# Jupiter_Ace_build024.net
KiCad netlist of a schematic drawn in EAGLE
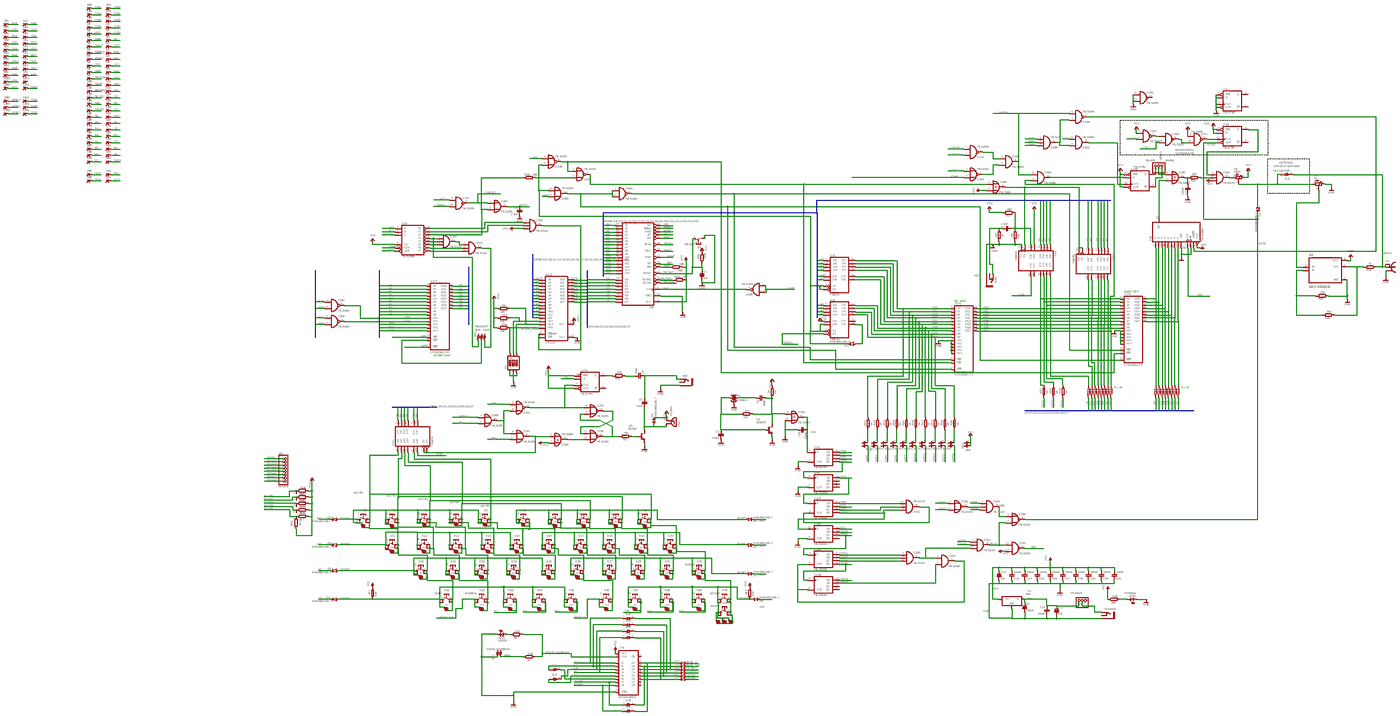
[diagram p0: schematic, sheet 1, overview]
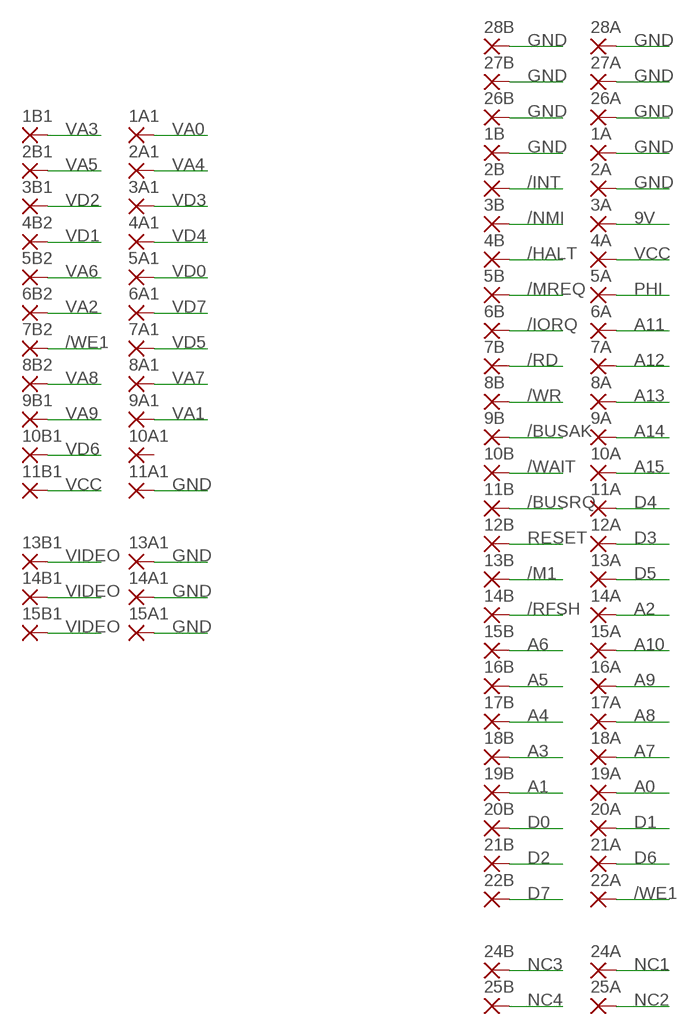
[diagram p1: schematic, sheet 1, part 1 of 5]
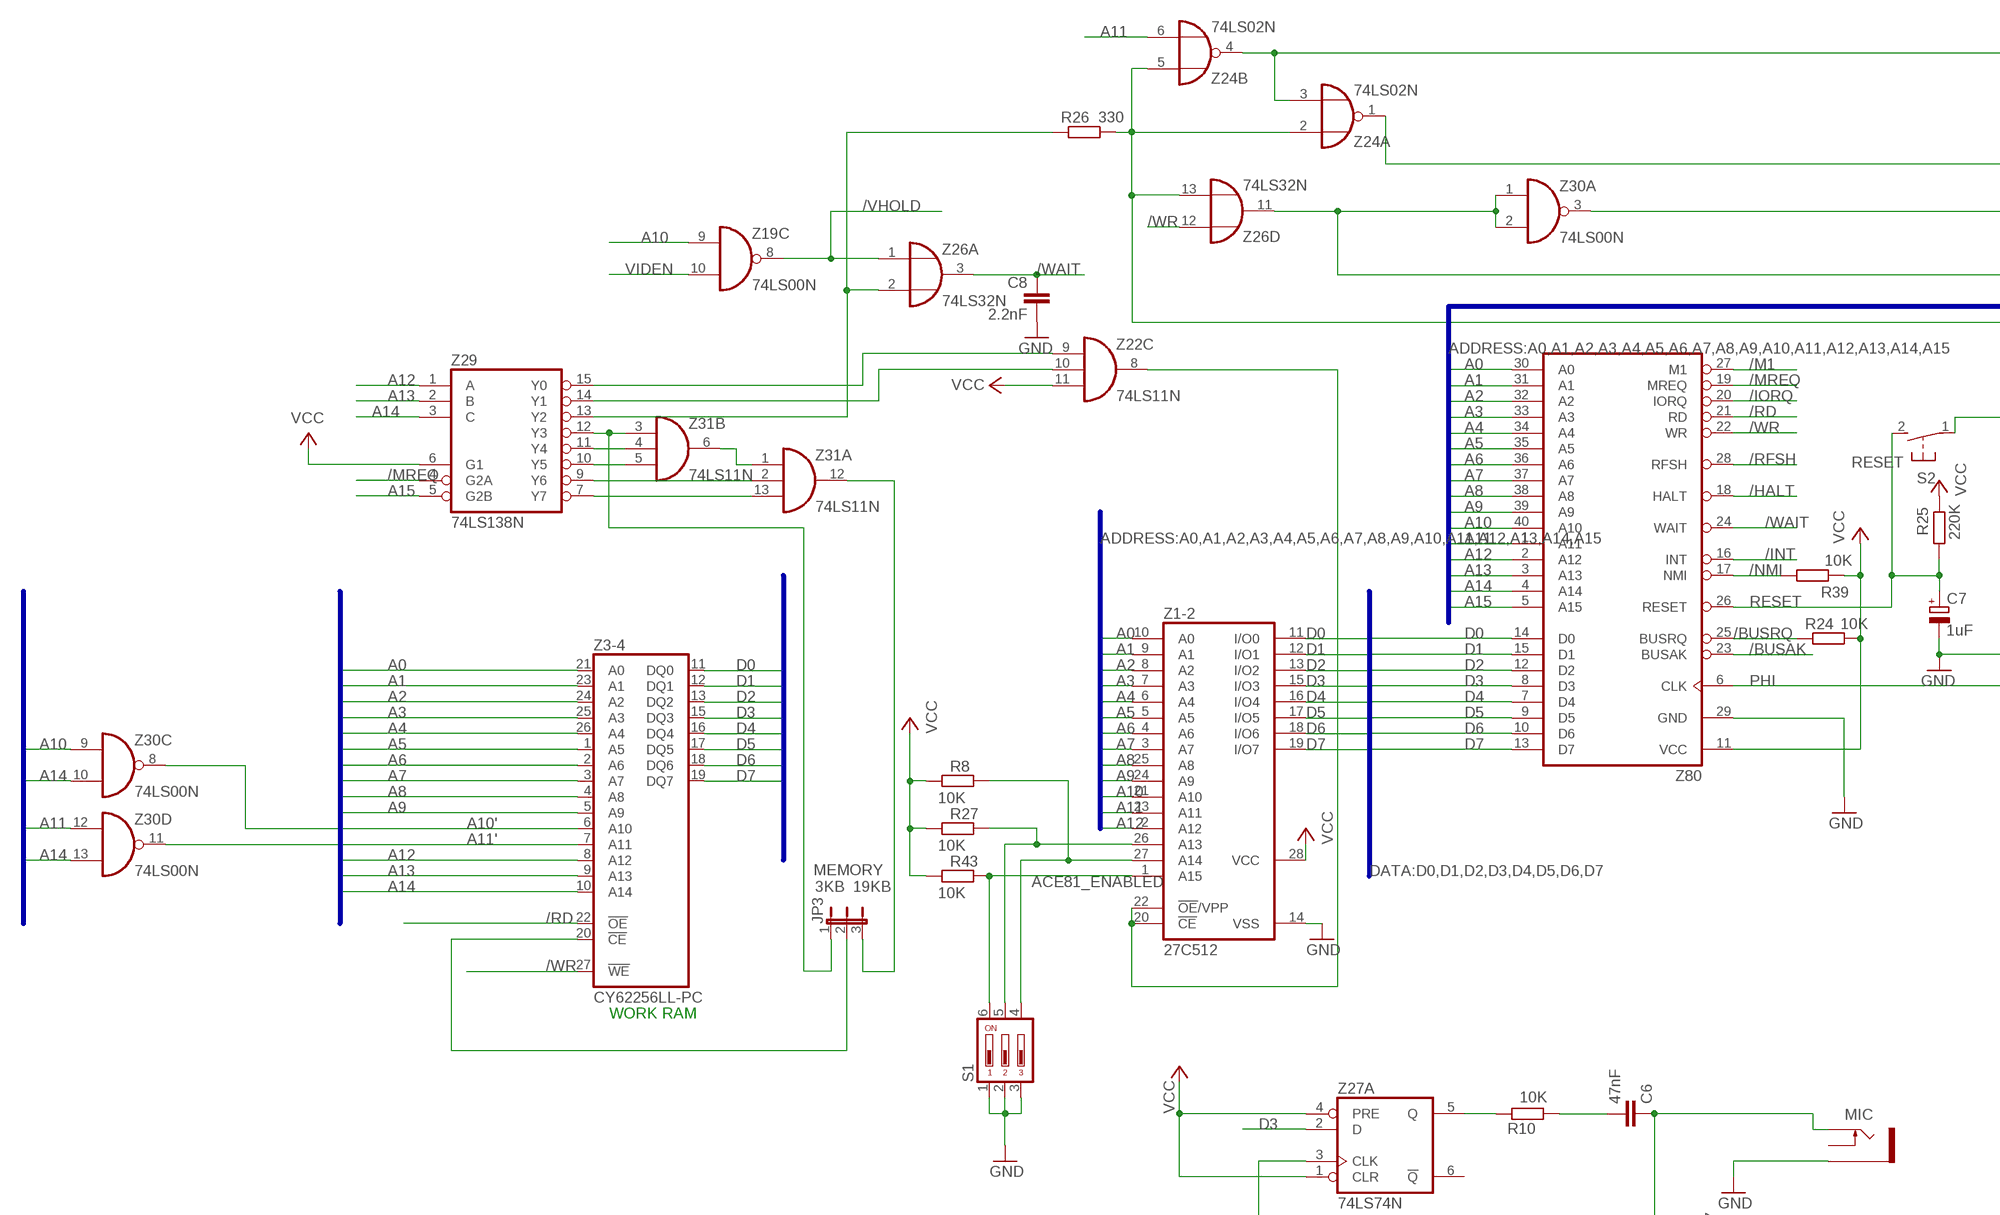
[diagram p2: schematic, sheet 1, part 2 of 5]
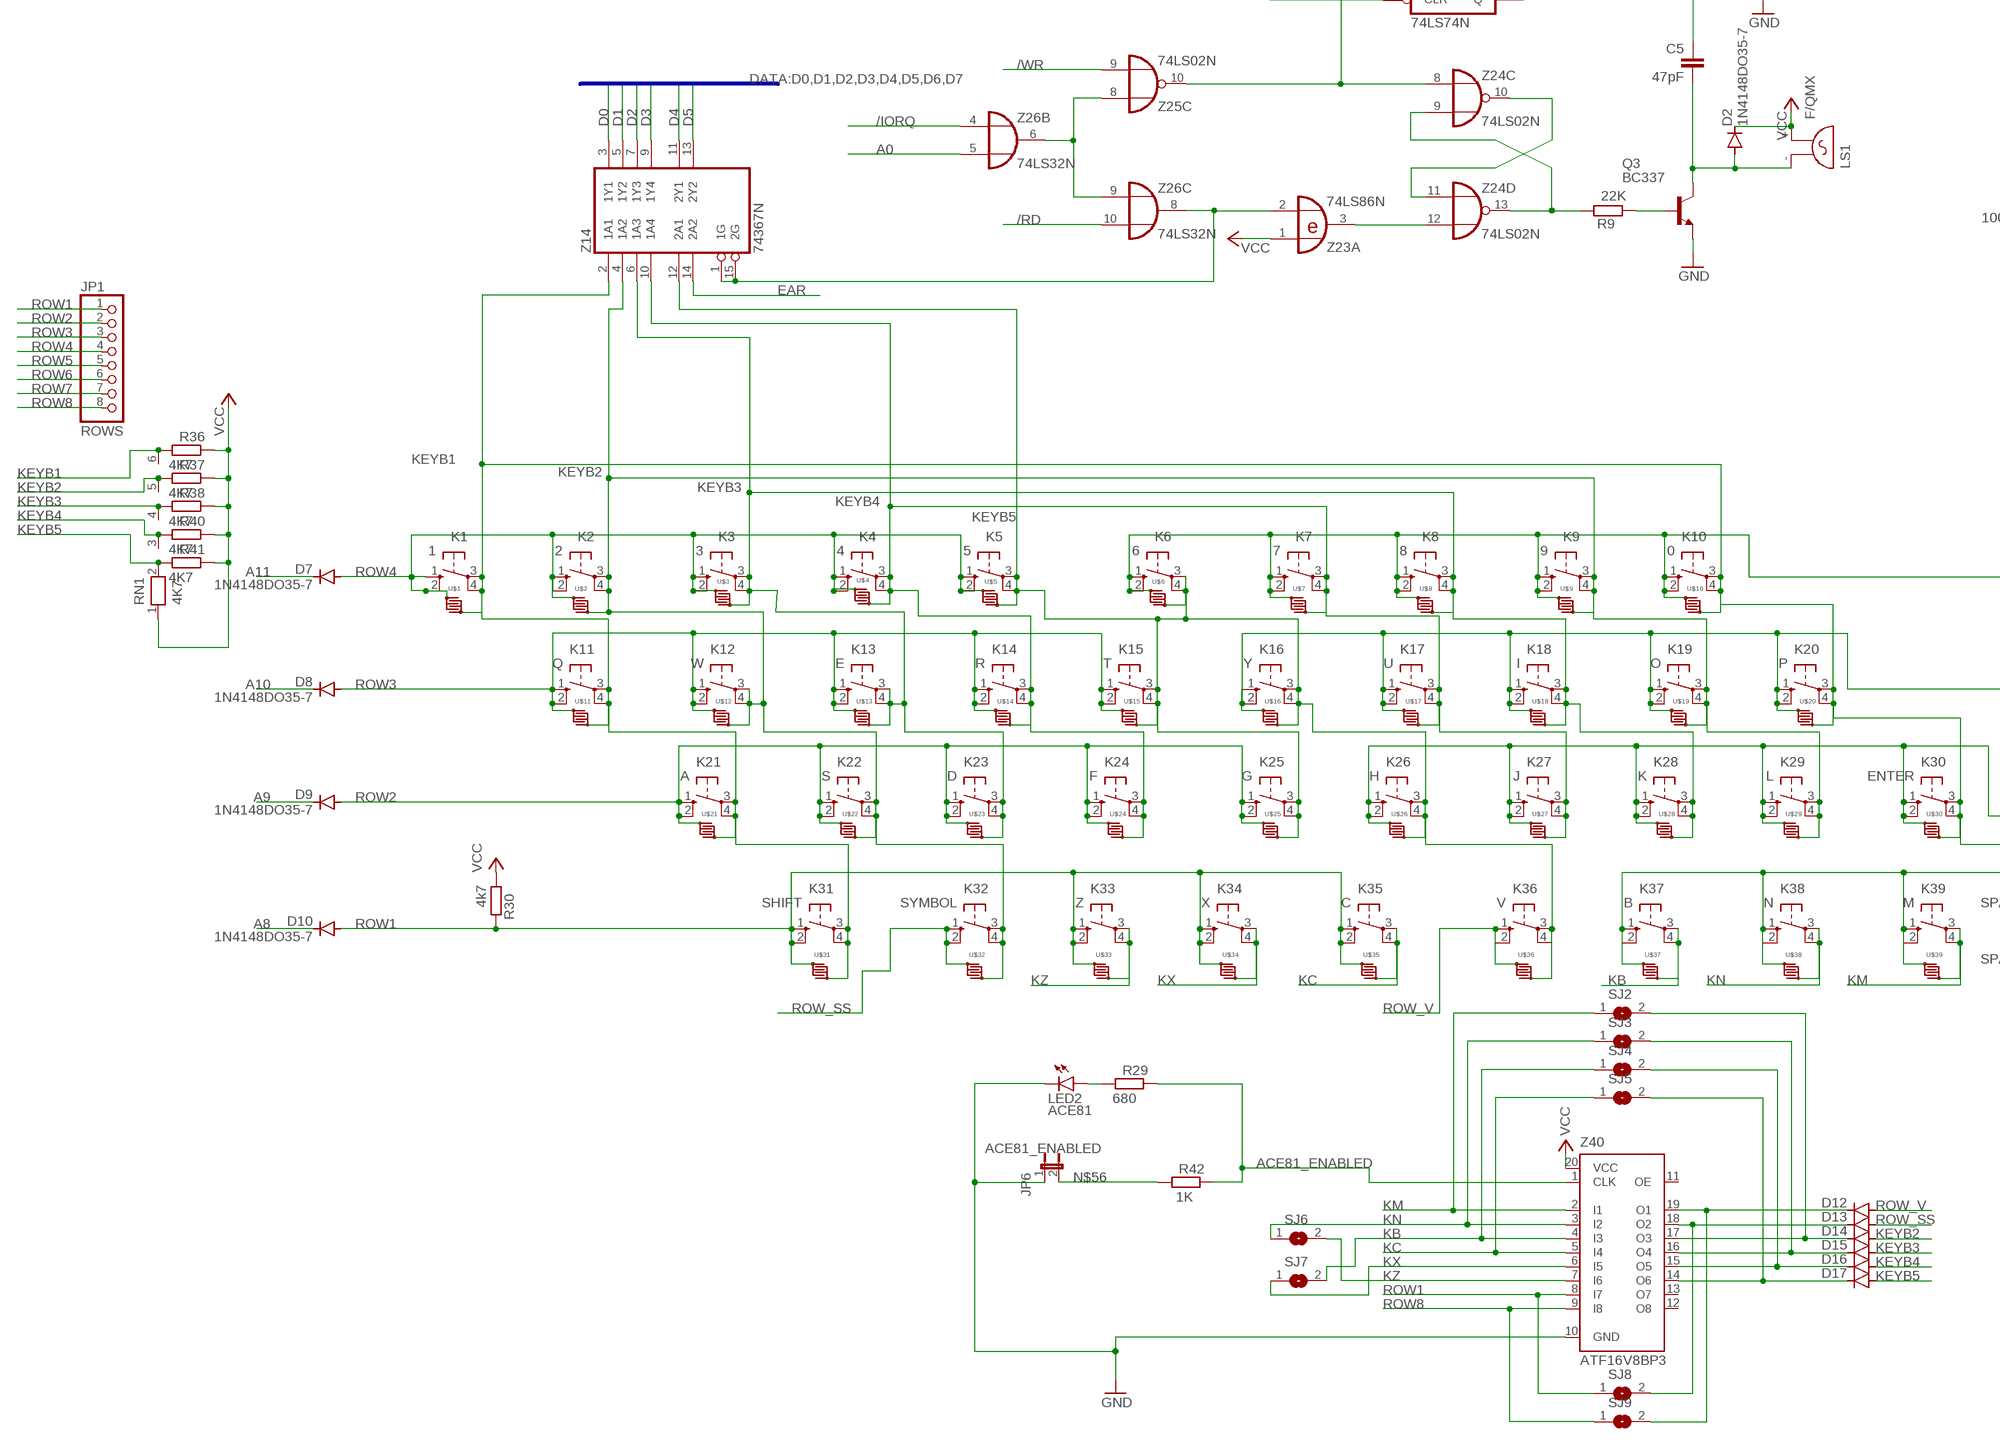
[diagram p3: schematic, sheet 1, part 3 of 5]
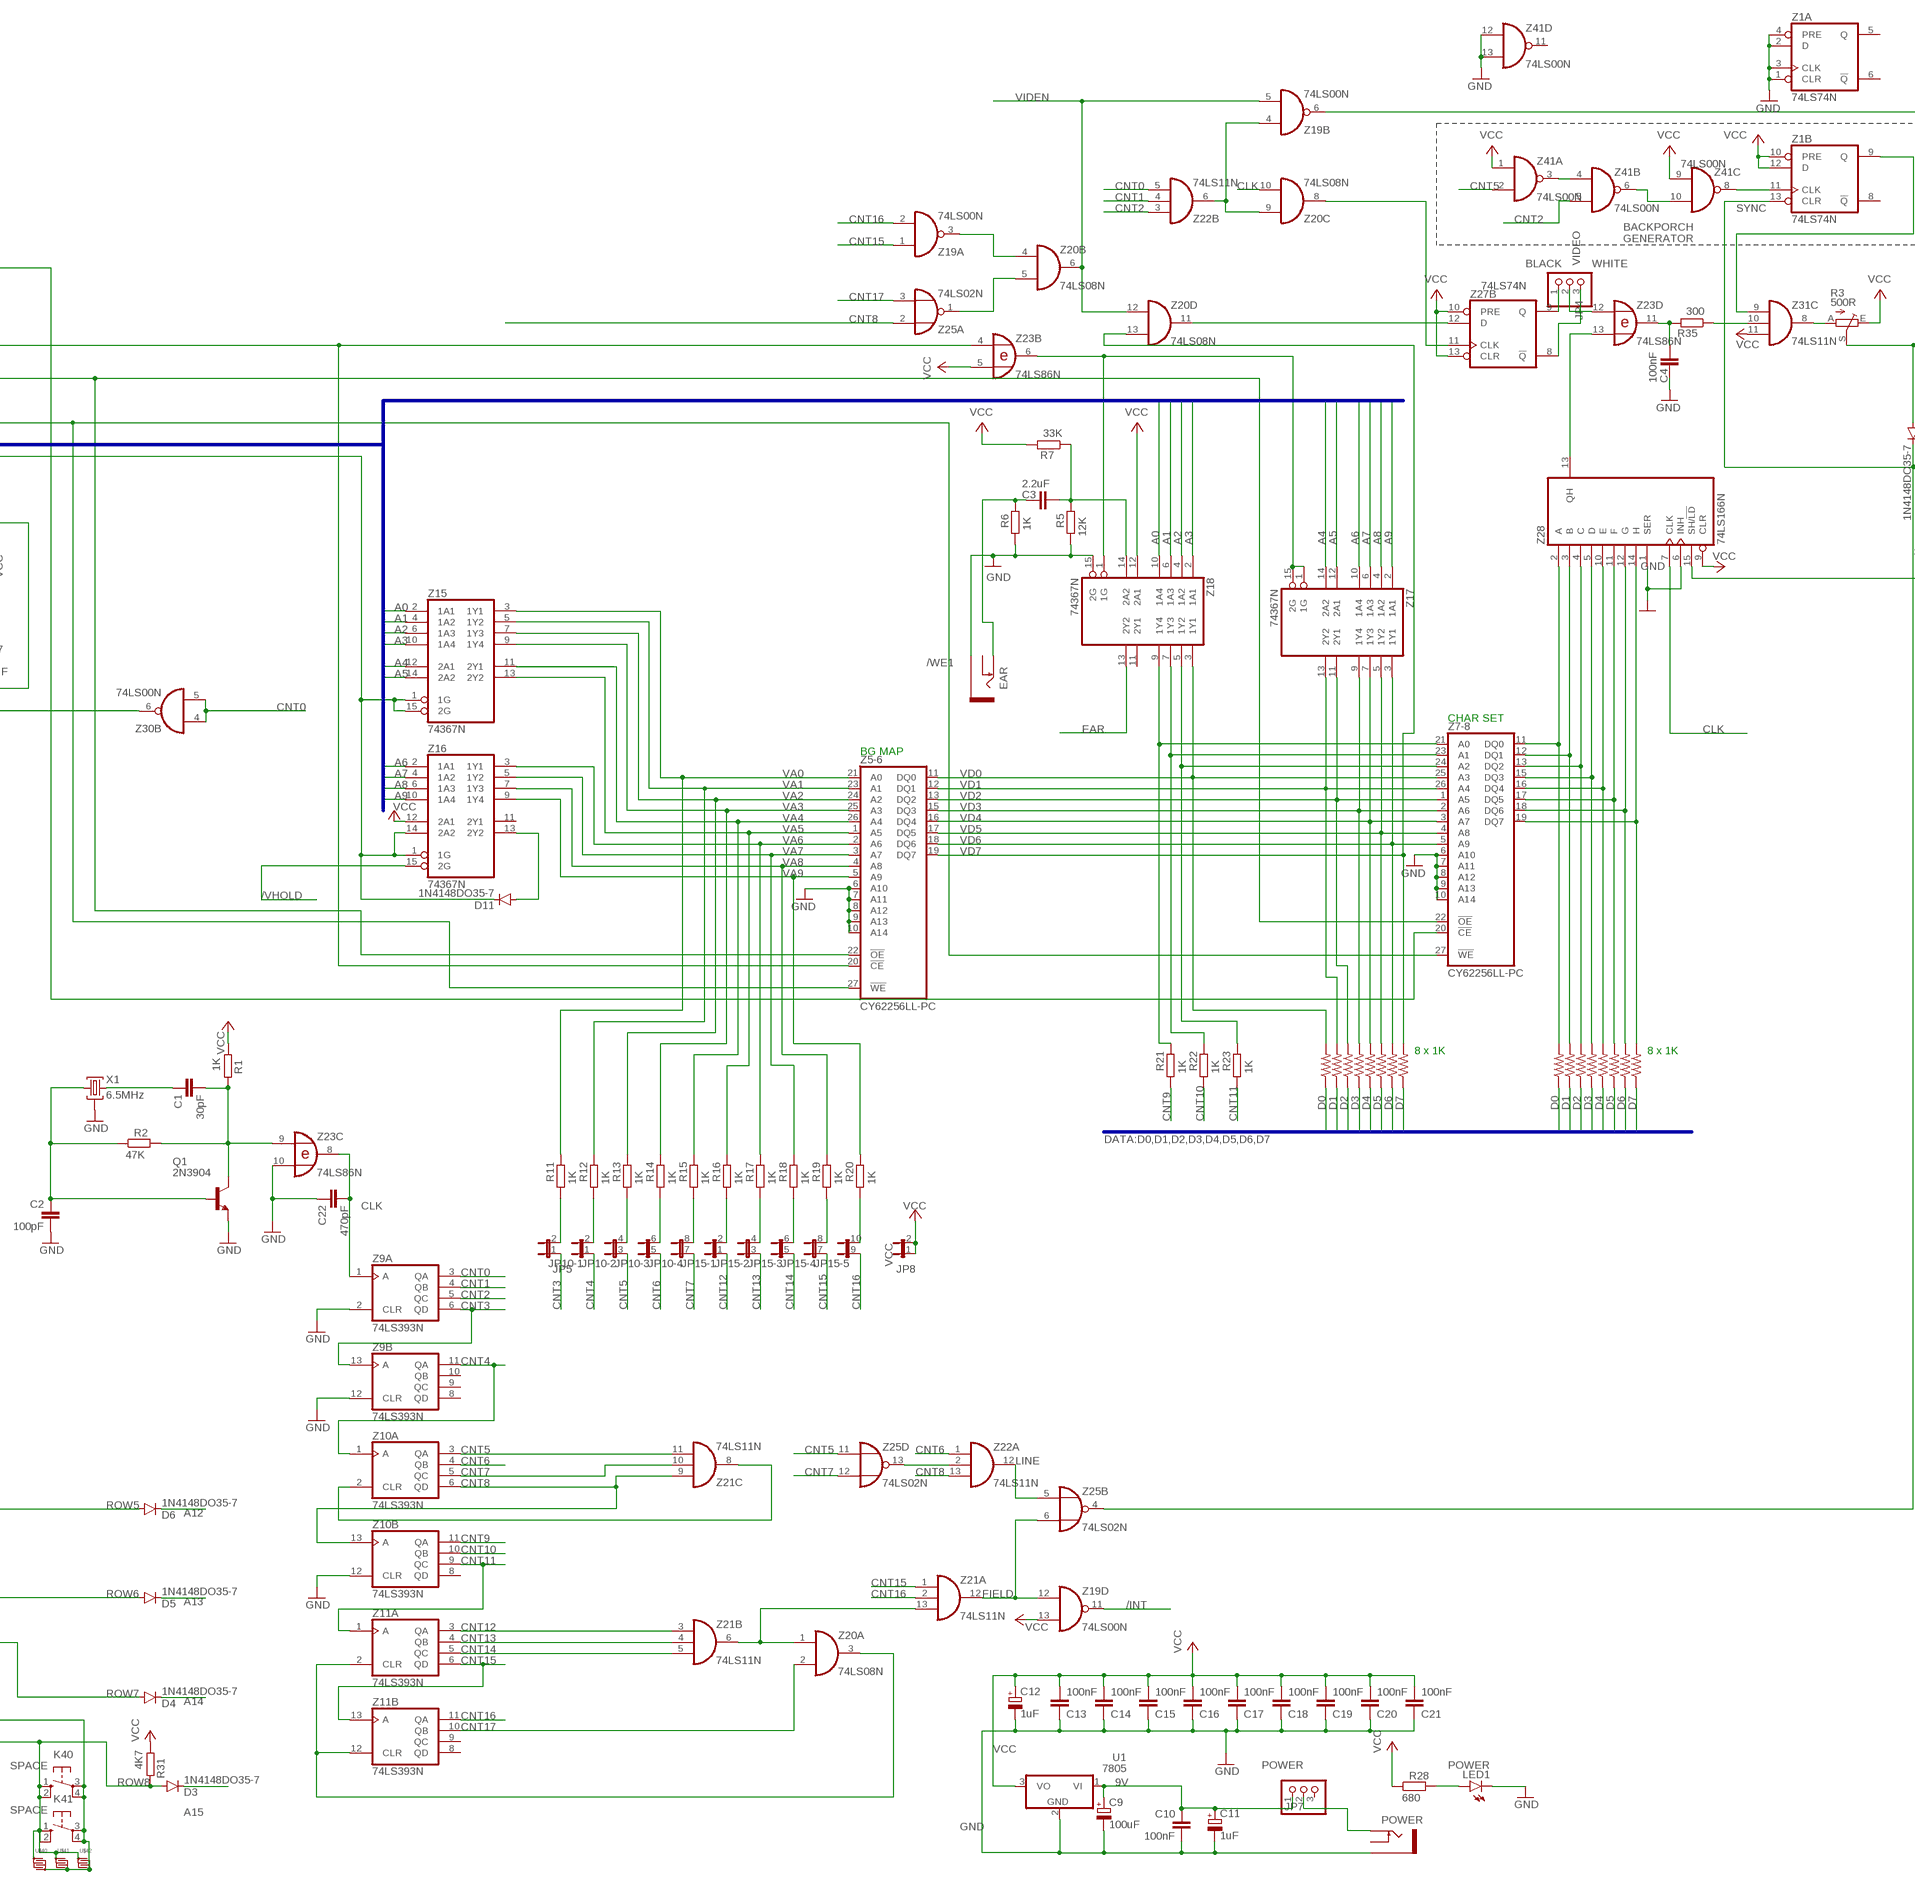
[diagram p4: schematic, sheet 1, part 4 of 5]
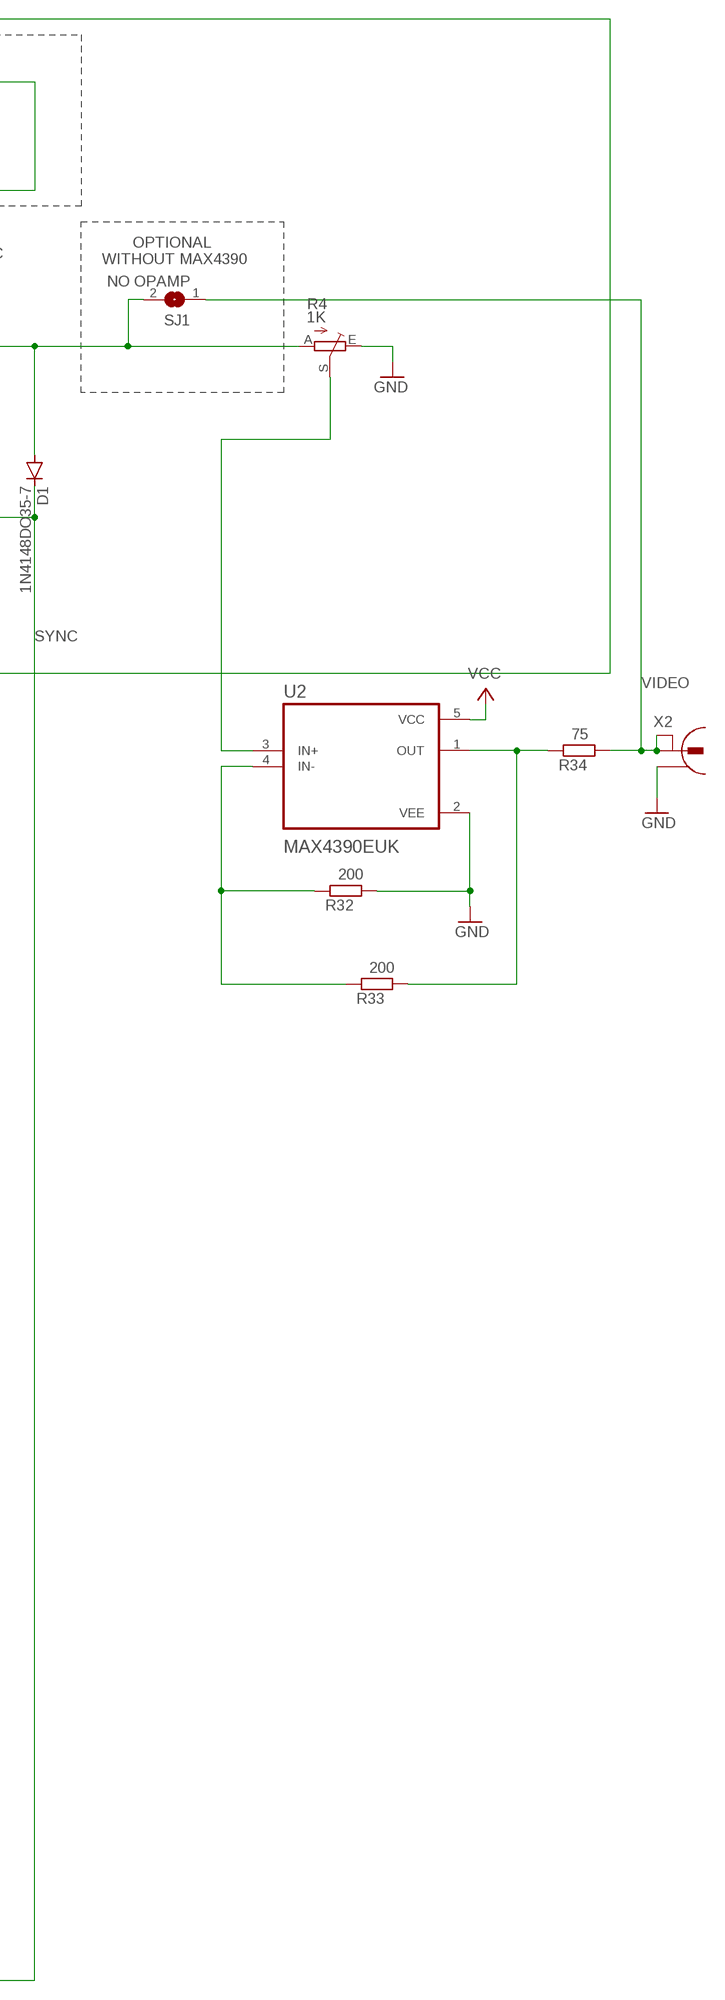
[diagram p5: schematic, sheet 1, part 5 of 5]

(export (version "E")
  (design (tool "Eeschema 10.0.6"))
  (components
    (comp (ref "1A")
      (value "SMD2EDGEPIN")
      (footprint "eagle-import:EDGEPIN")
      (libsource (lib "eagle-import") (part "SMD2EDGEPIN"))
    )
    (comp (ref "1A1")
      (value "SMD2EDGEPIN")
      (footprint "eagle-import:EDGEPIN")
      (libsource (lib "eagle-import") (part "SMD2EDGEPIN"))
    )
    (comp (ref "1B")
      (value "SMD2EDGEPIN")
      (footprint "eagle-import:EDGEPIN")
      (libsource (lib "eagle-import") (part "SMD2EDGEPIN"))
    )
    (comp (ref "1B1")
      (value "SMD2EDGEPIN")
      (footprint "eagle-import:EDGEPIN")
      (libsource (lib "eagle-import") (part "SMD2EDGEPIN"))
    )
    (comp (ref "2A")
      (value "SMD2EDGEPIN")
      (footprint "eagle-import:EDGEPIN")
      (libsource (lib "eagle-import") (part "SMD2EDGEPIN"))
    )
    (comp (ref "2A1")
      (value "SMD2EDGEPIN")
      (footprint "eagle-import:EDGEPIN")
      (libsource (lib "eagle-import") (part "SMD2EDGEPIN"))
    )
    (comp (ref "2B")
      (value "SMD2EDGEPIN")
      (footprint "eagle-import:EDGEPIN")
      (libsource (lib "eagle-import") (part "SMD2EDGEPIN"))
    )
    (comp (ref "2B1")
      (value "SMD2EDGEPIN")
      (footprint "eagle-import:EDGEPIN")
      (libsource (lib "eagle-import") (part "SMD2EDGEPIN"))
    )
    (comp (ref "3A")
      (value "SMD2EDGEPIN")
      (footprint "eagle-import:EDGEPIN")
      (libsource (lib "eagle-import") (part "SMD2EDGEPIN"))
    )
    (comp (ref "3A1")
      (value "SMD2EDGEPIN")
      (footprint "eagle-import:EDGEPIN")
      (libsource (lib "eagle-import") (part "SMD2EDGEPIN"))
    )
    (comp (ref "3B")
      (value "SMD2EDGEPIN")
      (footprint "eagle-import:EDGEPIN")
      (libsource (lib "eagle-import") (part "SMD2EDGEPIN"))
    )
    (comp (ref "3B1")
      (value "SMD2EDGEPIN")
      (footprint "eagle-import:EDGEPIN")
      (libsource (lib "eagle-import") (part "SMD2EDGEPIN"))
    )
    (comp (ref "4A")
      (value "SMD2EDGEPIN")
      (footprint "eagle-import:EDGEPIN")
      (libsource (lib "eagle-import") (part "SMD2EDGEPIN"))
    )
    (comp (ref "4A1")
      (value "SMD2EDGEPIN")
      (footprint "eagle-import:EDGEPIN")
      (libsource (lib "eagle-import") (part "SMD2EDGEPIN"))
    )
    (comp (ref "4B")
      (value "SMD2EDGEPIN")
      (footprint "eagle-import:EDGEPIN")
      (libsource (lib "eagle-import") (part "SMD2EDGEPIN"))
    )
    (comp (ref "4B2")
      (value "SMD2EDGEPIN")
      (footprint "eagle-import:EDGEPIN")
      (libsource (lib "eagle-import") (part "SMD2EDGEPIN"))
    )
    (comp (ref "5A")
      (value "SMD2EDGEPIN")
      (footprint "eagle-import:EDGEPIN")
      (libsource (lib "eagle-import") (part "SMD2EDGEPIN"))
    )
    (comp (ref "5A1")
      (value "SMD2EDGEPIN")
      (footprint "eagle-import:EDGEPIN")
      (libsource (lib "eagle-import") (part "SMD2EDGEPIN"))
    )
    (comp (ref "5B")
      (value "SMD2EDGEPIN")
      (footprint "eagle-import:EDGEPIN")
      (libsource (lib "eagle-import") (part "SMD2EDGEPIN"))
    )
    (comp (ref "5B2")
      (value "SMD2EDGEPIN")
      (footprint "eagle-import:EDGEPIN")
      (libsource (lib "eagle-import") (part "SMD2EDGEPIN"))
    )
    (comp (ref "6A")
      (value "SMD2EDGEPIN")
      (footprint "eagle-import:EDGEPIN")
      (libsource (lib "eagle-import") (part "SMD2EDGEPIN"))
    )
    (comp (ref "6A1")
      (value "SMD2EDGEPIN")
      (footprint "eagle-import:EDGEPIN")
      (libsource (lib "eagle-import") (part "SMD2EDGEPIN"))
    )
    (comp (ref "6B")
      (value "SMD2EDGEPIN")
      (footprint "eagle-import:EDGEPIN")
      (libsource (lib "eagle-import") (part "SMD2EDGEPIN"))
    )
    (comp (ref "6B2")
      (value "SMD2EDGEPIN")
      (footprint "eagle-import:EDGEPIN")
      (libsource (lib "eagle-import") (part "SMD2EDGEPIN"))
    )
    (comp (ref "7A")
      (value "SMD2EDGEPIN")
      (footprint "eagle-import:EDGEPIN")
      (libsource (lib "eagle-import") (part "SMD2EDGEPIN"))
    )
    (comp (ref "7A1")
      (value "SMD2EDGEPIN")
      (footprint "eagle-import:EDGEPIN")
      (libsource (lib "eagle-import") (part "SMD2EDGEPIN"))
    )
    (comp (ref "7B")
      (value "SMD2EDGEPIN")
      (footprint "eagle-import:EDGEPIN")
      (libsource (lib "eagle-import") (part "SMD2EDGEPIN"))
    )
    (comp (ref "7B2")
      (value "SMD2EDGEPIN")
      (footprint "eagle-import:EDGEPIN")
      (libsource (lib "eagle-import") (part "SMD2EDGEPIN"))
    )
    (comp (ref "8A")
      (value "SMD2EDGEPIN")
      (footprint "eagle-import:EDGEPIN")
      (libsource (lib "eagle-import") (part "SMD2EDGEPIN"))
    )
    (comp (ref "8A1")
      (value "SMD2EDGEPIN")
      (footprint "eagle-import:EDGEPIN")
      (libsource (lib "eagle-import") (part "SMD2EDGEPIN"))
    )
    (comp (ref "8B")
      (value "SMD2EDGEPIN")
      (footprint "eagle-import:EDGEPIN")
      (libsource (lib "eagle-import") (part "SMD2EDGEPIN"))
    )
    (comp (ref "8B2")
      (value "SMD2EDGEPIN")
      (footprint "eagle-import:EDGEPIN")
      (libsource (lib "eagle-import") (part "SMD2EDGEPIN"))
    )
    (comp (ref "9A")
      (value "SMD2EDGEPIN")
      (footprint "eagle-import:EDGEPIN")
      (libsource (lib "eagle-import") (part "SMD2EDGEPIN"))
    )
    (comp (ref "9A1")
      (value "SMD2EDGEPIN")
      (footprint "eagle-import:EDGEPIN")
      (libsource (lib "eagle-import") (part "SMD2EDGEPIN"))
    )
    (comp (ref "9B")
      (value "SMD2EDGEPIN")
      (footprint "eagle-import:EDGEPIN")
      (libsource (lib "eagle-import") (part "SMD2EDGEPIN"))
    )
    (comp (ref "9B1")
      (value "SMD2EDGEPIN")
      (footprint "eagle-import:EDGEPIN")
      (libsource (lib "eagle-import") (part "SMD2EDGEPIN"))
    )
    (comp (ref "10A")
      (value "SMD2EDGEPIN")
      (footprint "eagle-import:EDGEPIN")
      (libsource (lib "eagle-import") (part "SMD2EDGEPIN"))
    )
    (comp (ref "10A1")
      (value "SMD2EDGEPIN")
      (footprint "eagle-import:EDGEPIN")
      (libsource (lib "eagle-import") (part "SMD2EDGEPIN"))
    )
    (comp (ref "10B")
      (value "SMD2EDGEPIN")
      (footprint "eagle-import:EDGEPIN")
      (libsource (lib "eagle-import") (part "SMD2EDGEPIN"))
    )
    (comp (ref "10B1")
      (value "SMD2EDGEPIN")
      (footprint "eagle-import:EDGEPIN")
      (libsource (lib "eagle-import") (part "SMD2EDGEPIN"))
    )
    (comp (ref "11A")
      (value "SMD2EDGEPIN")
      (footprint "eagle-import:EDGEPIN")
      (libsource (lib "eagle-import") (part "SMD2EDGEPIN"))
    )
    (comp (ref "11A1")
      (value "SMD2EDGEPIN")
      (footprint "eagle-import:EDGEPIN")
      (libsource (lib "eagle-import") (part "SMD2EDGEPIN"))
    )
    (comp (ref "11B")
      (value "SMD2EDGEPIN")
      (footprint "eagle-import:EDGEPIN")
      (libsource (lib "eagle-import") (part "SMD2EDGEPIN"))
    )
    (comp (ref "11B1")
      (value "SMD2EDGEPIN")
      (footprint "eagle-import:EDGEPIN")
      (libsource (lib "eagle-import") (part "SMD2EDGEPIN"))
    )
    (comp (ref "12A")
      (value "SMD2EDGEPIN")
      (footprint "eagle-import:EDGEPIN")
      (libsource (lib "eagle-import") (part "SMD2EDGEPIN"))
    )
    (comp (ref "12B")
      (value "SMD2EDGEPIN")
      (footprint "eagle-import:EDGEPIN")
      (libsource (lib "eagle-import") (part "SMD2EDGEPIN"))
    )
    (comp (ref "13A")
      (value "SMD2EDGEPIN")
      (footprint "eagle-import:EDGEPIN")
      (libsource (lib "eagle-import") (part "SMD2EDGEPIN"))
    )
    (comp (ref "13A1")
      (value "SMD2EDGEPIN")
      (footprint "eagle-import:EDGEPIN")
      (libsource (lib "eagle-import") (part "SMD2EDGEPIN"))
    )
    (comp (ref "13B")
      (value "SMD2EDGEPIN")
      (footprint "eagle-import:EDGEPIN")
      (libsource (lib "eagle-import") (part "SMD2EDGEPIN"))
    )
    (comp (ref "13B1")
      (value "SMD2EDGEPIN")
      (footprint "eagle-import:EDGEPIN")
      (libsource (lib "eagle-import") (part "SMD2EDGEPIN"))
    )
    (comp (ref "14A")
      (value "SMD2EDGEPIN")
      (footprint "eagle-import:EDGEPIN")
      (libsource (lib "eagle-import") (part "SMD2EDGEPIN"))
    )
    (comp (ref "14A1")
      (value "SMD2EDGEPIN")
      (footprint "eagle-import:EDGEPIN")
      (libsource (lib "eagle-import") (part "SMD2EDGEPIN"))
    )
    (comp (ref "14B")
      (value "SMD2EDGEPIN")
      (footprint "eagle-import:EDGEPIN")
      (libsource (lib "eagle-import") (part "SMD2EDGEPIN"))
    )
    (comp (ref "14B1")
      (value "SMD2EDGEPIN")
      (footprint "eagle-import:EDGEPIN")
      (libsource (lib "eagle-import") (part "SMD2EDGEPIN"))
    )
    (comp (ref "15A")
      (value "SMD2EDGEPIN")
      (footprint "eagle-import:EDGEPIN")
      (libsource (lib "eagle-import") (part "SMD2EDGEPIN"))
    )
    (comp (ref "15A1")
      (value "SMD2EDGEPIN")
      (footprint "eagle-import:EDGEPIN")
      (libsource (lib "eagle-import") (part "SMD2EDGEPIN"))
    )
    (comp (ref "15B")
      (value "SMD2EDGEPIN")
      (footprint "eagle-import:EDGEPIN")
      (libsource (lib "eagle-import") (part "SMD2EDGEPIN"))
    )
    (comp (ref "15B1")
      (value "SMD2EDGEPIN")
      (footprint "eagle-import:EDGEPIN")
      (libsource (lib "eagle-import") (part "SMD2EDGEPIN"))
    )
    (comp (ref "16A")
      (value "SMD2EDGEPIN")
      (footprint "eagle-import:EDGEPIN")
      (libsource (lib "eagle-import") (part "SMD2EDGEPIN"))
    )
    (comp (ref "16B")
      (value "SMD2EDGEPIN")
      (footprint "eagle-import:EDGEPIN")
      (libsource (lib "eagle-import") (part "SMD2EDGEPIN"))
    )
    (comp (ref "17A")
      (value "SMD2EDGEPIN")
      (footprint "eagle-import:EDGEPIN")
      (libsource (lib "eagle-import") (part "SMD2EDGEPIN"))
    )
    (comp (ref "17B")
      (value "SMD2EDGEPIN")
      (footprint "eagle-import:EDGEPIN")
      (libsource (lib "eagle-import") (part "SMD2EDGEPIN"))
    )
    (comp (ref "18A")
      (value "SMD2EDGEPIN")
      (footprint "eagle-import:EDGEPIN")
      (libsource (lib "eagle-import") (part "SMD2EDGEPIN"))
    )
    (comp (ref "18B")
      (value "SMD2EDGEPIN")
      (footprint "eagle-import:EDGEPIN")
      (libsource (lib "eagle-import") (part "SMD2EDGEPIN"))
    )
    (comp (ref "19A")
      (value "SMD2EDGEPIN")
      (footprint "eagle-import:EDGEPIN")
      (libsource (lib "eagle-import") (part "SMD2EDGEPIN"))
    )
    (comp (ref "19B")
      (value "SMD2EDGEPIN")
      (footprint "eagle-import:EDGEPIN")
      (libsource (lib "eagle-import") (part "SMD2EDGEPIN"))
    )
    (comp (ref "20A")
      (value "SMD2EDGEPIN")
      (footprint "eagle-import:EDGEPIN")
      (libsource (lib "eagle-import") (part "SMD2EDGEPIN"))
    )
    (comp (ref "20B")
      (value "SMD2EDGEPIN")
      (footprint "eagle-import:EDGEPIN")
      (libsource (lib "eagle-import") (part "SMD2EDGEPIN"))
    )
    (comp (ref "21A")
      (value "SMD2EDGEPIN")
      (footprint "eagle-import:EDGEPIN")
      (libsource (lib "eagle-import") (part "SMD2EDGEPIN"))
    )
    (comp (ref "21B")
      (value "SMD2EDGEPIN")
      (footprint "eagle-import:EDGEPIN")
      (libsource (lib "eagle-import") (part "SMD2EDGEPIN"))
    )
    (comp (ref "22A")
      (value "SMD2EDGEPIN")
      (footprint "eagle-import:EDGEPIN")
      (libsource (lib "eagle-import") (part "SMD2EDGEPIN"))
    )
    (comp (ref "22B")
      (value "SMD2EDGEPIN")
      (footprint "eagle-import:EDGEPIN")
      (libsource (lib "eagle-import") (part "SMD2EDGEPIN"))
    )
    (comp (ref "24A")
      (value "SMD2EDGEPIN")
      (footprint "eagle-import:EDGEPIN")
      (libsource (lib "eagle-import") (part "SMD2EDGEPIN"))
    )
    (comp (ref "24B")
      (value "SMD2EDGEPIN")
      (footprint "eagle-import:EDGEPIN")
      (libsource (lib "eagle-import") (part "SMD2EDGEPIN"))
    )
    (comp (ref "25A")
      (value "SMD2EDGEPIN")
      (footprint "eagle-import:EDGEPIN")
      (libsource (lib "eagle-import") (part "SMD2EDGEPIN"))
    )
    (comp (ref "25B")
      (value "SMD2EDGEPIN")
      (footprint "eagle-import:EDGEPIN")
      (libsource (lib "eagle-import") (part "SMD2EDGEPIN"))
    )
    (comp (ref "26A")
      (value "SMD2EDGEPIN")
      (footprint "eagle-import:EDGEPIN")
      (libsource (lib "eagle-import") (part "SMD2EDGEPIN"))
    )
    (comp (ref "26B")
      (value "SMD2EDGEPIN")
      (footprint "eagle-import:EDGEPIN")
      (libsource (lib "eagle-import") (part "SMD2EDGEPIN"))
    )
    (comp (ref "27A")
      (value "SMD2EDGEPIN")
      (footprint "eagle-import:EDGEPIN")
      (libsource (lib "eagle-import") (part "SMD2EDGEPIN"))
    )
    (comp (ref "27B")
      (value "SMD2EDGEPIN")
      (footprint "eagle-import:EDGEPIN")
      (libsource (lib "eagle-import") (part "SMD2EDGEPIN"))
    )
    (comp (ref "28A")
      (value "SMD2EDGEPIN")
      (footprint "eagle-import:EDGEPIN")
      (libsource (lib "eagle-import") (part "SMD2EDGEPIN"))
    )
    (comp (ref "28B")
      (value "SMD2EDGEPIN")
      (footprint "eagle-import:EDGEPIN")
      (libsource (lib "eagle-import") (part "SMD2EDGEPIN"))
    )
    (comp (ref "C1")
      (value "30pF")
      (footprint "eagle-import:C025-025X050")
      (libsource (lib "eagle-import") (part "C-EU025-025X050"))
    )
    (comp (ref "C2")
      (value "100pF")
      (footprint "eagle-import:C025-025X050")
      (libsource (lib "eagle-import") (part "C-EU025-025X050"))
    )
    (comp (ref "C3")
      (value "2.2uF")
      (footprint "eagle-import:C025-025X050")
      (libsource (lib "eagle-import") (part "C-EU025-025X050"))
    )
    (comp (ref "C4")
      (value "100nF")
      (footprint "eagle-import:C025-025X050")
      (libsource (lib "eagle-import") (part "C-EU025-025X050"))
    )
    (comp (ref "C5")
      (value "47pF")
      (footprint "eagle-import:C025-025X050")
      (libsource (lib "eagle-import") (part "C-EU025-025X050"))
    )
    (comp (ref "C6")
      (value "47nF")
      (footprint "eagle-import:C025-025X050")
      (libsource (lib "eagle-import") (part "C-EU025-025X050"))
    )
    (comp (ref "C7")
      (value "1uF")
      (footprint "eagle-import:E1,8-4")
      (libsource (lib "eagle-import") (part "CPOL-EUE1.8-4"))
    )
    (comp (ref "C8")
      (value "2.2nF")
      (footprint "eagle-import:C025-025X050")
      (libsource (lib "eagle-import") (part "C-EU025-025X050"))
    )
    (comp (ref "C9")
      (value "100uF")
      (footprint "eagle-import:E1,8-4")
      (libsource (lib "eagle-import") (part "CPOL-EUE1.8-4"))
    )
    (comp (ref "C10")
      (value "100nF")
      (footprint "eagle-import:C025-025X050")
      (libsource (lib "eagle-import") (part "C-EU025-025X050"))
    )
    (comp (ref "C11")
      (value "1uF")
      (footprint "eagle-import:E1,8-4")
      (libsource (lib "eagle-import") (part "CPOL-EUE1.8-4"))
    )
    (comp (ref "C12")
      (value "1uF")
      (footprint "eagle-import:E1,8-4")
      (libsource (lib "eagle-import") (part "CPOL-EUE1.8-4"))
    )
    (comp (ref "C13")
      (value "100nF")
      (footprint "eagle-import:C025-025X050")
      (libsource (lib "eagle-import") (part "C-EU025-025X050"))
    )
    (comp (ref "C14")
      (value "100nF")
      (footprint "eagle-import:C025-025X050")
      (libsource (lib "eagle-import") (part "C-EU025-025X050"))
    )
    (comp (ref "C15")
      (value "100nF")
      (footprint "eagle-import:C025-025X050")
      (libsource (lib "eagle-import") (part "C-EU025-025X050"))
    )
    (comp (ref "C16")
      (value "100nF")
      (footprint "eagle-import:C025-025X050")
      (libsource (lib "eagle-import") (part "C-EU025-025X050"))
    )
    (comp (ref "C17")
      (value "100nF")
      (footprint "eagle-import:C025-025X050")
      (libsource (lib "eagle-import") (part "C-EU025-025X050"))
    )
    (comp (ref "C18")
      (value "100nF")
      (footprint "eagle-import:C025-025X050")
      (libsource (lib "eagle-import") (part "C-EU025-025X050"))
    )
    (comp (ref "C19")
      (value "100nF")
      (footprint "eagle-import:C025-025X050")
      (libsource (lib "eagle-import") (part "C-EU025-025X050"))
    )
    (comp (ref "C20")
      (value "100nF")
      (footprint "eagle-import:C025-025X050")
      (libsource (lib "eagle-import") (part "C-EU025-025X050"))
    )
    (comp (ref "C21")
      (value "100nF")
      (footprint "eagle-import:C025-025X050")
      (libsource (lib "eagle-import") (part "C-EU025-025X050"))
    )
    (comp (ref "C22")
      (value "470pF")
      (footprint "eagle-import:C025-025X050")
      (libsource (lib "eagle-import") (part "C-EU025-025X050"))
    )
    (comp (ref "D1")
      (value "1N4148DO35-7")
      (footprint "eagle-import:DO35-7")
      (libsource (lib "eagle-import") (part "1N4148DO35-7"))
    )
    (comp (ref "D2")
      (value "1N4148DO35-7")
      (footprint "eagle-import:DO35-7")
      (libsource (lib "eagle-import") (part "1N4148DO35-7"))
    )
    (comp (ref "D3")
      (value "1N4148DO35-7")
      (footprint "eagle-import:DO35-7")
      (libsource (lib "eagle-import") (part "1N4148DO35-7"))
    )
    (comp (ref "D4")
      (value "1N4148DO35-7")
      (footprint "eagle-import:DO35-7")
      (libsource (lib "eagle-import") (part "1N4148DO35-7"))
    )
    (comp (ref "D5")
      (value "1N4148DO35-7")
      (footprint "eagle-import:DO35-7")
      (libsource (lib "eagle-import") (part "1N4148DO35-7"))
    )
    (comp (ref "D6")
      (value "1N4148DO35-7")
      (footprint "eagle-import:DO35-7")
      (libsource (lib "eagle-import") (part "1N4148DO35-7"))
    )
    (comp (ref "D7")
      (value "1N4148DO35-7")
      (footprint "eagle-import:DO35-7")
      (libsource (lib "eagle-import") (part "1N4148DO35-7"))
    )
    (comp (ref "D8")
      (value "1N4148DO35-7")
      (footprint "eagle-import:DO35-7")
      (libsource (lib "eagle-import") (part "1N4148DO35-7"))
    )
    (comp (ref "D9")
      (value "1N4148DO35-7")
      (footprint "eagle-import:DO35-7")
      (libsource (lib "eagle-import") (part "1N4148DO35-7"))
    )
    (comp (ref "D10")
      (value "1N4148DO35-7")
      (footprint "eagle-import:DO35-7")
      (libsource (lib "eagle-import") (part "1N4148DO35-7"))
    )
    (comp (ref "D11")
      (value "1N4148DO35-7")
      (footprint "eagle-import:DO35-7")
      (libsource (lib "eagle-import") (part "1N4148DO35-7"))
    )
    (comp (ref "D12")
      (value "1N4148DO35-7")
      (footprint "eagle-import:DO35-7")
      (libsource (lib "eagle-import") (part "1N4148DO35-7"))
    )
    (comp (ref "D13")
      (value "1N4148DO35-7")
      (footprint "eagle-import:DO35-7")
      (libsource (lib "eagle-import") (part "1N4148DO35-7"))
    )
    (comp (ref "D14")
      (value "1N4148DO35-7")
      (footprint "eagle-import:DO35-7")
      (libsource (lib "eagle-import") (part "1N4148DO35-7"))
    )
    (comp (ref "D15")
      (value "1N4148DO35-7")
      (footprint "eagle-import:DO35-7")
      (libsource (lib "eagle-import") (part "1N4148DO35-7"))
    )
    (comp (ref "D16")
      (value "1N4148DO35-7")
      (footprint "eagle-import:DO35-7")
      (libsource (lib "eagle-import") (part "1N4148DO35-7"))
    )
    (comp (ref "D17")
      (value "1N4148DO35-7")
      (footprint "eagle-import:DO35-7")
      (libsource (lib "eagle-import") (part "1N4148DO35-7"))
    )
    (comp (ref "EAR")
      (value "PJ302M")
      (footprint "eagle-import:PJ302M")
      (libsource (lib "eagle-import") (part "PJ302M"))
    )
    (comp (ref "JP1")
      (value "ROWS")
      (footprint "eagle-import:1X08")
      (libsource (lib "eagle-import") (part "PINHD-1X8"))
    )
    (comp (ref "JP3")
      (value "MEMORY")
      (footprint "eagle-import:JP2")
      (libsource (lib "eagle-import") (part "JP2E"))
    )
    (comp (ref "JP4")
      (value "VIDEO")
      (footprint "eagle-import:1X03")
      (libsource (lib "eagle-import") (part "PINHD-1X3"))
    )
    (comp (ref "JP5")
      (value "JP1E1Q")
      (footprint "eagle-import:JP1Q")
      (libsource (lib "eagle-import") (part "JP1E1Q"))
    )
    (comp (ref "JP6")
      (value "ACE81_ENABLED")
      (footprint "eagle-import:JP1Q")
      (libsource (lib "eagle-import") (part "JP1E1Q"))
    )
    (comp (ref "JP7")
      (value "POWER")
      (footprint "eagle-import:1X03")
      (libsource (lib "eagle-import") (part "PINHD-1X3"))
    )
    (comp (ref "JP8")
      (value "VCC")
      (footprint "eagle-import:JP1Q")
      (libsource (lib "eagle-import") (part "JP1E1Q"))
    )
    (comp (ref "JP10")
      (value "JP4QE")
      (footprint "eagle-import:JP4Q")
      (libsource (lib "eagle-import") (part "JP4QE"))
    )
    (comp (ref "JP15")
      (value "JP5QE")
      (footprint "eagle-import:JP5Q")
      (libsource (lib "eagle-import") (part "JP5QE"))
    )
    (comp (ref "K1")
      (value "1")
      (footprint "eagle-import:B3F-40XXNOHOLE")
      (libsource (lib "eagle-import") (part "40-XXNOHOLES"))
    )
    (comp (ref "K2")
      (value "2")
      (footprint "eagle-import:B3F-40XXNOHOLE")
      (libsource (lib "eagle-import") (part "40-XXNOHOLES"))
    )
    (comp (ref "K3")
      (value "3")
      (footprint "eagle-import:B3F-40XXNOHOLE")
      (libsource (lib "eagle-import") (part "40-XXNOHOLES"))
    )
    (comp (ref "K4")
      (value "4")
      (footprint "eagle-import:B3F-40XXNOHOLE")
      (libsource (lib "eagle-import") (part "40-XXNOHOLES"))
    )
    (comp (ref "K5")
      (value "5")
      (footprint "eagle-import:B3F-40XXNOHOLE")
      (libsource (lib "eagle-import") (part "40-XXNOHOLES"))
    )
    (comp (ref "K6")
      (value "6")
      (footprint "eagle-import:B3F-40XXNOHOLE")
      (libsource (lib "eagle-import") (part "40-XXNOHOLES"))
    )
    (comp (ref "K7")
      (value "7")
      (footprint "eagle-import:B3F-40XXNOHOLE")
      (libsource (lib "eagle-import") (part "40-XXNOHOLES"))
    )
    (comp (ref "K8")
      (value "8")
      (footprint "eagle-import:B3F-40XXNOHOLE")
      (libsource (lib "eagle-import") (part "40-XXNOHOLES"))
    )
    (comp (ref "K9")
      (value "9")
      (footprint "eagle-import:B3F-40XXNOHOLE")
      (libsource (lib "eagle-import") (part "40-XXNOHOLES"))
    )
    (comp (ref "K10")
      (value "0")
      (footprint "eagle-import:B3F-40XXNOHOLE")
      (libsource (lib "eagle-import") (part "40-XXNOHOLES"))
    )
    (comp (ref "K11")
      (value "Q")
      (footprint "eagle-import:B3F-40XXNOHOLE")
      (libsource (lib "eagle-import") (part "40-XXNOHOLES"))
    )
    (comp (ref "K12")
      (value "W")
      (footprint "eagle-import:B3F-40XXNOHOLE")
      (libsource (lib "eagle-import") (part "40-XXNOHOLES"))
    )
    (comp (ref "K13")
      (value "E")
      (footprint "eagle-import:B3F-40XXNOHOLE")
      (libsource (lib "eagle-import") (part "40-XXNOHOLES"))
    )
    (comp (ref "K14")
      (value "R")
      (footprint "eagle-import:B3F-40XXNOHOLE")
      (libsource (lib "eagle-import") (part "40-XXNOHOLES"))
    )
    (comp (ref "K15")
      (value "T")
      (footprint "eagle-import:B3F-40XXNOHOLE")
      (libsource (lib "eagle-import") (part "40-XXNOHOLES"))
    )
    (comp (ref "K16")
      (value "Y")
      (footprint "eagle-import:B3F-40XXNOHOLE")
      (libsource (lib "eagle-import") (part "40-XXNOHOLES"))
    )
    (comp (ref "K17")
      (value "U")
      (footprint "eagle-import:B3F-40XXNOHOLE")
      (libsource (lib "eagle-import") (part "40-XXNOHOLES"))
    )
    (comp (ref "K18")
      (value "I")
      (footprint "eagle-import:B3F-40XXNOHOLE")
      (libsource (lib "eagle-import") (part "40-XXNOHOLES"))
    )
    (comp (ref "K19")
      (value "O")
      (footprint "eagle-import:B3F-40XXNOHOLE")
      (libsource (lib "eagle-import") (part "40-XXNOHOLES"))
    )
    (comp (ref "K20")
      (value "P")
      (footprint "eagle-import:B3F-40XXNOHOLE")
      (libsource (lib "eagle-import") (part "40-XXNOHOLES"))
    )
    (comp (ref "K21")
      (value "A")
      (footprint "eagle-import:B3F-40XXNOHOLE")
      (libsource (lib "eagle-import") (part "40-XXNOHOLES"))
    )
    (comp (ref "K22")
      (value "S")
      (footprint "eagle-import:B3F-40XXNOHOLE")
      (libsource (lib "eagle-import") (part "40-XXNOHOLES"))
    )
    (comp (ref "K23")
      (value "D")
      (footprint "eagle-import:B3F-40XXNOHOLE")
      (libsource (lib "eagle-import") (part "40-XXNOHOLES"))
    )
    (comp (ref "K24")
      (value "F")
      (footprint "eagle-import:B3F-40XXNOHOLE")
      (libsource (lib "eagle-import") (part "40-XXNOHOLES"))
    )
    (comp (ref "K25")
      (value "G")
      (footprint "eagle-import:B3F-40XXNOHOLE")
      (libsource (lib "eagle-import") (part "40-XXNOHOLES"))
    )
    (comp (ref "K26")
      (value "H")
      (footprint "eagle-import:B3F-40XXNOHOLE")
      (libsource (lib "eagle-import") (part "40-XXNOHOLES"))
    )
    (comp (ref "K27")
      (value "J")
      (footprint "eagle-import:B3F-40XXNOHOLE")
      (libsource (lib "eagle-import") (part "40-XXNOHOLES"))
    )
    (comp (ref "K28")
      (value "K")
      (footprint "eagle-import:B3F-40XXNOHOLE")
      (libsource (lib "eagle-import") (part "40-XXNOHOLES"))
    )
    (comp (ref "K29")
      (value "L")
      (footprint "eagle-import:B3F-40XXNOHOLE")
      (libsource (lib "eagle-import") (part "40-XXNOHOLES"))
    )
    (comp (ref "K30")
      (value "ENTER")
      (footprint "eagle-import:B3F-40XXNOHOLE")
      (libsource (lib "eagle-import") (part "40-XXNOHOLES"))
    )
    (comp (ref "K31")
      (value "SHIFT")
      (footprint "eagle-import:B3F-40XXNOHOLE")
      (libsource (lib "eagle-import") (part "40-XXNOHOLES"))
    )
    (comp (ref "K32")
      (value "SYMBOL")
      (footprint "eagle-import:B3F-40XXNOHOLE")
      (libsource (lib "eagle-import") (part "40-XXNOHOLES"))
    )
    (comp (ref "K33")
      (value "Z")
      (footprint "eagle-import:B3F-40XXNOHOLE")
      (libsource (lib "eagle-import") (part "40-XXNOHOLES"))
    )
    (comp (ref "K34")
      (value "X")
      (footprint "eagle-import:B3F-40XXNOHOLE")
      (libsource (lib "eagle-import") (part "40-XXNOHOLES"))
    )
    (comp (ref "K35")
      (value "C")
      (footprint "eagle-import:B3F-40XXNOHOLE")
      (libsource (lib "eagle-import") (part "40-XXNOHOLES"))
    )
    (comp (ref "K36")
      (value "V")
      (footprint "eagle-import:B3F-40XXNOHOLE")
      (libsource (lib "eagle-import") (part "40-XXNOHOLES"))
    )
    (comp (ref "K37")
      (value "B")
      (footprint "eagle-import:B3F-40XXNOHOLE")
      (libsource (lib "eagle-import") (part "40-XXNOHOLES"))
    )
    (comp (ref "K38")
      (value "N")
      (footprint "eagle-import:B3F-40XXNOHOLE")
      (libsource (lib "eagle-import") (part "40-XXNOHOLES"))
    )
    (comp (ref "K39")
      (value "M")
      (footprint "eagle-import:B3F-40XXNOHOLE")
      (libsource (lib "eagle-import") (part "40-XXNOHOLES"))
    )
    (comp (ref "K40")
      (value "SPACE")
      (footprint "eagle-import:B3F-40XXNOHOLE")
      (libsource (lib "eagle-import") (part "40-XXNOHOLES"))
    )
    (comp (ref "K41")
      (value "SPACE")
      (footprint "eagle-import:B3F-40XXNOHOLE")
      (libsource (lib "eagle-import") (part "40-XXNOHOLES"))
    )
    (comp (ref "LED1")
      (value "POWER")
      (footprint "eagle-import:LED3MM")
      (libsource (lib "eagle-import") (part "LED3MM"))
    )
    (comp (ref "LED2")
      (value "ACE81")
      (footprint "eagle-import:LED3MM")
      (libsource (lib "eagle-import") (part "LED3MM"))
    )
    (comp (ref "LS1")
      (value "F/QMX")
      (footprint "eagle-import:F_QMX")
      (libsource (lib "eagle-import") (part "F/QMX"))
    )
    (comp (ref "MIC")
      (value "PJ302M")
      (footprint "eagle-import:PJ302M")
      (libsource (lib "eagle-import") (part "PJ302M"))
    )
    (comp (ref "POWER")
      (value "PJ302M")
      (footprint "eagle-import:PJ302M")
      (libsource (lib "eagle-import") (part "PJ302M"))
    )
    (comp (ref "Q1")
      (value "2N3904")
      (footprint "eagle-import:TO92")
      (libsource (lib "eagle-import") (part "2N3904"))
    )
    (comp (ref "Q3")
      (value "BC337")
      (footprint "eagle-import:TO92")
      (libsource (lib "eagle-import") (part "BC337"))
    )
    (comp (ref "R1")
      (value "1K")
      (footprint "eagle-import:0204_7")
      (libsource (lib "eagle-import") (part "R-EU_0204/7"))
    )
    (comp (ref "R2")
      (value "47K")
      (footprint "eagle-import:0204_7")
      (libsource (lib "eagle-import") (part "R-EU_0204/7"))
    )
    (comp (ref "R3")
      (value "500R")
      (footprint "eagle-import:B25P")
      (libsource (lib "eagle-import") (part "TRIM_EU-B25P"))
    )
    (comp (ref "R4")
      (value "1K")
      (footprint "eagle-import:B25P")
      (libsource (lib "eagle-import") (part "TRIM_EU-B25P"))
    )
    (comp (ref "R5")
      (value "12K")
      (footprint "eagle-import:0204_7")
      (libsource (lib "eagle-import") (part "R-EU_0204/7"))
    )
    (comp (ref "R6")
      (value "1K")
      (footprint "eagle-import:0204_7")
      (libsource (lib "eagle-import") (part "R-EU_0204/7"))
    )
    (comp (ref "R7")
      (value "33K")
      (footprint "eagle-import:0204_7")
      (libsource (lib "eagle-import") (part "R-EU_0204/7"))
    )
    (comp (ref "R8")
      (value "10K")
      (footprint "eagle-import:0204_7")
      (libsource (lib "eagle-import") (part "R-EU_0204/7"))
    )
    (comp (ref "R9")
      (value "22K")
      (footprint "eagle-import:0204_7")
      (libsource (lib "eagle-import") (part "R-EU_0204/7"))
    )
    (comp (ref "R10")
      (value "10K")
      (footprint "eagle-import:0204_7")
      (libsource (lib "eagle-import") (part "R-EU_0204/7"))
    )
    (comp (ref "R11")
      (value "1K")
      (footprint "eagle-import:0204_7")
      (libsource (lib "eagle-import") (part "R-EU_0204/7"))
    )
    (comp (ref "R12")
      (value "1K")
      (footprint "eagle-import:0204_7")
      (libsource (lib "eagle-import") (part "R-EU_0204/7"))
    )
    (comp (ref "R13")
      (value "1K")
      (footprint "eagle-import:0204_7")
      (libsource (lib "eagle-import") (part "R-EU_0204/7"))
    )
    (comp (ref "R14")
      (value "1K")
      (footprint "eagle-import:0204_7")
      (libsource (lib "eagle-import") (part "R-EU_0204/7"))
    )
    (comp (ref "R15")
      (value "1K")
      (footprint "eagle-import:0204_7")
      (libsource (lib "eagle-import") (part "R-EU_0204/7"))
    )
    (comp (ref "R16")
      (value "1K")
      (footprint "eagle-import:0204_7")
      (libsource (lib "eagle-import") (part "R-EU_0204/7"))
    )
    (comp (ref "R17")
      (value "1K")
      (footprint "eagle-import:0204_7")
      (libsource (lib "eagle-import") (part "R-EU_0204/7"))
    )
    (comp (ref "R18")
      (value "1K")
      (footprint "eagle-import:0204_7")
      (libsource (lib "eagle-import") (part "R-EU_0204/7"))
    )
    (comp (ref "R19")
      (value "1K")
      (footprint "eagle-import:0204_7")
      (libsource (lib "eagle-import") (part "R-EU_0204/7"))
    )
    (comp (ref "R20")
      (value "1K")
      (footprint "eagle-import:0204_7")
      (libsource (lib "eagle-import") (part "R-EU_0204/7"))
    )
    (comp (ref "R21")
      (value "1K")
      (footprint "eagle-import:0204_7")
      (libsource (lib "eagle-import") (part "R-EU_0204/7"))
    )
    (comp (ref "R22")
      (value "1K")
      (footprint "eagle-import:0204_7")
      (libsource (lib "eagle-import") (part "R-EU_0204/7"))
    )
    (comp (ref "R23")
      (value "1K")
      (footprint "eagle-import:0204_7")
      (libsource (lib "eagle-import") (part "R-EU_0204/7"))
    )
    (comp (ref "R24")
      (value "10K")
      (footprint "eagle-import:0204_7")
      (libsource (lib "eagle-import") (part "R-EU_0204/7"))
    )
    (comp (ref "R25")
      (value "220K")
      (footprint "eagle-import:0204_7")
      (libsource (lib "eagle-import") (part "R-EU_0204/7"))
    )
    (comp (ref "R26")
      (value "330")
      (footprint "eagle-import:0204_7")
      (libsource (lib "eagle-import") (part "R-EU_0204/7"))
    )
    (comp (ref "R27")
      (value "10K")
      (footprint "eagle-import:0204_7")
      (libsource (lib "eagle-import") (part "R-EU_0204/7"))
    )
    (comp (ref "R28")
      (value "680")
      (footprint "eagle-import:0204_7")
      (libsource (lib "eagle-import") (part "R-EU_0204/7"))
    )
    (comp (ref "R29")
      (value "680")
      (footprint "eagle-import:0204_7")
      (libsource (lib "eagle-import") (part "R-EU_0204/7"))
    )
    (comp (ref "R30")
      (value "4k7")
      (footprint "eagle-import:0204_7")
      (libsource (lib "eagle-import") (part "R-EU_0204/7"))
    )
    (comp (ref "R31")
      (value "4K7")
      (footprint "eagle-import:0204_7")
      (libsource (lib "eagle-import") (part "R-EU_0204/7"))
    )
    (comp (ref "R32")
      (value "200")
      (footprint "eagle-import:0204_7")
      (libsource (lib "eagle-import") (part "R-EU_0204/7"))
    )
    (comp (ref "R33")
      (value "200")
      (footprint "eagle-import:0204_7")
      (libsource (lib "eagle-import") (part "R-EU_0204/7"))
    )
    (comp (ref "R34")
      (value "75")
      (footprint "eagle-import:0204_7")
      (libsource (lib "eagle-import") (part "R-EU_0204/7"))
    )
    (comp (ref "R35")
      (value "300")
      (footprint "eagle-import:0204_7")
      (libsource (lib "eagle-import") (part "R-EU_0204/7"))
    )
    (comp (ref "R36")
      (value "4K7")
      (footprint "eagle-import:0207_10")
      (libsource (lib "eagle-import") (part "R-EU_0207/10"))
    )
    (comp (ref "R37")
      (value "4K7")
      (footprint "eagle-import:0207_10")
      (libsource (lib "eagle-import") (part "R-EU_0207/10"))
    )
    (comp (ref "R38")
      (value "4K7")
      (footprint "eagle-import:0207_10")
      (libsource (lib "eagle-import") (part "R-EU_0207/10"))
    )
    (comp (ref "R39")
      (value "10K")
      (footprint "eagle-import:0204_7")
      (libsource (lib "eagle-import") (part "R-EU_0204/7"))
    )
    (comp (ref "R40")
      (value "4K7")
      (footprint "eagle-import:0207_10")
      (libsource (lib "eagle-import") (part "R-EU_0207/10"))
    )
    (comp (ref "R41")
      (value "4K7")
      (footprint "eagle-import:0207_10")
      (libsource (lib "eagle-import") (part "R-EU_0207/10"))
    )
    (comp (ref "R42")
      (value "1K")
      (footprint "eagle-import:0204_7")
      (libsource (lib "eagle-import") (part "R-EU_0204/7"))
    )
    (comp (ref "R43")
      (value "10K")
      (footprint "eagle-import:0204_7")
      (libsource (lib "eagle-import") (part "R-EU_0204/7"))
    )
    (comp (ref "R100")
      (value "1K")
      (footprint "eagle-import:0204V")
      (libsource (lib "eagle-import") (part "R-US_0204/2V"))
    )
    (comp (ref "R101")
      (value "1K")
      (footprint "eagle-import:0204V")
      (libsource (lib "eagle-import") (part "R-US_0204/2V"))
    )
    (comp (ref "R102")
      (value "1K")
      (footprint "eagle-import:0204V")
      (libsource (lib "eagle-import") (part "R-US_0204/2V"))
    )
    (comp (ref "R103")
      (value "1K")
      (footprint "eagle-import:0204V")
      (libsource (lib "eagle-import") (part "R-US_0204/2V"))
    )
    (comp (ref "R104")
      (value "1K")
      (footprint "eagle-import:0204V")
      (libsource (lib "eagle-import") (part "R-US_0204/2V"))
    )
    (comp (ref "R105")
      (value "1K")
      (footprint "eagle-import:0204V")
      (libsource (lib "eagle-import") (part "R-US_0204/2V"))
    )
    (comp (ref "R106")
      (value "1K")
      (footprint "eagle-import:0204V")
      (libsource (lib "eagle-import") (part "R-US_0204/2V"))
    )
    (comp (ref "R107")
      (value "1K")
      (footprint "eagle-import:0204V")
      (libsource (lib "eagle-import") (part "R-US_0204/2V"))
    )
    (comp (ref "R200")
      (value "1K")
      (footprint "eagle-import:0204V")
      (libsource (lib "eagle-import") (part "R-US_0204/2V"))
    )
    (comp (ref "R201")
      (value "1K")
      (footprint "eagle-import:0204V")
      (libsource (lib "eagle-import") (part "R-US_0204/2V"))
    )
    (comp (ref "R202")
      (value "1K")
      (footprint "eagle-import:0204V")
      (libsource (lib "eagle-import") (part "R-US_0204/2V"))
    )
    (comp (ref "R203")
      (value "1K")
      (footprint "eagle-import:0204V")
      (libsource (lib "eagle-import") (part "R-US_0204/2V"))
    )
    (comp (ref "R204")
      (value "1K")
      (footprint "eagle-import:0204V")
      (libsource (lib "eagle-import") (part "R-US_0204/2V"))
    )
    (comp (ref "R205")
      (value "1K")
      (footprint "eagle-import:0204V")
      (libsource (lib "eagle-import") (part "R-US_0204/2V"))
    )
    (comp (ref "R206")
      (value "1K")
      (footprint "eagle-import:0204V")
      (libsource (lib "eagle-import") (part "R-US_0204/2V"))
    )
    (comp (ref "R207")
      (value "1K")
      (footprint "eagle-import:0204V")
      (libsource (lib "eagle-import") (part "R-US_0204/2V"))
    )
    (comp (ref "RN1")
      (value "4K7")
      (footprint "eagle-import:RN-6")
      (libsource (lib "eagle-import") (part "RN05"))
    )
    (comp (ref "S1")
      (value "DP03")
      (footprint "eagle-import:DP-03")
      (fields (field (name "MPN") "MCDP03"))
      (libsource (lib "eagle-import") (part "DP03"))
    )
    (comp (ref "S2")
      (value "RESET")
      (footprint "eagle-import:B3F-31XX")
      (fields (field (name "MPN") "B3F-3100"))
      (libsource (lib "eagle-import") (part "31-XX"))
    )
    (comp (ref "SJ1")
      (value "NO OPAMP")
      (footprint "eagle-import:SJ")
      (libsource (lib "eagle-import") (part "SJ"))
    )
    (comp (ref "SJ2") (value "SJ") (footprint "eagle-import:SJ") (libsource (lib "eagle-import") (part "SJ")))
    (comp (ref "SJ3") (value "SJ") (footprint "eagle-import:SJ") (libsource (lib "eagle-import") (part "SJ")))
    (comp (ref "SJ4") (value "SJ") (footprint "eagle-import:SJ") (libsource (lib "eagle-import") (part "SJ")))
    (comp (ref "SJ5") (value "SJ") (footprint "eagle-import:SJ") (libsource (lib "eagle-import") (part "SJ")))
    (comp (ref "SJ6") (value "SJ") (footprint "eagle-import:SJ") (libsource (lib "eagle-import") (part "SJ")))
    (comp (ref "SJ7") (value "SJ") (footprint "eagle-import:SJ") (libsource (lib "eagle-import") (part "SJ")))
    (comp (ref "SJ8") (value "SJ") (footprint "eagle-import:SJ") (libsource (lib "eagle-import") (part "SJ")))
    (comp (ref "SJ9") (value "SJ") (footprint "eagle-import:SJ") (libsource (lib "eagle-import") (part "SJ")))
    (comp (ref "U$1")
      (value "40-XX-CARBON")
      (footprint "eagle-import:CARBONB3F")
      (libsource (lib "eagle-import") (part "40-XX-CARBON"))
    )
    (comp (ref "U$2")
      (value "40-XX-CARBON")
      (footprint "eagle-import:CARBONB3F")
      (libsource (lib "eagle-import") (part "40-XX-CARBON"))
    )
    (comp (ref "U$3")
      (value "40-XX-CARBON")
      (footprint "eagle-import:CARBONB3F")
      (libsource (lib "eagle-import") (part "40-XX-CARBON"))
    )
    (comp (ref "U$4")
      (value "40-XX-CARBON")
      (footprint "eagle-import:CARBONB3F")
      (libsource (lib "eagle-import") (part "40-XX-CARBON"))
    )
    (comp (ref "U$5")
      (value "40-XX-CARBON")
      (footprint "eagle-import:CARBONB3F")
      (libsource (lib "eagle-import") (part "40-XX-CARBON"))
    )
    (comp (ref "U$6")
      (value "40-XX-CARBON")
      (footprint "eagle-import:CARBONB3F")
      (libsource (lib "eagle-import") (part "40-XX-CARBON"))
    )
    (comp (ref "U$7")
      (value "40-XX-CARBON")
      (footprint "eagle-import:CARBONB3F")
      (libsource (lib "eagle-import") (part "40-XX-CARBON"))
    )
    (comp (ref "U$8")
      (value "40-XX-CARBON")
      (footprint "eagle-import:CARBONB3F")
      (libsource (lib "eagle-import") (part "40-XX-CARBON"))
    )
    (comp (ref "U$9")
      (value "40-XX-CARBON")
      (footprint "eagle-import:CARBONB3F")
      (libsource (lib "eagle-import") (part "40-XX-CARBON"))
    )
    (comp (ref "U$10")
      (value "40-XX-CARBON")
      (footprint "eagle-import:CARBONB3F")
      (libsource (lib "eagle-import") (part "40-XX-CARBON"))
    )
    (comp (ref "U$11")
      (value "40-XX-CARBON")
      (footprint "eagle-import:CARBONB3F")
      (libsource (lib "eagle-import") (part "40-XX-CARBON"))
    )
    (comp (ref "U$12")
      (value "40-XX-CARBON")
      (footprint "eagle-import:CARBONB3F")
      (libsource (lib "eagle-import") (part "40-XX-CARBON"))
    )
    (comp (ref "U$13")
      (value "40-XX-CARBON")
      (footprint "eagle-import:CARBONB3F")
      (libsource (lib "eagle-import") (part "40-XX-CARBON"))
    )
    (comp (ref "U$14")
      (value "40-XX-CARBON")
      (footprint "eagle-import:CARBONB3F")
      (libsource (lib "eagle-import") (part "40-XX-CARBON"))
    )
    (comp (ref "U$15")
      (value "40-XX-CARBON")
      (footprint "eagle-import:CARBONB3F")
      (libsource (lib "eagle-import") (part "40-XX-CARBON"))
    )
    (comp (ref "U$16")
      (value "40-XX-CARBON")
      (footprint "eagle-import:CARBONB3F")
      (libsource (lib "eagle-import") (part "40-XX-CARBON"))
    )
    (comp (ref "U$17")
      (value "40-XX-CARBON")
      (footprint "eagle-import:CARBONB3F")
      (libsource (lib "eagle-import") (part "40-XX-CARBON"))
    )
    (comp (ref "U$18")
      (value "40-XX-CARBON")
      (footprint "eagle-import:CARBONB3F")
      (libsource (lib "eagle-import") (part "40-XX-CARBON"))
    )
    (comp (ref "U$19")
      (value "40-XX-CARBON")
      (footprint "eagle-import:CARBONB3F")
      (libsource (lib "eagle-import") (part "40-XX-CARBON"))
    )
    (comp (ref "U$20")
      (value "40-XX-CARBON")
      (footprint "eagle-import:CARBONB3F")
      (libsource (lib "eagle-import") (part "40-XX-CARBON"))
    )
    (comp (ref "U$21")
      (value "40-XX-CARBON")
      (footprint "eagle-import:CARBONB3F")
      (libsource (lib "eagle-import") (part "40-XX-CARBON"))
    )
    (comp (ref "U$22")
      (value "40-XX-CARBON")
      (footprint "eagle-import:CARBONB3F")
      (libsource (lib "eagle-import") (part "40-XX-CARBON"))
    )
    (comp (ref "U$23")
      (value "40-XX-CARBON")
      (footprint "eagle-import:CARBONB3F")
      (libsource (lib "eagle-import") (part "40-XX-CARBON"))
    )
    (comp (ref "U$24")
      (value "40-XX-CARBON")
      (footprint "eagle-import:CARBONB3F")
      (libsource (lib "eagle-import") (part "40-XX-CARBON"))
    )
    (comp (ref "U$25")
      (value "40-XX-CARBON")
      (footprint "eagle-import:CARBONB3F")
      (libsource (lib "eagle-import") (part "40-XX-CARBON"))
    )
    (comp (ref "U$26")
      (value "40-XX-CARBON")
      (footprint "eagle-import:CARBONB3F")
      (libsource (lib "eagle-import") (part "40-XX-CARBON"))
    )
    (comp (ref "U$27")
      (value "40-XX-CARBON")
      (footprint "eagle-import:CARBONB3F")
      (libsource (lib "eagle-import") (part "40-XX-CARBON"))
    )
    (comp (ref "U$28")
      (value "40-XX-CARBON")
      (footprint "eagle-import:CARBONB3F")
      (libsource (lib "eagle-import") (part "40-XX-CARBON"))
    )
    (comp (ref "U$29")
      (value "40-XX-CARBON")
      (footprint "eagle-import:CARBONB3F")
      (libsource (lib "eagle-import") (part "40-XX-CARBON"))
    )
    (comp (ref "U$30")
      (value "40-XX-CARBON")
      (footprint "eagle-import:CARBONB3F")
      (libsource (lib "eagle-import") (part "40-XX-CARBON"))
    )
    (comp (ref "U$31")
      (value "40-XX-CARBON")
      (footprint "eagle-import:CARBONB3F")
      (libsource (lib "eagle-import") (part "40-XX-CARBON"))
    )
    (comp (ref "U$32")
      (value "40-XX-CARBON")
      (footprint "eagle-import:CARBONB3F")
      (libsource (lib "eagle-import") (part "40-XX-CARBON"))
    )
    (comp (ref "U$33")
      (value "40-XX-CARBON")
      (footprint "eagle-import:CARBONB3F")
      (libsource (lib "eagle-import") (part "40-XX-CARBON"))
    )
    (comp (ref "U$34")
      (value "40-XX-CARBON")
      (footprint "eagle-import:CARBONB3F")
      (libsource (lib "eagle-import") (part "40-XX-CARBON"))
    )
    (comp (ref "U$35")
      (value "40-XX-CARBON")
      (footprint "eagle-import:CARBONB3F")
      (libsource (lib "eagle-import") (part "40-XX-CARBON"))
    )
    (comp (ref "U$36")
      (value "40-XX-CARBON")
      (footprint "eagle-import:CARBONB3F")
      (libsource (lib "eagle-import") (part "40-XX-CARBON"))
    )
    (comp (ref "U$37")
      (value "40-XX-CARBON")
      (footprint "eagle-import:CARBONB3F")
      (libsource (lib "eagle-import") (part "40-XX-CARBON"))
    )
    (comp (ref "U$38")
      (value "40-XX-CARBON")
      (footprint "eagle-import:CARBONB3F")
      (libsource (lib "eagle-import") (part "40-XX-CARBON"))
    )
    (comp (ref "U$39")
      (value "40-XX-CARBON")
      (footprint "eagle-import:CARBONB3F")
      (libsource (lib "eagle-import") (part "40-XX-CARBON"))
    )
    (comp (ref "U$40")
      (value "40-XX-CARBON")
      (footprint "eagle-import:CARBONB3F")
      (libsource (lib "eagle-import") (part "40-XX-CARBON"))
    )
    (comp (ref "U$41")
      (value "40-XX-CARBON")
      (footprint "eagle-import:CARBONB3F")
      (libsource (lib "eagle-import") (part "40-XX-CARBON"))
    )
    (comp (ref "U$42")
      (value "40-XX-CARBON")
      (footprint "eagle-import:CARBONB3F")
      (libsource (lib "eagle-import") (part "40-XX-CARBON"))
    )
    (comp (ref "U1")
      (value "7805")
      (footprint "eagle-import:TO220V")
      (libsource (lib "eagle-import") (part "78TV05"))
    )
    (comp (ref "U2")
      (value "MAX4390EUK")
      (footprint "eagle-import:SOT95P280X145-5N")
      (fields (field (name "MF") "Maxim Integrated") (field (name "MP") "MAX4390EUK+T"))
      (libsource (lib "eagle-import") (part "MAX4390EUK"))
    )
    (comp (ref "X1")
      (value "6.5MHz")
      (footprint "eagle-import:HC49U")
      (libsource (lib "eagle-import") (part "8M10AHC49T"))
    )
    (comp (ref "X2")
      (value "CON-CONRAD_736880-49")
      (footprint "eagle-import:CON-CONRAD_736880-49")
      (libsource (lib "eagle-import") (part "CON-CONRAD_736880-49"))
    )
    (comp (ref "Z0")
      (value "Z80")
      (footprint "eagle-import:DIL40")
      (libsource (lib "eagle-import") (part "Z80CPU"))
    )
    (comp (ref "Z1")
      (value "74LS74N")
      (footprint "eagle-import:DIL14")
      (libsource (lib "eagle-import") (part "7474NLS"))
    )
    (comp (ref "Z1-2")
      (value "27C512")
      (footprint "eagle-import:DIL28-6")
      (libsource (lib "eagle-import") (part "27512G"))
    )
    (comp (ref "Z3-4")
      (value "CY62256LL-PC")
      (footprint "eagle-import:DIL28-6")
      (libsource (lib "eagle-import") (part "CY62256LL-?PC"))
    )
    (comp (ref "Z5-6")
      (value "CY62256LL-PC")
      (footprint "eagle-import:DIL28-6")
      (libsource (lib "eagle-import") (part "CY62256LL-?PC"))
    )
    (comp (ref "Z7-8")
      (value "CY62256LL-PC")
      (footprint "eagle-import:DIL28-6")
      (libsource (lib "eagle-import") (part "CY62256LL-?PC"))
    )
    (comp (ref "Z9")
      (value "74LS393N")
      (footprint "eagle-import:DIL14")
      (libsource (lib "eagle-import") (part "74393NLS"))
    )
    (comp (ref "Z10")
      (value "74LS393N")
      (footprint "eagle-import:DIL14")
      (libsource (lib "eagle-import") (part "74393NLS"))
    )
    (comp (ref "Z11")
      (value "74LS393N")
      (footprint "eagle-import:DIL14")
      (libsource (lib "eagle-import") (part "74393NLS"))
    )
    (comp (ref "Z14")
      (value "74367N")
      (footprint "eagle-import:DIL16")
      (libsource (lib "eagle-import") (part "74367N"))
    )
    (comp (ref "Z15")
      (value "74367N")
      (footprint "eagle-import:DIL16")
      (libsource (lib "eagle-import") (part "74367N"))
    )
    (comp (ref "Z16")
      (value "74367N")
      (footprint "eagle-import:DIL16")
      (libsource (lib "eagle-import") (part "74367N"))
    )
    (comp (ref "Z17")
      (value "74367N")
      (footprint "eagle-import:DIL16")
      (libsource (lib "eagle-import") (part "74367N"))
    )
    (comp (ref "Z18")
      (value "74367N")
      (footprint "eagle-import:DIL16")
      (libsource (lib "eagle-import") (part "74367N"))
    )
    (comp (ref "Z19")
      (value "74LS00N")
      (footprint "eagle-import:DIL14")
      (libsource (lib "eagle-import") (part "7400NLS"))
    )
    (comp (ref "Z20")
      (value "74LS08N")
      (footprint "eagle-import:DIL14")
      (libsource (lib "eagle-import") (part "7408NLS"))
    )
    (comp (ref "Z21")
      (value "74LS11N")
      (footprint "eagle-import:DIL14")
      (libsource (lib "eagle-import") (part "7411NLS"))
    )
    (comp (ref "Z22")
      (value "74LS11N")
      (footprint "eagle-import:DIL14")
      (libsource (lib "eagle-import") (part "7411NLS"))
    )
    (comp (ref "Z23")
      (value "74LS86N")
      (footprint "eagle-import:DIL14")
      (libsource (lib "eagle-import") (part "7486NLS"))
    )
    (comp (ref "Z24")
      (value "74LS02N")
      (footprint "eagle-import:DIL14")
      (libsource (lib "eagle-import") (part "7402NLS"))
    )
    (comp (ref "Z25")
      (value "74LS02N")
      (footprint "eagle-import:DIL14")
      (libsource (lib "eagle-import") (part "7402NLS"))
    )
    (comp (ref "Z26")
      (value "74LS32N")
      (footprint "eagle-import:DIL14")
      (libsource (lib "eagle-import") (part "7432NLS"))
    )
    (comp (ref "Z27")
      (value "74LS74N")
      (footprint "eagle-import:DIL14")
      (libsource (lib "eagle-import") (part "7474NLS"))
    )
    (comp (ref "Z28")
      (value "74LS166N")
      (footprint "eagle-import:DIL16")
      (libsource (lib "eagle-import") (part "74166NLS"))
    )
    (comp (ref "Z29")
      (value "74LS138N")
      (footprint "eagle-import:DIL16")
      (libsource (lib "eagle-import") (part "74138NLS"))
    )
    (comp (ref "Z30")
      (value "74LS00N")
      (footprint "eagle-import:DIL14")
      (libsource (lib "eagle-import") (part "7400NLS"))
    )
    (comp (ref "Z31")
      (value "74LS11N")
      (footprint "eagle-import:DIL14")
      (libsource (lib "eagle-import") (part "7411NLS"))
    )
    (comp (ref "Z40")
      (value "ATF16V8BP3")
      (footprint "eagle-import:DIL20")
      (fields (field (name "MPN") "ATF16V8CZ-15PU"))
      (libsource (lib "eagle-import") (part "ATF16V8BP3"))
    )
    (comp (ref "Z41")
      (value "74LS00N")
      (footprint "eagle-import:DIL14")
      (libsource (lib "eagle-import") (part "7400NLS"))
    )
  )
  (nets
    (net (code "3") (name "/9V") (class "Default")
      (node (ref "3A") (pin "1") (pinfunction "P_1") (pintype "passive"))
      (node (ref "C10") (pin "1") (pinfunction "1_1") (pintype "passive"))
      (node (ref "C11") (pin "+") (pinfunction "+_+") (pintype "passive"))
      (node (ref "C9") (pin "+") (pinfunction "+_+") (pintype "passive"))
      (node (ref "JP7") (pin "1") (pinfunction "1_1") (pintype "passive"))
      (node (ref "U1") (pin "1") (pinfunction "VI_1") (pintype "input"))
    )
    (net (code "4") (name "/A0") (class "Default")
      (node (ref "19A") (pin "1") (pinfunction "P_1") (pintype "passive"))
      (node (ref "Z0") (pin "30") (pinfunction "A0_30") (pintype "output"))
      (node (ref "Z1-2") (pin "10") (pinfunction "A0_10") (pintype "input"))
      (node (ref "Z15") (pin "2") (pinfunction "1A1_2") (pintype "input"))
      (node (ref "Z18") (pin "10") (pinfunction "1A4_10") (pintype "input"))
      (node (ref "Z26") (pin "5") (pinfunction "I1_5") (pintype "input"))
      (node (ref "Z3-4") (pin "21") (pinfunction "A0_21") (pintype "input"))
    )
    (net (code "5") (name "/A1") (class "Default")
      (node (ref "19B") (pin "1") (pinfunction "P_1") (pintype "passive"))
      (node (ref "Z0") (pin "31") (pinfunction "A1_31") (pintype "output"))
      (node (ref "Z1-2") (pin "9") (pinfunction "A1_9") (pintype "input"))
      (node (ref "Z15") (pin "4") (pinfunction "1A2_4") (pintype "input"))
      (node (ref "Z18") (pin "6") (pinfunction "1A3_6") (pintype "input"))
      (node (ref "Z3-4") (pin "23") (pinfunction "A1_23") (pintype "input"))
    )
    (net (code "6") (name "/A2") (class "Default")
      (node (ref "14A") (pin "1") (pinfunction "P_1") (pintype "passive"))
      (node (ref "Z0") (pin "32") (pinfunction "A2_32") (pintype "output"))
      (node (ref "Z1-2") (pin "8") (pinfunction "A2_8") (pintype "input"))
      (node (ref "Z15") (pin "6") (pinfunction "1A3_6") (pintype "input"))
      (node (ref "Z18") (pin "4") (pinfunction "1A2_4") (pintype "input"))
      (node (ref "Z3-4") (pin "24") (pinfunction "A2_24") (pintype "input"))
    )
    (net (code "7") (name "/A3") (class "Default")
      (node (ref "18B") (pin "1") (pinfunction "P_1") (pintype "passive"))
      (node (ref "Z0") (pin "33") (pinfunction "A3_33") (pintype "output"))
      (node (ref "Z1-2") (pin "7") (pinfunction "A3_7") (pintype "input"))
      (node (ref "Z15") (pin "10") (pinfunction "1A4_10") (pintype "input"))
      (node (ref "Z18") (pin "2") (pinfunction "1A1_2") (pintype "input"))
      (node (ref "Z3-4") (pin "25") (pinfunction "A3_25") (pintype "input"))
    )
    (net (code "8") (name "/A4") (class "Default")
      (node (ref "17B") (pin "1") (pinfunction "P_1") (pintype "passive"))
      (node (ref "Z0") (pin "34") (pinfunction "A4_34") (pintype "output"))
      (node (ref "Z1-2") (pin "6") (pinfunction "A4_6") (pintype "input"))
      (node (ref "Z15") (pin "12") (pinfunction "2A1_12") (pintype "input"))
      (node (ref "Z17") (pin "14") (pinfunction "2A2_14") (pintype "input"))
      (node (ref "Z3-4") (pin "26") (pinfunction "A4_26") (pintype "input"))
    )
    (net (code "9") (name "/A5") (class "Default")
      (node (ref "16B") (pin "1") (pinfunction "P_1") (pintype "passive"))
      (node (ref "Z0") (pin "35") (pinfunction "A5_35") (pintype "output"))
      (node (ref "Z1-2") (pin "5") (pinfunction "A5_5") (pintype "input"))
      (node (ref "Z15") (pin "14") (pinfunction "2A2_14") (pintype "input"))
      (node (ref "Z17") (pin "12") (pinfunction "2A1_12") (pintype "input"))
      (node (ref "Z3-4") (pin "1") (pinfunction "A5_1") (pintype "input"))
    )
    (net (code "10") (name "/A6") (class "Default")
      (node (ref "15B") (pin "1") (pinfunction "P_1") (pintype "passive"))
      (node (ref "Z0") (pin "36") (pinfunction "A6_36") (pintype "output"))
      (node (ref "Z1-2") (pin "4") (pinfunction "A6_4") (pintype "input"))
      (node (ref "Z16") (pin "2") (pinfunction "1A1_2") (pintype "input"))
      (node (ref "Z17") (pin "10") (pinfunction "1A4_10") (pintype "input"))
      (node (ref "Z3-4") (pin "2") (pinfunction "A6_2") (pintype "input"))
    )
    (net (code "11") (name "/A7") (class "Default")
      (node (ref "18A") (pin "1") (pinfunction "P_1") (pintype "passive"))
      (node (ref "Z0") (pin "37") (pinfunction "A7_37") (pintype "output"))
      (node (ref "Z1-2") (pin "3") (pinfunction "A7_3") (pintype "input"))
      (node (ref "Z16") (pin "4") (pinfunction "1A2_4") (pintype "input"))
      (node (ref "Z17") (pin "6") (pinfunction "1A3_6") (pintype "input"))
      (node (ref "Z3-4") (pin "3") (pinfunction "A7_3") (pintype "input"))
    )
    (net (code "12") (name "/A8") (class "Default")
      (node (ref "17A") (pin "1") (pinfunction "P_1") (pintype "passive"))
      (node (ref "D10") (pin "C") (pinfunction "C_C") (pintype "passive"))
      (node (ref "Z0") (pin "38") (pinfunction "A8_38") (pintype "output"))
      (node (ref "Z1-2") (pin "25") (pinfunction "A8_25") (pintype "input"))
      (node (ref "Z16") (pin "6") (pinfunction "1A3_6") (pintype "input"))
      (node (ref "Z17") (pin "4") (pinfunction "1A2_4") (pintype "input"))
      (node (ref "Z3-4") (pin "4") (pinfunction "A8_4") (pintype "input"))
    )
    (net (code "13") (name "/A9") (class "Default")
      (node (ref "16A") (pin "1") (pinfunction "P_1") (pintype "passive"))
      (node (ref "D9") (pin "C") (pinfunction "C_C") (pintype "passive"))
      (node (ref "Z0") (pin "39") (pinfunction "A9_39") (pintype "output"))
      (node (ref "Z1-2") (pin "24") (pinfunction "A9_24") (pintype "input"))
      (node (ref "Z16") (pin "10") (pinfunction "1A4_10") (pintype "input"))
      (node (ref "Z17") (pin "2") (pinfunction "1A1_2") (pintype "input"))
      (node (ref "Z3-4") (pin "5") (pinfunction "A9_5") (pintype "input"))
    )
    (net (code "14") (name "/A10") (class "Default")
      (node (ref "15A") (pin "1") (pinfunction "P_1") (pintype "passive"))
      (node (ref "D8") (pin "C") (pinfunction "C_C") (pintype "passive"))
      (node (ref "Z0") (pin "40") (pinfunction "A10_40") (pintype "output"))
      (node (ref "Z1-2") (pin "21") (pinfunction "A10_21") (pintype "input"))
      (node (ref "Z19") (pin "9") (pinfunction "I0_9") (pintype "input"))
      (node (ref "Z30") (pin "9") (pinfunction "I0_9") (pintype "input"))
    )
    (net (code "15") (name "/A10'") (class "Default")
      (node (ref "Z3-4") (pin "6") (pinfunction "A10_6") (pintype "input"))
      (node (ref "Z30") (pin "8") (pinfunction "O_8") (pintype "output"))
    )
    (net (code "16") (name "/A11") (class "Default")
      (node (ref "6A") (pin "1") (pinfunction "P_1") (pintype "passive"))
      (node (ref "D7") (pin "C") (pinfunction "C_C") (pintype "passive"))
      (node (ref "Z0") (pin "1") (pinfunction "A11_1") (pintype "output"))
      (node (ref "Z1-2") (pin "23") (pinfunction "A11_23") (pintype "input"))
      (node (ref "Z24") (pin "6") (pinfunction "I1_6") (pintype "input"))
      (node (ref "Z30") (pin "12") (pinfunction "I0_12") (pintype "input"))
    )
    (net (code "17") (name "/A11'") (class "Default")
      (node (ref "Z3-4") (pin "7") (pinfunction "A11_7") (pintype "input"))
      (node (ref "Z30") (pin "11") (pinfunction "O_11") (pintype "output"))
    )
    (net (code "18") (name "/A12") (class "Default")
      (node (ref "7A") (pin "1") (pinfunction "P_1") (pintype "passive"))
      (node (ref "D6") (pin "C") (pinfunction "C_C") (pintype "passive"))
      (node (ref "Z0") (pin "2") (pinfunction "A12_2") (pintype "output"))
      (node (ref "Z1-2") (pin "2") (pinfunction "A12_2") (pintype "input"))
      (node (ref "Z29") (pin "1") (pinfunction "A_1") (pintype "input"))
      (node (ref "Z3-4") (pin "8") (pinfunction "A12_8") (pintype "input"))
    )
    (net (code "19") (name "/A13") (class "Default")
      (node (ref "8A") (pin "1") (pinfunction "P_1") (pintype "passive"))
      (node (ref "D5") (pin "C") (pinfunction "C_C") (pintype "passive"))
      (node (ref "Z0") (pin "3") (pinfunction "A13_3") (pintype "output"))
      (node (ref "Z29") (pin "2") (pinfunction "B_2") (pintype "input"))
      (node (ref "Z3-4") (pin "9") (pinfunction "A13_9") (pintype "input"))
    )
    (net (code "20") (name "/A14") (class "Default")
      (node (ref "9A") (pin "1") (pinfunction "P_1") (pintype "passive"))
      (node (ref "D4") (pin "C") (pinfunction "C_C") (pintype "passive"))
      (node (ref "Z0") (pin "4") (pinfunction "A14_4") (pintype "output"))
      (node (ref "Z29") (pin "3") (pinfunction "C_3") (pintype "input"))
      (node (ref "Z3-4") (pin "10") (pinfunction "A14_10") (pintype "input"))
      (node (ref "Z30") (pin "10") (pinfunction "I1_10") (pintype "input"))
      (node (ref "Z30") (pin "13") (pinfunction "I1_13") (pintype "input"))
    )
    (net (code "21") (name "/A15") (class "Default")
      (node (ref "10A") (pin "1") (pinfunction "P_1") (pintype "passive"))
      (node (ref "D3") (pin "C") (pinfunction "C_C") (pintype "passive"))
      (node (ref "Z0") (pin "5") (pinfunction "A15_5") (pintype "output"))
      (node (ref "Z29") (pin "5") (pinfunction "G2B_5") (pintype "input"))
    )
    (net (code "22") (name "/ACE81_ENABLED") (class "Default")
      (node (ref "R29") (pin "2") (pinfunction "2_2") (pintype "passive"))
      (node (ref "R42") (pin "2") (pinfunction "2_2") (pintype "passive"))
      (node (ref "R43") (pin "2") (pinfunction "2_2") (pintype "passive"))
      (node (ref "S1") (pin "6") (pinfunction "6_6") (pintype "passive"))
      (node (ref "Z1-2") (pin "1") (pinfunction "A15_1") (pintype "input"))
      (node (ref "Z40") (pin "1") (pinfunction "CLK_1") (pintype "input"))
    )
    (net (code "23") (name "/CLK") (class "Default")
      (node (ref "C22") (pin "2") (pinfunction "2_2") (pintype "passive"))
      (node (ref "Z20") (pin "10") (pinfunction "I1_10") (pintype "input"))
      (node (ref "Z23") (pin "8") (pinfunction "O_8") (pintype "output"))
      (node (ref "Z28") (pin "7") (pinfunction "CLK_7") (pintype "input"))
      (node (ref "Z9") (pin "1") (pinfunction "A_1") (pintype "input"))
    )
    (net (code "24") (name "/CNT0") (class "Default")
      (node (ref "Z22") (pin "5") (pinfunction "I2_5") (pintype "input"))
      (node (ref "Z30") (pin "4") (pinfunction "I0_4") (pintype "input"))
      (node (ref "Z30") (pin "5") (pinfunction "I1_5") (pintype "input"))
      (node (ref "Z9") (pin "3") (pinfunction "QA_3") (pintype "output"))
    )
    (net (code "25") (name "/CNT1") (class "Default")
      (node (ref "Z22") (pin "4") (pinfunction "I1_4") (pintype "input"))
      (node (ref "Z9") (pin "4") (pinfunction "QB_4") (pintype "output"))
    )
    (net (code "26") (name "/CNT2") (class "Default")
      (node (ref "Z22") (pin "3") (pinfunction "I0_3") (pintype "input"))
      (node (ref "Z41") (pin "5") (pinfunction "I1_5") (pintype "input"))
      (node (ref "Z9") (pin "5") (pinfunction "QC_5") (pintype "output"))
    )
    (net (code "27") (name "/CNT3") (class "Default")
      (node (ref "JP5") (pin "1") (pinfunction "1_1") (pintype "passive"))
      (node (ref "Z9") (pin "13") (pinfunction "A_13") (pintype "input"))
      (node (ref "Z9") (pin "6") (pinfunction "QD_6") (pintype "output"))
    )
    (net (code "28") (name "/CNT4") (class "Default")
      (node (ref "JP10") (pin "1") (pinfunction "1_1") (pintype "passive"))
      (node (ref "Z10") (pin "1") (pinfunction "A_1") (pintype "input"))
      (node (ref "Z9") (pin "11") (pinfunction "QA_11") (pintype "output"))
    )
    (net (code "29") (name "/CNT5") (class "Default")
      (node (ref "JP10") (pin "3") (pinfunction "1_3") (pintype "passive"))
      (node (ref "Z10") (pin "3") (pinfunction "QA_3") (pintype "output"))
      (node (ref "Z21") (pin "11") (pinfunction "I2_11") (pintype "input"))
      (node (ref "Z25") (pin "11") (pinfunction "I0_11") (pintype "input"))
      (node (ref "Z41") (pin "2") (pinfunction "I1_2") (pintype "input"))
    )
    (net (code "30") (name "/CNT6") (class "Default")
      (node (ref "JP10") (pin "5") (pinfunction "1_5") (pintype "passive"))
      (node (ref "Z10") (pin "4") (pinfunction "QB_4") (pintype "output"))
      (node (ref "Z22") (pin "1") (pinfunction "I0_1") (pintype "input"))
    )
    (net (code "31") (name "/CNT7") (class "Default")
      (node (ref "JP10") (pin "7") (pinfunction "1_7") (pintype "passive"))
      (node (ref "Z10") (pin "5") (pinfunction "QC_5") (pintype "output"))
      (node (ref "Z21") (pin "10") (pinfunction "I1_10") (pintype "input"))
      (node (ref "Z25") (pin "12") (pinfunction "I1_12") (pintype "input"))
    )
    (net (code "32") (name "/CNT8") (class "Default")
      (node (ref "Z10") (pin "13") (pinfunction "A_13") (pintype "input"))
      (node (ref "Z10") (pin "6") (pinfunction "QD_6") (pintype "output"))
      (node (ref "Z21") (pin "9") (pinfunction "I0_9") (pintype "input"))
      (node (ref "Z22") (pin "13") (pinfunction "I2_13") (pintype "input"))
      (node (ref "Z25") (pin "2") (pinfunction "I0_2") (pintype "input"))
    )
    (net (code "33") (name "/CNT9") (class "Default")
      (node (ref "R21") (pin "1") (pinfunction "1_1") (pintype "passive"))
      (node (ref "Z10") (pin "11") (pinfunction "QA_11") (pintype "output"))
    )
    (net (code "34") (name "/CNT10") (class "Default")
      (node (ref "R22") (pin "1") (pinfunction "1_1") (pintype "passive"))
      (node (ref "Z10") (pin "10") (pinfunction "QB_10") (pintype "output"))
    )
    (net (code "35") (name "/CNT11") (class "Default")
      (node (ref "R23") (pin "1") (pinfunction "1_1") (pintype "passive"))
      (node (ref "Z10") (pin "9") (pinfunction "QC_9") (pintype "output"))
      (node (ref "Z11") (pin "1") (pinfunction "A_1") (pintype "input"))
    )
    (net (code "36") (name "/CNT12") (class "Default")
      (node (ref "JP15") (pin "1") (pinfunction "1_1") (pintype "passive"))
      (node (ref "Z11") (pin "3") (pinfunction "QA_3") (pintype "output"))
      (node (ref "Z21") (pin "3") (pinfunction "I0_3") (pintype "input"))
    )
    (net (code "37") (name "/CNT13") (class "Default")
      (node (ref "JP15") (pin "3") (pinfunction "1_3") (pintype "passive"))
      (node (ref "Z11") (pin "4") (pinfunction "QB_4") (pintype "output"))
      (node (ref "Z21") (pin "4") (pinfunction "I1_4") (pintype "input"))
    )
    (net (code "38") (name "/CNT14") (class "Default")
      (node (ref "JP15") (pin "5") (pinfunction "1_5") (pintype "passive"))
      (node (ref "Z11") (pin "5") (pinfunction "QC_5") (pintype "output"))
      (node (ref "Z21") (pin "5") (pinfunction "I2_5") (pintype "input"))
    )
    (net (code "39") (name "/CNT15") (class "Default")
      (node (ref "JP15") (pin "7") (pinfunction "1_7") (pintype "passive"))
      (node (ref "Z11") (pin "13") (pinfunction "A_13") (pintype "input"))
      (node (ref "Z11") (pin "6") (pinfunction "QD_6") (pintype "output"))
      (node (ref "Z19") (pin "1") (pinfunction "I0_1") (pintype "input"))
      (node (ref "Z21") (pin "1") (pinfunction "I0_1") (pintype "input"))
    )
    (net (code "40") (name "/CNT16") (class "Default")
      (node (ref "JP15") (pin "9") (pinfunction "1_9") (pintype "passive"))
      (node (ref "Z11") (pin "11") (pinfunction "QA_11") (pintype "output"))
      (node (ref "Z19") (pin "2") (pinfunction "I1_2") (pintype "input"))
      (node (ref "Z21") (pin "2") (pinfunction "I1_2") (pintype "input"))
    )
    (net (code "41") (name "/CNT17") (class "Default")
      (node (ref "Z11") (pin "10") (pinfunction "QB_10") (pintype "output"))
      (node (ref "Z20") (pin "2") (pinfunction "I1_2") (pintype "input"))
      (node (ref "Z25") (pin "3") (pinfunction "I1_3") (pintype "input"))
    )
    (net (code "42") (name "/D0") (class "Default")
      (node (ref "20B") (pin "1") (pinfunction "P_1") (pintype "passive"))
      (node (ref "R100") (pin "1") (pinfunction "1_1") (pintype "passive"))
      (node (ref "R200") (pin "1") (pinfunction "1_1") (pintype "passive"))
      (node (ref "Z0") (pin "14") (pinfunction "D0_14") (pintype "bidirectional"))
      (node (ref "Z1-2") (pin "11") (pinfunction "I/O0_11") (pintype "tri_state"))
      (node (ref "Z14") (pin "3") (pinfunction "1Y1_3") (pintype "tri_state"))
      (node (ref "Z3-4") (pin "11") (pinfunction "DQ0_11") (pintype "bidirectional"))
    )
    (net (code "43") (name "/D1") (class "Default")
      (node (ref "20A") (pin "1") (pinfunction "P_1") (pintype "passive"))
      (node (ref "R101") (pin "1") (pinfunction "1_1") (pintype "passive"))
      (node (ref "R201") (pin "1") (pinfunction "1_1") (pintype "passive"))
      (node (ref "Z0") (pin "15") (pinfunction "D1_15") (pintype "bidirectional"))
      (node (ref "Z1-2") (pin "12") (pinfunction "I/O1_12") (pintype "tri_state"))
      (node (ref "Z14") (pin "5") (pinfunction "1Y2_5") (pintype "tri_state"))
      (node (ref "Z3-4") (pin "12") (pinfunction "DQ1_12") (pintype "bidirectional"))
    )
    (net (code "44") (name "/D2") (class "Default")
      (node (ref "21B") (pin "1") (pinfunction "P_1") (pintype "passive"))
      (node (ref "R102") (pin "1") (pinfunction "1_1") (pintype "passive"))
      (node (ref "R202") (pin "1") (pinfunction "1_1") (pintype "passive"))
      (node (ref "Z0") (pin "12") (pinfunction "D2_12") (pintype "bidirectional"))
      (node (ref "Z1-2") (pin "13") (pinfunction "I/O2_13") (pintype "tri_state"))
      (node (ref "Z14") (pin "7") (pinfunction "1Y3_7") (pintype "tri_state"))
      (node (ref "Z3-4") (pin "13") (pinfunction "DQ2_13") (pintype "bidirectional"))
    )
    (net (code "45") (name "/D3") (class "Default")
      (node (ref "12A") (pin "1") (pinfunction "P_1") (pintype "passive"))
      (node (ref "R103") (pin "1") (pinfunction "1_1") (pintype "passive"))
      (node (ref "R203") (pin "1") (pinfunction "1_1") (pintype "passive"))
      (node (ref "Z0") (pin "8") (pinfunction "D3_8") (pintype "bidirectional"))
      (node (ref "Z1-2") (pin "15") (pinfunction "I/O3_15") (pintype "tri_state"))
      (node (ref "Z14") (pin "9") (pinfunction "1Y4_9") (pintype "tri_state"))
      (node (ref "Z27") (pin "2") (pinfunction "D_2") (pintype "input"))
      (node (ref "Z3-4") (pin "15") (pinfunction "DQ3_15") (pintype "bidirectional"))
    )
    (net (code "46") (name "/D4") (class "Default")
      (node (ref "11A") (pin "1") (pinfunction "P_1") (pintype "passive"))
      (node (ref "R104") (pin "1") (pinfunction "1_1") (pintype "passive"))
      (node (ref "R204") (pin "1") (pinfunction "1_1") (pintype "passive"))
      (node (ref "Z0") (pin "7") (pinfunction "D4_7") (pintype "bidirectional"))
      (node (ref "Z1-2") (pin "16") (pinfunction "I/O4_16") (pintype "tri_state"))
      (node (ref "Z14") (pin "11") (pinfunction "2Y1_11") (pintype "tri_state"))
      (node (ref "Z3-4") (pin "16") (pinfunction "DQ4_16") (pintype "bidirectional"))
    )
    (net (code "47") (name "/D5") (class "Default")
      (node (ref "13A") (pin "1") (pinfunction "P_1") (pintype "passive"))
      (node (ref "R105") (pin "1") (pinfunction "1_1") (pintype "passive"))
      (node (ref "R205") (pin "1") (pinfunction "1_1") (pintype "passive"))
      (node (ref "Z0") (pin "9") (pinfunction "D5_9") (pintype "bidirectional"))
      (node (ref "Z1-2") (pin "17") (pinfunction "I/O5_17") (pintype "tri_state"))
      (node (ref "Z14") (pin "13") (pinfunction "2Y2_13") (pintype "tri_state"))
      (node (ref "Z3-4") (pin "17") (pinfunction "DQ5_17") (pintype "bidirectional"))
    )
    (net (code "48") (name "/D6") (class "Default")
      (node (ref "21A") (pin "1") (pinfunction "P_1") (pintype "passive"))
      (node (ref "R106") (pin "1") (pinfunction "1_1") (pintype "passive"))
      (node (ref "R206") (pin "1") (pinfunction "1_1") (pintype "passive"))
      (node (ref "Z0") (pin "10") (pinfunction "D6_10") (pintype "bidirectional"))
      (node (ref "Z1-2") (pin "18") (pinfunction "I/O6_18") (pintype "tri_state"))
      (node (ref "Z3-4") (pin "18") (pinfunction "DQ6_18") (pintype "bidirectional"))
    )
    (net (code "49") (name "/D7") (class "Default")
      (node (ref "22B") (pin "1") (pinfunction "P_1") (pintype "passive"))
      (node (ref "R107") (pin "1") (pinfunction "1_1") (pintype "passive"))
      (node (ref "R207") (pin "1") (pinfunction "1_1") (pintype "passive"))
      (node (ref "Z0") (pin "13") (pinfunction "D7_13") (pintype "bidirectional"))
      (node (ref "Z1-2") (pin "19") (pinfunction "I/O7_19") (pintype "tri_state"))
      (node (ref "Z3-4") (pin "19") (pinfunction "DQ7_19") (pintype "bidirectional"))
    )
    (net (code "50") (name "/EAR") (class "Default")
      (node (ref "Z14") (pin "14") (pinfunction "2A2_14") (pintype "input"))
      (node (ref "Z18") (pin "13") (pinfunction "2Y2_13") (pintype "tri_state"))
    )
    (net (code "51") (name "/FIELD") (class "Default")
      (node (ref "Z19") (pin "12") (pinfunction "I0_12") (pintype "input"))
      (node (ref "Z21") (pin "12") (pinfunction "O_12") (pintype "output"))
      (node (ref "Z25") (pin "6") (pinfunction "I1_6") (pintype "input"))
    )
    (net (code "52") (name "/KB") (class "Default")
      (node (ref "K37") (pin "3") (pinfunction "P_3") (pintype "passive"))
      (node (ref "K37") (pin "4") (pinfunction "P1_4") (pintype "passive"))
      (node (ref "SJ4") (pin "1") (pinfunction "1_1") (pintype "passive"))
      (node (ref "SJ7") (pin "2") (pinfunction "2_2") (pintype "passive"))
      (node (ref "U$37") (pin "P$2") (pinfunction "2_P$2") (pintype "passive"))
      (node (ref "Z40") (pin "4") (pinfunction "I3_4") (pintype "input"))
    )
    (net (code "53") (name "/KC") (class "Default")
      (node (ref "K35") (pin "3") (pinfunction "P_3") (pintype "passive"))
      (node (ref "K35") (pin "4") (pinfunction "P1_4") (pintype "passive"))
      (node (ref "SJ5") (pin "1") (pinfunction "1_1") (pintype "passive"))
      (node (ref "U$35") (pin "P$2") (pinfunction "2_P$2") (pintype "passive"))
      (node (ref "Z40") (pin "5") (pinfunction "I4_5") (pintype "input"))
    )
    (net (code "54") (name "/KEYB1") (class "Default")
      (node (ref "K1") (pin "3") (pinfunction "P_3") (pintype "passive"))
      (node (ref "K1") (pin "4") (pinfunction "P1_4") (pintype "passive"))
      (node (ref "K10") (pin "3") (pinfunction "P_3") (pintype "passive"))
      (node (ref "K10") (pin "4") (pinfunction "P1_4") (pintype "passive"))
      (node (ref "K11") (pin "3") (pinfunction "P_3") (pintype "passive"))
      (node (ref "K11") (pin "4") (pinfunction "P1_4") (pintype "passive"))
      (node (ref "K20") (pin "3") (pinfunction "P_3") (pintype "passive"))
      (node (ref "K20") (pin "4") (pinfunction "P1_4") (pintype "passive"))
      (node (ref "K21") (pin "3") (pinfunction "P_3") (pintype "passive"))
      (node (ref "K21") (pin "4") (pinfunction "P1_4") (pintype "passive"))
      (node (ref "K30") (pin "3") (pinfunction "P_3") (pintype "passive"))
      (node (ref "K30") (pin "4") (pinfunction "P1_4") (pintype "passive"))
      (node (ref "K31") (pin "3") (pinfunction "P_3") (pintype "passive"))
      (node (ref "K31") (pin "4") (pinfunction "P1_4") (pintype "passive"))
      (node (ref "K40") (pin "3") (pinfunction "P_3") (pintype "passive"))
      (node (ref "K40") (pin "4") (pinfunction "P1_4") (pintype "passive"))
      (node (ref "K41") (pin "3") (pinfunction "P_3") (pintype "passive"))
      (node (ref "K41") (pin "4") (pinfunction "P1_4") (pintype "passive"))
      (node (ref "R36") (pin "1") (pinfunction "1_1") (pintype "passive"))
      (node (ref "RN1") (pin "6") (pinfunction "6_6") (pintype "passive"))
      (node (ref "U$1") (pin "P$2") (pinfunction "2_P$2") (pintype "passive"))
      (node (ref "U$10") (pin "P$2") (pinfunction "2_P$2") (pintype "passive"))
      (node (ref "U$11") (pin "P$2") (pinfunction "2_P$2") (pintype "passive"))
      (node (ref "U$20") (pin "P$2") (pinfunction "2_P$2") (pintype "passive"))
      (node (ref "U$21") (pin "P$2") (pinfunction "2_P$2") (pintype "passive"))
      (node (ref "U$30") (pin "P$2") (pinfunction "2_P$2") (pintype "passive"))
      (node (ref "U$31") (pin "P$2") (pinfunction "2_P$2") (pintype "passive"))
      (node (ref "U$40") (pin "P$2") (pinfunction "2_P$2") (pintype "passive"))
      (node (ref "U$41") (pin "P$2") (pinfunction "2_P$2") (pintype "passive"))
      (node (ref "U$42") (pin "P$2") (pinfunction "2_P$2") (pintype "passive"))
      (node (ref "Z14") (pin "2") (pinfunction "1A1_2") (pintype "input"))
    )
    (net (code "55") (name "/KEYB2") (class "Default")
      (node (ref "D14") (pin "A") (pinfunction "A_A") (pintype "passive"))
      (node (ref "K12") (pin "3") (pinfunction "P_3") (pintype "passive"))
      (node (ref "K12") (pin "4") (pinfunction "P1_4") (pintype "passive"))
      (node (ref "K19") (pin "3") (pinfunction "P_3") (pintype "passive"))
      (node (ref "K19") (pin "4") (pinfunction "P1_4") (pintype "passive"))
      (node (ref "K2") (pin "3") (pinfunction "P_3") (pintype "passive"))
      (node (ref "K2") (pin "4") (pinfunction "P1_4") (pintype "passive"))
      (node (ref "K22") (pin "3") (pinfunction "P_3") (pintype "passive"))
      (node (ref "K22") (pin "4") (pinfunction "P1_4") (pintype "passive"))
      (node (ref "K29") (pin "3") (pinfunction "P_3") (pintype "passive"))
      (node (ref "K29") (pin "4") (pinfunction "P1_4") (pintype "passive"))
      (node (ref "K32") (pin "3") (pinfunction "P_3") (pintype "passive"))
      (node (ref "K32") (pin "4") (pinfunction "P1_4") (pintype "passive"))
      (node (ref "K9") (pin "3") (pinfunction "P_3") (pintype "passive"))
      (node (ref "K9") (pin "4") (pinfunction "P1_4") (pintype "passive"))
      (node (ref "R37") (pin "1") (pinfunction "1_1") (pintype "passive"))
      (node (ref "RN1") (pin "5") (pinfunction "5_5") (pintype "passive"))
      (node (ref "U$12") (pin "P$2") (pinfunction "2_P$2") (pintype "passive"))
      (node (ref "U$19") (pin "P$2") (pinfunction "2_P$2") (pintype "passive"))
      (node (ref "U$2") (pin "P$2") (pinfunction "2_P$2") (pintype "passive"))
      (node (ref "U$22") (pin "P$2") (pinfunction "2_P$2") (pintype "passive"))
      (node (ref "U$29") (pin "P$2") (pinfunction "2_P$2") (pintype "passive"))
      (node (ref "U$32") (pin "P$2") (pinfunction "2_P$2") (pintype "passive"))
      (node (ref "U$9") (pin "P$2") (pinfunction "2_P$2") (pintype "passive"))
      (node (ref "Z14") (pin "4") (pinfunction "1A2_4") (pintype "input"))
    )
    (net (code "56") (name "/KEYB3") (class "Default")
      (node (ref "D15") (pin "A") (pinfunction "A_A") (pintype "passive"))
      (node (ref "K13") (pin "3") (pinfunction "P_3") (pintype "passive"))
      (node (ref "K13") (pin "4") (pinfunction "P1_4") (pintype "passive"))
      (node (ref "K18") (pin "3") (pinfunction "P_3") (pintype "passive"))
      (node (ref "K18") (pin "4") (pinfunction "P1_4") (pintype "passive"))
      (node (ref "K23") (pin "3") (pinfunction "P_3") (pintype "passive"))
      (node (ref "K23") (pin "4") (pinfunction "P1_4") (pintype "passive"))
      (node (ref "K28") (pin "3") (pinfunction "P_3") (pintype "passive"))
      (node (ref "K28") (pin "4") (pinfunction "P1_4") (pintype "passive"))
      (node (ref "K3") (pin "3") (pinfunction "P_3") (pintype "passive"))
      (node (ref "K3") (pin "4") (pinfunction "P1_4") (pintype "passive"))
      (node (ref "K8") (pin "3") (pinfunction "P_3") (pintype "passive"))
      (node (ref "K8") (pin "4") (pinfunction "P1_4") (pintype "passive"))
      (node (ref "R38") (pin "1") (pinfunction "1_1") (pintype "passive"))
      (node (ref "RN1") (pin "4") (pinfunction "4_4") (pintype "passive"))
      (node (ref "U$13") (pin "P$2") (pinfunction "2_P$2") (pintype "passive"))
      (node (ref "U$18") (pin "P$2") (pinfunction "2_P$2") (pintype "passive"))
      (node (ref "U$23") (pin "P$2") (pinfunction "2_P$2") (pintype "passive"))
      (node (ref "U$28") (pin "P$2") (pinfunction "2_P$2") (pintype "passive"))
      (node (ref "U$3") (pin "P$2") (pinfunction "2_P$2") (pintype "passive"))
      (node (ref "U$8") (pin "P$2") (pinfunction "2_P$2") (pintype "passive"))
      (node (ref "Z14") (pin "6") (pinfunction "1A3_6") (pintype "input"))
    )
    (net (code "57") (name "/KEYB4") (class "Default")
      (node (ref "D16") (pin "A") (pinfunction "A_A") (pintype "passive"))
      (node (ref "K14") (pin "3") (pinfunction "P_3") (pintype "passive"))
      (node (ref "K14") (pin "4") (pinfunction "P1_4") (pintype "passive"))
      (node (ref "K17") (pin "3") (pinfunction "P_3") (pintype "passive"))
      (node (ref "K17") (pin "4") (pinfunction "P1_4") (pintype "passive"))
      (node (ref "K24") (pin "3") (pinfunction "P_3") (pintype "passive"))
      (node (ref "K24") (pin "4") (pinfunction "P1_4") (pintype "passive"))
      (node (ref "K27") (pin "3") (pinfunction "P_3") (pintype "passive"))
      (node (ref "K27") (pin "4") (pinfunction "P1_4") (pintype "passive"))
      (node (ref "K4") (pin "3") (pinfunction "P_3") (pintype "passive"))
      (node (ref "K4") (pin "4") (pinfunction "P1_4") (pintype "passive"))
      (node (ref "K7") (pin "3") (pinfunction "P_3") (pintype "passive"))
      (node (ref "K7") (pin "4") (pinfunction "P1_4") (pintype "passive"))
      (node (ref "R40") (pin "1") (pinfunction "1_1") (pintype "passive"))
      (node (ref "RN1") (pin "3") (pinfunction "3_3") (pintype "passive"))
      (node (ref "U$14") (pin "P$2") (pinfunction "2_P$2") (pintype "passive"))
      (node (ref "U$17") (pin "P$2") (pinfunction "2_P$2") (pintype "passive"))
      (node (ref "U$24") (pin "P$2") (pinfunction "2_P$2") (pintype "passive"))
      (node (ref "U$27") (pin "P$2") (pinfunction "2_P$2") (pintype "passive"))
      (node (ref "U$4") (pin "P$2") (pinfunction "2_P$2") (pintype "passive"))
      (node (ref "U$7") (pin "P$2") (pinfunction "2_P$2") (pintype "passive"))
      (node (ref "Z14") (pin "10") (pinfunction "1A4_10") (pintype "input"))
    )
    (net (code "58") (name "/KEYB5") (class "Default")
      (node (ref "D17") (pin "A") (pinfunction "A_A") (pintype "passive"))
      (node (ref "K15") (pin "3") (pinfunction "P_3") (pintype "passive"))
      (node (ref "K15") (pin "4") (pinfunction "P1_4") (pintype "passive"))
      (node (ref "K16") (pin "3") (pinfunction "P_3") (pintype "passive"))
      (node (ref "K16") (pin "4") (pinfunction "P1_4") (pintype "passive"))
      (node (ref "K25") (pin "3") (pinfunction "P_3") (pintype "passive"))
      (node (ref "K25") (pin "4") (pinfunction "P1_4") (pintype "passive"))
      (node (ref "K26") (pin "3") (pinfunction "P_3") (pintype "passive"))
      (node (ref "K26") (pin "4") (pinfunction "P1_4") (pintype "passive"))
      (node (ref "K36") (pin "3") (pinfunction "P_3") (pintype "passive"))
      (node (ref "K36") (pin "4") (pinfunction "P1_4") (pintype "passive"))
      (node (ref "K5") (pin "3") (pinfunction "P_3") (pintype "passive"))
      (node (ref "K5") (pin "4") (pinfunction "P1_4") (pintype "passive"))
      (node (ref "K6") (pin "3") (pinfunction "P_3") (pintype "passive"))
      (node (ref "K6") (pin "4") (pinfunction "P1_4") (pintype "passive"))
      (node (ref "R41") (pin "1") (pinfunction "1_1") (pintype "passive"))
      (node (ref "RN1") (pin "2") (pinfunction "2_2") (pintype "passive"))
      (node (ref "U$15") (pin "P$2") (pinfunction "2_P$2") (pintype "passive"))
      (node (ref "U$16") (pin "P$2") (pinfunction "2_P$2") (pintype "passive"))
      (node (ref "U$25") (pin "P$2") (pinfunction "2_P$2") (pintype "passive"))
      (node (ref "U$26") (pin "P$2") (pinfunction "2_P$2") (pintype "passive"))
      (node (ref "U$36") (pin "P$2") (pinfunction "2_P$2") (pintype "passive"))
      (node (ref "U$5") (pin "P$2") (pinfunction "2_P$2") (pintype "passive"))
      (node (ref "U$6") (pin "P$2") (pinfunction "2_P$2") (pintype "passive"))
      (node (ref "Z14") (pin "12") (pinfunction "2A1_12") (pintype "input"))
    )
    (net (code "59") (name "/KM") (class "Default")
      (node (ref "K39") (pin "3") (pinfunction "P_3") (pintype "passive"))
      (node (ref "K39") (pin "4") (pinfunction "P1_4") (pintype "passive"))
      (node (ref "SJ2") (pin "1") (pinfunction "1_1") (pintype "passive"))
      (node (ref "U$39") (pin "P$2") (pinfunction "2_P$2") (pintype "passive"))
      (node (ref "Z40") (pin "2") (pinfunction "I1_2") (pintype "input"))
    )
    (net (code "60") (name "/KN") (class "Default")
      (node (ref "K38") (pin "3") (pinfunction "P_3") (pintype "passive"))
      (node (ref "K38") (pin "4") (pinfunction "P1_4") (pintype "passive"))
      (node (ref "SJ3") (pin "1") (pinfunction "1_1") (pintype "passive"))
      (node (ref "SJ6") (pin "1") (pinfunction "1_1") (pintype "passive"))
      (node (ref "U$38") (pin "P$2") (pinfunction "2_P$2") (pintype "passive"))
      (node (ref "Z40") (pin "3") (pinfunction "I2_3") (pintype "input"))
    )
    (net (code "61") (name "/KX") (class "Default")
      (node (ref "K34") (pin "3") (pinfunction "P_3") (pintype "passive"))
      (node (ref "K34") (pin "4") (pinfunction "P1_4") (pintype "passive"))
      (node (ref "SJ7") (pin "1") (pinfunction "1_1") (pintype "passive"))
      (node (ref "U$34") (pin "P$2") (pinfunction "2_P$2") (pintype "passive"))
      (node (ref "Z40") (pin "6") (pinfunction "I5_6") (pintype "input"))
    )
    (net (code "62") (name "/KZ") (class "Default")
      (node (ref "K33") (pin "3") (pinfunction "P_3") (pintype "passive"))
      (node (ref "K33") (pin "4") (pinfunction "P1_4") (pintype "passive"))
      (node (ref "SJ6") (pin "2") (pinfunction "2_2") (pintype "passive"))
      (node (ref "U$33") (pin "P$2") (pinfunction "2_P$2") (pintype "passive"))
      (node (ref "Z40") (pin "7") (pinfunction "I6_7") (pintype "input"))
    )
    (net (code "63") (name "/LINE") (class "Default")
      (node (ref "Z22") (pin "12") (pinfunction "O_12") (pintype "output"))
      (node (ref "Z25") (pin "5") (pinfunction "I0_5") (pintype "input"))
    )
    (net (code "64") (name "/N$56") (class "Default")
      (node (ref "JP6") (pin "2") (pinfunction "2_2") (pintype "passive"))
      (node (ref "R42") (pin "1") (pinfunction "1_1") (pintype "passive"))
    )
    (net (code "65") (name "/NC1") (class "Default")
      (node (ref "24A") (pin "1") (pinfunction "P_1") (pintype "passive"))
    )
    (net (code "66") (name "/NC2") (class "Default")
      (node (ref "25A") (pin "1") (pinfunction "P_1") (pintype "passive"))
    )
    (net (code "67") (name "/NC3") (class "Default")
      (node (ref "24B") (pin "1") (pinfunction "P_1") (pintype "passive"))
    )
    (net (code "68") (name "/NC4") (class "Default")
      (node (ref "25B") (pin "1") (pinfunction "P_1") (pintype "passive"))
    )
    (net (code "69") (name "/PHI") (class "Default")
      (node (ref "5A") (pin "1") (pinfunction "P_1") (pintype "passive"))
      (node (ref "Z0") (pin "6") (pinfunction "CLK_6") (pintype "input"))
      (node (ref "Z30") (pin "6") (pinfunction "O_6") (pintype "output"))
    )
    (net (code "70") (name "/RESET") (class "Default")
      (node (ref "12B") (pin "1") (pinfunction "P_1") (pintype "passive"))
      (node (ref "C7") (pin "+") (pinfunction "+_+") (pintype "passive"))
      (node (ref "R25") (pin "1") (pinfunction "1_1") (pintype "passive"))
      (node (ref "S2") (pin "2") (pinfunction "S_2") (pintype "passive"))
      (node (ref "Z0") (pin "26") (pinfunction "RESET_26") (pintype "input"))
    )
    (net (code "71") (name "/ROW1") (class "Default")
      (node (ref "D10") (pin "A") (pinfunction "A_A") (pintype "passive"))
      (node (ref "JP1") (pin "1") (pinfunction "1_1") (pintype "passive"))
      (node (ref "K31") (pin "1") (pinfunction "S_1") (pintype "passive"))
      (node (ref "K31") (pin "2") (pinfunction "S1_2") (pintype "passive"))
      (node (ref "K33") (pin "1") (pinfunction "S_1") (pintype "passive"))
      (node (ref "K33") (pin "2") (pinfunction "S1_2") (pintype "passive"))
      (node (ref "K34") (pin "1") (pinfunction "S_1") (pintype "passive"))
      (node (ref "K34") (pin "2") (pinfunction "S1_2") (pintype "passive"))
      (node (ref "K35") (pin "1") (pinfunction "S_1") (pintype "passive"))
      (node (ref "K35") (pin "2") (pinfunction "S1_2") (pintype "passive"))
      (node (ref "R30") (pin "2") (pinfunction "2_2") (pintype "passive"))
      (node (ref "SJ8") (pin "1") (pinfunction "1_1") (pintype "passive"))
      (node (ref "U$31") (pin "P$1") (pinfunction "1_P$1") (pintype "passive"))
      (node (ref "U$33") (pin "P$1") (pinfunction "1_P$1") (pintype "passive"))
      (node (ref "U$34") (pin "P$1") (pinfunction "1_P$1") (pintype "passive"))
      (node (ref "U$35") (pin "P$1") (pinfunction "1_P$1") (pintype "passive"))
      (node (ref "Z40") (pin "8") (pinfunction "I7_8") (pintype "input"))
    )
    (net (code "72") (name "/ROW2") (class "Default")
      (node (ref "D9") (pin "A") (pinfunction "A_A") (pintype "passive"))
      (node (ref "JP1") (pin "2") (pinfunction "2_2") (pintype "passive"))
      (node (ref "K21") (pin "1") (pinfunction "S_1") (pintype "passive"))
      (node (ref "K21") (pin "2") (pinfunction "S1_2") (pintype "passive"))
      (node (ref "K22") (pin "1") (pinfunction "S_1") (pintype "passive"))
      (node (ref "K22") (pin "2") (pinfunction "S1_2") (pintype "passive"))
      (node (ref "K23") (pin "1") (pinfunction "S_1") (pintype "passive"))
      (node (ref "K23") (pin "2") (pinfunction "S1_2") (pintype "passive"))
      (node (ref "K24") (pin "1") (pinfunction "S_1") (pintype "passive"))
      (node (ref "K24") (pin "2") (pinfunction "S1_2") (pintype "passive"))
      (node (ref "K25") (pin "1") (pinfunction "S_1") (pintype "passive"))
      (node (ref "K25") (pin "2") (pinfunction "S1_2") (pintype "passive"))
      (node (ref "U$21") (pin "P$1") (pinfunction "1_P$1") (pintype "passive"))
      (node (ref "U$22") (pin "P$1") (pinfunction "1_P$1") (pintype "passive"))
      (node (ref "U$23") (pin "P$1") (pinfunction "1_P$1") (pintype "passive"))
      (node (ref "U$24") (pin "P$1") (pinfunction "1_P$1") (pintype "passive"))
      (node (ref "U$25") (pin "P$1") (pinfunction "1_P$1") (pintype "passive"))
    )
    (net (code "73") (name "/ROW3") (class "Default")
      (node (ref "D8") (pin "A") (pinfunction "A_A") (pintype "passive"))
      (node (ref "JP1") (pin "3") (pinfunction "3_3") (pintype "passive"))
      (node (ref "K11") (pin "1") (pinfunction "S_1") (pintype "passive"))
      (node (ref "K11") (pin "2") (pinfunction "S1_2") (pintype "passive"))
      (node (ref "K12") (pin "1") (pinfunction "S_1") (pintype "passive"))
      (node (ref "K12") (pin "2") (pinfunction "S1_2") (pintype "passive"))
      (node (ref "K13") (pin "1") (pinfunction "S_1") (pintype "passive"))
      (node (ref "K13") (pin "2") (pinfunction "S1_2") (pintype "passive"))
      (node (ref "K14") (pin "1") (pinfunction "S_1") (pintype "passive"))
      (node (ref "K14") (pin "2") (pinfunction "S1_2") (pintype "passive"))
      (node (ref "K15") (pin "1") (pinfunction "S_1") (pintype "passive"))
      (node (ref "K15") (pin "2") (pinfunction "S1_2") (pintype "passive"))
      (node (ref "U$11") (pin "P$1") (pinfunction "1_P$1") (pintype "passive"))
      (node (ref "U$12") (pin "P$1") (pinfunction "1_P$1") (pintype "passive"))
      (node (ref "U$13") (pin "P$1") (pinfunction "1_P$1") (pintype "passive"))
      (node (ref "U$14") (pin "P$1") (pinfunction "1_P$1") (pintype "passive"))
      (node (ref "U$15") (pin "P$1") (pinfunction "1_P$1") (pintype "passive"))
    )
    (net (code "74") (name "/ROW4") (class "Default")
      (node (ref "D7") (pin "A") (pinfunction "A_A") (pintype "passive"))
      (node (ref "JP1") (pin "4") (pinfunction "4_4") (pintype "passive"))
      (node (ref "K1") (pin "1") (pinfunction "S_1") (pintype "passive"))
      (node (ref "K1") (pin "2") (pinfunction "S1_2") (pintype "passive"))
      (node (ref "K2") (pin "1") (pinfunction "S_1") (pintype "passive"))
      (node (ref "K2") (pin "2") (pinfunction "S1_2") (pintype "passive"))
      (node (ref "K3") (pin "1") (pinfunction "S_1") (pintype "passive"))
      (node (ref "K3") (pin "2") (pinfunction "S1_2") (pintype "passive"))
      (node (ref "K4") (pin "1") (pinfunction "S_1") (pintype "passive"))
      (node (ref "K4") (pin "2") (pinfunction "S1_2") (pintype "passive"))
      (node (ref "K5") (pin "1") (pinfunction "S_1") (pintype "passive"))
      (node (ref "K5") (pin "2") (pinfunction "S1_2") (pintype "passive"))
      (node (ref "U$1") (pin "P$1") (pinfunction "1_P$1") (pintype "passive"))
      (node (ref "U$2") (pin "P$1") (pinfunction "1_P$1") (pintype "passive"))
      (node (ref "U$3") (pin "P$1") (pinfunction "1_P$1") (pintype "passive"))
      (node (ref "U$4") (pin "P$1") (pinfunction "1_P$1") (pintype "passive"))
      (node (ref "U$5") (pin "P$1") (pinfunction "1_P$1") (pintype "passive"))
    )
    (net (code "75") (name "/ROW5") (class "Default")
      (node (ref "D6") (pin "A") (pinfunction "A_A") (pintype "passive"))
      (node (ref "JP1") (pin "5") (pinfunction "5_5") (pintype "passive"))
      (node (ref "K10") (pin "1") (pinfunction "S_1") (pintype "passive"))
      (node (ref "K10") (pin "2") (pinfunction "S1_2") (pintype "passive"))
      (node (ref "K6") (pin "1") (pinfunction "S_1") (pintype "passive"))
      (node (ref "K6") (pin "2") (pinfunction "S1_2") (pintype "passive"))
      (node (ref "K7") (pin "1") (pinfunction "S_1") (pintype "passive"))
      (node (ref "K7") (pin "2") (pinfunction "S1_2") (pintype "passive"))
      (node (ref "K8") (pin "1") (pinfunction "S_1") (pintype "passive"))
      (node (ref "K8") (pin "2") (pinfunction "S1_2") (pintype "passive"))
      (node (ref "K9") (pin "1") (pinfunction "S_1") (pintype "passive"))
      (node (ref "K9") (pin "2") (pinfunction "S1_2") (pintype "passive"))
      (node (ref "U$10") (pin "P$1") (pinfunction "1_P$1") (pintype "passive"))
      (node (ref "U$6") (pin "P$1") (pinfunction "1_P$1") (pintype "passive"))
      (node (ref "U$7") (pin "P$1") (pinfunction "1_P$1") (pintype "passive"))
      (node (ref "U$8") (pin "P$1") (pinfunction "1_P$1") (pintype "passive"))
      (node (ref "U$9") (pin "P$1") (pinfunction "1_P$1") (pintype "passive"))
    )
    (net (code "76") (name "/ROW6") (class "Default")
      (node (ref "D5") (pin "A") (pinfunction "A_A") (pintype "passive"))
      (node (ref "JP1") (pin "6") (pinfunction "6_6") (pintype "passive"))
      (node (ref "K16") (pin "1") (pinfunction "S_1") (pintype "passive"))
      (node (ref "K16") (pin "2") (pinfunction "S1_2") (pintype "passive"))
      (node (ref "K17") (pin "1") (pinfunction "S_1") (pintype "passive"))
      (node (ref "K17") (pin "2") (pinfunction "S1_2") (pintype "passive"))
      (node (ref "K18") (pin "1") (pinfunction "S_1") (pintype "passive"))
      (node (ref "K18") (pin "2") (pinfunction "S1_2") (pintype "passive"))
      (node (ref "K19") (pin "1") (pinfunction "S_1") (pintype "passive"))
      (node (ref "K19") (pin "2") (pinfunction "S1_2") (pintype "passive"))
      (node (ref "K20") (pin "1") (pinfunction "S_1") (pintype "passive"))
      (node (ref "K20") (pin "2") (pinfunction "S1_2") (pintype "passive"))
      (node (ref "U$16") (pin "P$1") (pinfunction "1_P$1") (pintype "passive"))
      (node (ref "U$17") (pin "P$1") (pinfunction "1_P$1") (pintype "passive"))
      (node (ref "U$18") (pin "P$1") (pinfunction "1_P$1") (pintype "passive"))
      (node (ref "U$19") (pin "P$1") (pinfunction "1_P$1") (pintype "passive"))
      (node (ref "U$20") (pin "P$1") (pinfunction "1_P$1") (pintype "passive"))
    )
    (net (code "77") (name "/ROW7") (class "Default")
      (node (ref "D4") (pin "A") (pinfunction "A_A") (pintype "passive"))
      (node (ref "JP1") (pin "7") (pinfunction "7_7") (pintype "passive"))
      (node (ref "K26") (pin "1") (pinfunction "S_1") (pintype "passive"))
      (node (ref "K26") (pin "2") (pinfunction "S1_2") (pintype "passive"))
      (node (ref "K27") (pin "1") (pinfunction "S_1") (pintype "passive"))
      (node (ref "K27") (pin "2") (pinfunction "S1_2") (pintype "passive"))
      (node (ref "K28") (pin "1") (pinfunction "S_1") (pintype "passive"))
      (node (ref "K28") (pin "2") (pinfunction "S1_2") (pintype "passive"))
      (node (ref "K29") (pin "1") (pinfunction "S_1") (pintype "passive"))
      (node (ref "K29") (pin "2") (pinfunction "S1_2") (pintype "passive"))
      (node (ref "K30") (pin "1") (pinfunction "S_1") (pintype "passive"))
      (node (ref "K30") (pin "2") (pinfunction "S1_2") (pintype "passive"))
      (node (ref "U$26") (pin "P$1") (pinfunction "1_P$1") (pintype "passive"))
      (node (ref "U$27") (pin "P$1") (pinfunction "1_P$1") (pintype "passive"))
      (node (ref "U$28") (pin "P$1") (pinfunction "1_P$1") (pintype "passive"))
      (node (ref "U$29") (pin "P$1") (pinfunction "1_P$1") (pintype "passive"))
      (node (ref "U$30") (pin "P$1") (pinfunction "1_P$1") (pintype "passive"))
    )
    (net (code "78") (name "/ROW8") (class "Default")
      (node (ref "D3") (pin "A") (pinfunction "A_A") (pintype "passive"))
      (node (ref "JP1") (pin "8") (pinfunction "8_8") (pintype "passive"))
      (node (ref "K37") (pin "1") (pinfunction "S_1") (pintype "passive"))
      (node (ref "K37") (pin "2") (pinfunction "S1_2") (pintype "passive"))
      (node (ref "K38") (pin "1") (pinfunction "S_1") (pintype "passive"))
      (node (ref "K38") (pin "2") (pinfunction "S1_2") (pintype "passive"))
      (node (ref "K39") (pin "1") (pinfunction "S_1") (pintype "passive"))
      (node (ref "K39") (pin "2") (pinfunction "S1_2") (pintype "passive"))
      (node (ref "K40") (pin "1") (pinfunction "S_1") (pintype "passive"))
      (node (ref "K40") (pin "2") (pinfunction "S1_2") (pintype "passive"))
      (node (ref "K41") (pin "1") (pinfunction "S_1") (pintype "passive"))
      (node (ref "K41") (pin "2") (pinfunction "S1_2") (pintype "passive"))
      (node (ref "R31") (pin "2") (pinfunction "2_2") (pintype "passive"))
      (node (ref "SJ9") (pin "1") (pinfunction "1_1") (pintype "passive"))
      (node (ref "U$37") (pin "P$1") (pinfunction "1_P$1") (pintype "passive"))
      (node (ref "U$38") (pin "P$1") (pinfunction "1_P$1") (pintype "passive"))
      (node (ref "U$39") (pin "P$1") (pinfunction "1_P$1") (pintype "passive"))
      (node (ref "U$40") (pin "P$1") (pinfunction "1_P$1") (pintype "passive"))
      (node (ref "U$41") (pin "P$1") (pinfunction "1_P$1") (pintype "passive"))
      (node (ref "U$42") (pin "P$1") (pinfunction "1_P$1") (pintype "passive"))
      (node (ref "Z40") (pin "9") (pinfunction "I8_9") (pintype "input"))
    )
    (net (code "79") (name "/ROW_SS") (class "Default")
      (node (ref "D13") (pin "A") (pinfunction "A_A") (pintype "passive"))
      (node (ref "K32") (pin "1") (pinfunction "S_1") (pintype "passive"))
      (node (ref "K32") (pin "2") (pinfunction "S1_2") (pintype "passive"))
      (node (ref "U$32") (pin "P$1") (pinfunction "1_P$1") (pintype "passive"))
    )
    (net (code "80") (name "/ROW_V") (class "Default")
      (node (ref "D12") (pin "A") (pinfunction "A_A") (pintype "passive"))
      (node (ref "K36") (pin "1") (pinfunction "S_1") (pintype "passive"))
      (node (ref "K36") (pin "2") (pinfunction "S1_2") (pintype "passive"))
      (node (ref "U$36") (pin "P$1") (pinfunction "1_P$1") (pintype "passive"))
    )
    (net (code "81") (name "/SYNC") (class "Default")
      (node (ref "D1") (pin "C") (pinfunction "C_C") (pintype "passive"))
      (node (ref "Z1") (pin "13") (pinfunction "CLR_13") (pintype "input"))
      (node (ref "Z25") (pin "4") (pinfunction "O_4") (pintype "output"))
    )
    (net (code "82") (name "/VA0") (class "Default")
      (node (ref "1A1") (pin "1") (pinfunction "P_1") (pintype "passive"))
      (node (ref "R11") (pin "2") (pinfunction "2_2") (pintype "passive"))
      (node (ref "Z15") (pin "3") (pinfunction "1Y1_3") (pintype "tri_state"))
      (node (ref "Z5-6") (pin "21") (pinfunction "A0_21") (pintype "input"))
    )
    (net (code "83") (name "/VA1") (class "Default")
      (node (ref "9A1") (pin "1") (pinfunction "P_1") (pintype "passive"))
      (node (ref "R12") (pin "2") (pinfunction "2_2") (pintype "passive"))
      (node (ref "Z15") (pin "5") (pinfunction "1Y2_5") (pintype "tri_state"))
      (node (ref "Z5-6") (pin "23") (pinfunction "A1_23") (pintype "input"))
    )
    (net (code "84") (name "/VA2") (class "Default")
      (node (ref "6B2") (pin "1") (pinfunction "P_1") (pintype "passive"))
      (node (ref "R13") (pin "2") (pinfunction "2_2") (pintype "passive"))
      (node (ref "Z15") (pin "7") (pinfunction "1Y3_7") (pintype "tri_state"))
      (node (ref "Z5-6") (pin "24") (pinfunction "A2_24") (pintype "input"))
    )
    (net (code "85") (name "/VA3") (class "Default")
      (node (ref "1B1") (pin "1") (pinfunction "P_1") (pintype "passive"))
      (node (ref "R14") (pin "2") (pinfunction "2_2") (pintype "passive"))
      (node (ref "Z15") (pin "9") (pinfunction "1Y4_9") (pintype "tri_state"))
      (node (ref "Z5-6") (pin "25") (pinfunction "A3_25") (pintype "input"))
    )
    (net (code "86") (name "/VA4") (class "Default")
      (node (ref "2A1") (pin "1") (pinfunction "P_1") (pintype "passive"))
      (node (ref "R15") (pin "2") (pinfunction "2_2") (pintype "passive"))
      (node (ref "Z15") (pin "11") (pinfunction "2Y1_11") (pintype "tri_state"))
      (node (ref "Z5-6") (pin "26") (pinfunction "A4_26") (pintype "input"))
    )
    (net (code "87") (name "/VA5") (class "Default")
      (node (ref "2B1") (pin "1") (pinfunction "P_1") (pintype "passive"))
      (node (ref "R16") (pin "2") (pinfunction "2_2") (pintype "passive"))
      (node (ref "Z15") (pin "13") (pinfunction "2Y2_13") (pintype "tri_state"))
      (node (ref "Z5-6") (pin "1") (pinfunction "A5_1") (pintype "input"))
    )
    (net (code "88") (name "/VA6") (class "Default")
      (node (ref "5B2") (pin "1") (pinfunction "P_1") (pintype "passive"))
      (node (ref "R17") (pin "2") (pinfunction "2_2") (pintype "passive"))
      (node (ref "Z16") (pin "3") (pinfunction "1Y1_3") (pintype "tri_state"))
      (node (ref "Z5-6") (pin "2") (pinfunction "A6_2") (pintype "input"))
    )
    (net (code "89") (name "/VA7") (class "Default")
      (node (ref "8A1") (pin "1") (pinfunction "P_1") (pintype "passive"))
      (node (ref "R18") (pin "2") (pinfunction "2_2") (pintype "passive"))
      (node (ref "Z16") (pin "5") (pinfunction "1Y2_5") (pintype "tri_state"))
      (node (ref "Z5-6") (pin "3") (pinfunction "A7_3") (pintype "input"))
    )
    (net (code "90") (name "/VA8") (class "Default")
      (node (ref "8B2") (pin "1") (pinfunction "P_1") (pintype "passive"))
      (node (ref "R19") (pin "2") (pinfunction "2_2") (pintype "passive"))
      (node (ref "Z16") (pin "7") (pinfunction "1Y3_7") (pintype "tri_state"))
      (node (ref "Z5-6") (pin "4") (pinfunction "A8_4") (pintype "input"))
    )
    (net (code "91") (name "/VA9") (class "Default")
      (node (ref "9B1") (pin "1") (pinfunction "P_1") (pintype "passive"))
      (node (ref "R20") (pin "2") (pinfunction "2_2") (pintype "passive"))
      (node (ref "Z16") (pin "9") (pinfunction "1Y4_9") (pintype "tri_state"))
      (node (ref "Z5-6") (pin "5") (pinfunction "A9_5") (pintype "input"))
    )
    (net (code "92") (name "/VD0") (class "Default")
      (node (ref "5A1") (pin "1") (pinfunction "P_1") (pintype "passive"))
      (node (ref "R100") (pin "2") (pinfunction "2_2") (pintype "passive"))
      (node (ref "Z18") (pin "3") (pinfunction "1Y1_3") (pintype "tri_state"))
      (node (ref "Z5-6") (pin "11") (pinfunction "DQ0_11") (pintype "bidirectional"))
      (node (ref "Z7-8") (pin "25") (pinfunction "A3_25") (pintype "input"))
    )
    (net (code "93") (name "/VD1") (class "Default")
      (node (ref "4B2") (pin "1") (pinfunction "P_1") (pintype "passive"))
      (node (ref "R101") (pin "2") (pinfunction "2_2") (pintype "passive"))
      (node (ref "Z17") (pin "13") (pinfunction "2Y2_13") (pintype "tri_state"))
      (node (ref "Z5-6") (pin "12") (pinfunction "DQ1_12") (pintype "bidirectional"))
      (node (ref "Z7-8") (pin "26") (pinfunction "A4_26") (pintype "input"))
    )
    (net (code "94") (name "/VD2") (class "Default")
      (node (ref "3B1") (pin "1") (pinfunction "P_1") (pintype "passive"))
      (node (ref "R102") (pin "2") (pinfunction "2_2") (pintype "passive"))
      (node (ref "Z17") (pin "11") (pinfunction "2Y1_11") (pintype "tri_state"))
      (node (ref "Z5-6") (pin "13") (pinfunction "DQ2_13") (pintype "bidirectional"))
      (node (ref "Z7-8") (pin "1") (pinfunction "A5_1") (pintype "input"))
    )
    (net (code "95") (name "/VD3") (class "Default")
      (node (ref "3A1") (pin "1") (pinfunction "P_1") (pintype "passive"))
      (node (ref "R103") (pin "2") (pinfunction "2_2") (pintype "passive"))
      (node (ref "Z17") (pin "9") (pinfunction "1Y4_9") (pintype "tri_state"))
      (node (ref "Z5-6") (pin "15") (pinfunction "DQ3_15") (pintype "bidirectional"))
      (node (ref "Z7-8") (pin "2") (pinfunction "A6_2") (pintype "input"))
    )
    (net (code "96") (name "/VD4") (class "Default")
      (node (ref "4A1") (pin "1") (pinfunction "P_1") (pintype "passive"))
      (node (ref "R104") (pin "2") (pinfunction "2_2") (pintype "passive"))
      (node (ref "Z17") (pin "7") (pinfunction "1Y3_7") (pintype "tri_state"))
      (node (ref "Z5-6") (pin "16") (pinfunction "DQ4_16") (pintype "bidirectional"))
      (node (ref "Z7-8") (pin "3") (pinfunction "A7_3") (pintype "input"))
    )
    (net (code "97") (name "/VD5") (class "Default")
      (node (ref "7A1") (pin "1") (pinfunction "P_1") (pintype "passive"))
      (node (ref "R105") (pin "2") (pinfunction "2_2") (pintype "passive"))
      (node (ref "Z17") (pin "5") (pinfunction "1Y2_5") (pintype "tri_state"))
      (node (ref "Z5-6") (pin "17") (pinfunction "DQ5_17") (pintype "bidirectional"))
      (node (ref "Z7-8") (pin "4") (pinfunction "A8_4") (pintype "input"))
    )
    (net (code "98") (name "/VD6") (class "Default")
      (node (ref "10B1") (pin "1") (pinfunction "P_1") (pintype "passive"))
      (node (ref "R106") (pin "2") (pinfunction "2_2") (pintype "passive"))
      (node (ref "Z17") (pin "3") (pinfunction "1Y1_3") (pintype "tri_state"))
      (node (ref "Z5-6") (pin "18") (pinfunction "DQ6_18") (pintype "bidirectional"))
      (node (ref "Z7-8") (pin "5") (pinfunction "A9_5") (pintype "input"))
    )
    (net (code "99") (name "/VD7") (class "Default")
      (node (ref "6A1") (pin "1") (pinfunction "P_1") (pintype "passive"))
      (node (ref "R107") (pin "2") (pinfunction "2_2") (pintype "passive"))
      (node (ref "Z20") (pin "13") (pinfunction "I1_13") (pintype "input"))
      (node (ref "Z5-6") (pin "19") (pinfunction "DQ7_19") (pintype "bidirectional"))
    )
    (net (code "100") (name "/VIDEN") (class "Default")
      (node (ref "Z19") (pin "10") (pinfunction "I1_10") (pintype "input"))
      (node (ref "Z19") (pin "5") (pinfunction "I1_5") (pintype "input"))
      (node (ref "Z20") (pin "12") (pinfunction "I0_12") (pintype "input"))
      (node (ref "Z20") (pin "6") (pinfunction "O_6") (pintype "output"))
    )
    (net (code "101") (name "/VIDEO") (class "Default")
      (node (ref "13B1") (pin "1") (pinfunction "P_1") (pintype "passive"))
      (node (ref "14B1") (pin "1") (pinfunction "P_1") (pintype "passive"))
      (node (ref "15B1") (pin "1") (pinfunction "P_1") (pintype "passive"))
      (node (ref "R34") (pin "1") (pinfunction "1_1") (pintype "passive"))
      (node (ref "SJ1") (pin "1") (pinfunction "1_1") (pintype "passive"))
      (node (ref "X2") (pin "2") (pinfunction "1_2") (pintype "passive"))
      (node (ref "X2") (pin "2@2") (pinfunction "2_2@2") (pintype "passive"))
    )
    (net (code "104") (name "/{slash}BUSAK") (class "Default")
      (node (ref "9B") (pin "1") (pinfunction "P_1") (pintype "passive"))
      (node (ref "Z0") (pin "23") (pinfunction "BUSAK_23") (pintype "output"))
    )
    (net (code "105") (name "/{slash}BUSRQ") (class "Default")
      (node (ref "11B") (pin "1") (pinfunction "P_1") (pintype "passive"))
      (node (ref "R24") (pin "1") (pinfunction "1_1") (pintype "passive"))
      (node (ref "Z0") (pin "25") (pinfunction "BUSRQ_25") (pintype "input"))
    )
    (net (code "106") (name "/{slash}HALT") (class "Default")
      (node (ref "4B") (pin "1") (pinfunction "P_1") (pintype "passive"))
      (node (ref "Z0") (pin "18") (pinfunction "HALT_18") (pintype "output"))
    )
    (net (code "107") (name "/{slash}INT") (class "Default")
      (node (ref "2B") (pin "1") (pinfunction "P_1") (pintype "passive"))
      (node (ref "Z0") (pin "16") (pinfunction "INT_16") (pintype "input"))
      (node (ref "Z19") (pin "11") (pinfunction "O_11") (pintype "output"))
    )
    (net (code "108") (name "/{slash}IORQ") (class "Default")
      (node (ref "6B") (pin "1") (pinfunction "P_1") (pintype "passive"))
      (node (ref "Z0") (pin "20") (pinfunction "IORQ_20") (pintype "output"))
      (node (ref "Z26") (pin "4") (pinfunction "I0_4") (pintype "input"))
    )
    (net (code "109") (name "/{slash}M1") (class "Default")
      (node (ref "13B") (pin "1") (pinfunction "P_1") (pintype "passive"))
      (node (ref "Z0") (pin "27") (pinfunction "M1_27") (pintype "output"))
    )
    (net (code "110") (name "/{slash}MREQ") (class "Default")
      (node (ref "5B") (pin "1") (pinfunction "P_1") (pintype "passive"))
      (node (ref "Z0") (pin "19") (pinfunction "MREQ_19") (pintype "output"))
      (node (ref "Z29") (pin "4") (pinfunction "G2A_4") (pintype "input"))
    )
    (net (code "111") (name "/{slash}NMI") (class "Default")
      (node (ref "3B") (pin "1") (pinfunction "P_1") (pintype "passive"))
      (node (ref "R39") (pin "1") (pinfunction "1_1") (pintype "passive"))
      (node (ref "Z0") (pin "17") (pinfunction "NMI_17") (pintype "input"))
    )
    (net (code "112") (name "/{slash}RD") (class "Default")
      (node (ref "7B") (pin "1") (pinfunction "P_1") (pintype "passive"))
      (node (ref "Z0") (pin "21") (pinfunction "RD_21") (pintype "output"))
      (node (ref "Z26") (pin "10") (pinfunction "I1_10") (pintype "input"))
      (node (ref "Z3-4") (pin "22") (pinfunction "~{OE}_22") (pintype "input"))
    )
    (net (code "113") (name "/{slash}RFSH") (class "Default")
      (node (ref "14B") (pin "1") (pinfunction "P_1") (pintype "passive"))
      (node (ref "Z0") (pin "28") (pinfunction "RFSH_28") (pintype "output"))
    )
    (net (code "114") (name "/{slash}VHOLD") (class "Default")
      (node (ref "Z16") (pin "15") (pinfunction "2G_15") (pintype "input"))
      (node (ref "Z19") (pin "8") (pinfunction "O_8") (pintype "output"))
      (node (ref "Z26") (pin "1") (pinfunction "I0_1") (pintype "input"))
    )
    (net (code "115") (name "/{slash}WAIT") (class "Default")
      (node (ref "10B") (pin "1") (pinfunction "P_1") (pintype "passive"))
      (node (ref "C8") (pin "1") (pinfunction "1_1") (pintype "passive"))
      (node (ref "Z0") (pin "24") (pinfunction "WAIT_24") (pintype "input"))
      (node (ref "Z26") (pin "3") (pinfunction "O_3") (pintype "output"))
    )
    (net (code "116") (name "/{slash}WE1") (class "Default")
      (node (ref "22A") (pin "1") (pinfunction "P_1") (pintype "passive"))
      (node (ref "7B2") (pin "1") (pinfunction "P_1") (pintype "passive"))
      (node (ref "Z26") (pin "11") (pinfunction "O_11") (pintype "output"))
      (node (ref "Z30") (pin "1") (pinfunction "I0_1") (pintype "input"))
      (node (ref "Z30") (pin "2") (pinfunction "I1_2") (pintype "input"))
      (node (ref "Z5-6") (pin "27") (pinfunction "~{WE}_27") (pintype "input"))
      (node (ref "Z7-8") (pin "27") (pinfunction "~{WE}_27") (pintype "input"))
    )
    (net (code "117") (name "/{slash}WR") (class "Default")
      (node (ref "8B") (pin "1") (pinfunction "P_1") (pintype "passive"))
      (node (ref "Z0") (pin "22") (pinfunction "WR_22") (pintype "output"))
      (node (ref "Z25") (pin "9") (pinfunction "I1_9") (pintype "input"))
      (node (ref "Z26") (pin "12") (pinfunction "I0_12") (pintype "input"))
      (node (ref "Z3-4") (pin "27") (pinfunction "~{WE}_27") (pintype "input"))
    )
    (net (code "118") (name "GND") (class "Default")
      (node (ref "11A1") (pin "1") (pinfunction "P_1") (pintype "passive"))
      (node (ref "13A1") (pin "1") (pinfunction "P_1") (pintype "passive"))
      (node (ref "14A1") (pin "1") (pinfunction "P_1") (pintype "passive"))
      (node (ref "15A1") (pin "1") (pinfunction "P_1") (pintype "passive"))
      (node (ref "1A") (pin "1") (pinfunction "P_1") (pintype "passive"))
      (node (ref "1B") (pin "1") (pinfunction "P_1") (pintype "passive"))
      (node (ref "26A") (pin "1") (pinfunction "P_1") (pintype "passive"))
      (node (ref "26B") (pin "1") (pinfunction "P_1") (pintype "passive"))
      (node (ref "27A") (pin "1") (pinfunction "P_1") (pintype "passive"))
      (node (ref "27B") (pin "1") (pinfunction "P_1") (pintype "passive"))
      (node (ref "28A") (pin "1") (pinfunction "P_1") (pintype "passive"))
      (node (ref "28B") (pin "1") (pinfunction "P_1") (pintype "passive"))
      (node (ref "2A") (pin "1") (pinfunction "P_1") (pintype "passive"))
      (node (ref "C10") (pin "2") (pinfunction "2_2") (pintype "passive"))
      (node (ref "C11") (pin "-") (pinfunction "-_-") (pintype "passive"))
      (node (ref "C12") (pin "-") (pinfunction "-_-") (pintype "passive"))
      (node (ref "C13") (pin "1") (pinfunction "1_1") (pintype "passive"))
      (node (ref "C14") (pin "1") (pinfunction "1_1") (pintype "passive"))
      (node (ref "C15") (pin "1") (pinfunction "1_1") (pintype "passive"))
      (node (ref "C16") (pin "1") (pinfunction "1_1") (pintype "passive"))
      (node (ref "C17") (pin "1") (pinfunction "1_1") (pintype "passive"))
      (node (ref "C18") (pin "1") (pinfunction "1_1") (pintype "passive"))
      (node (ref "C19") (pin "1") (pinfunction "1_1") (pintype "passive"))
      (node (ref "C2") (pin "2") (pinfunction "2_2") (pintype "passive"))
      (node (ref "C20") (pin "1") (pinfunction "1_1") (pintype "passive"))
      (node (ref "C21") (pin "1") (pinfunction "1_1") (pintype "passive"))
      (node (ref "C22") (pin "1") (pinfunction "1_1") (pintype "passive"))
      (node (ref "C4") (pin "1") (pinfunction "1_1") (pintype "passive"))
      (node (ref "C7") (pin "-") (pinfunction "-_-") (pintype "passive"))
      (node (ref "C8") (pin "2") (pinfunction "2_2") (pintype "passive"))
      (node (ref "C9") (pin "-") (pinfunction "-_-") (pintype "passive"))
      (node (ref "EAR") (pin "GND") (pinfunction "SLEEVE_GND") (pintype "passive"))
      (node (ref "JP6") (pin "1") (pinfunction "1_1") (pintype "passive"))
      (node (ref "LED1") (pin "K") (pinfunction "C_K") (pintype "passive"))
      (node (ref "LED2") (pin "K") (pinfunction "C_K") (pintype "passive"))
      (node (ref "MIC") (pin "GND") (pinfunction "SLEEVE_GND") (pintype "passive"))
      (node (ref "POWER") (pin "GND") (pinfunction "SLEEVE_GND") (pintype "passive"))
      (node (ref "Q1") (pin "3") (pinfunction "E_3") (pintype "passive"))
      (node (ref "Q3") (pin "1") (pinfunction "E_1") (pintype "passive"))
      (node (ref "R32") (pin "1") (pinfunction "1_1") (pintype "passive"))
      (node (ref "R4") (pin "E") (pinfunction "E_E") (pintype "passive"))
      (node (ref "R5") (pin "1") (pinfunction "1_1") (pintype "passive"))
      (node (ref "R6") (pin "1") (pinfunction "1_1") (pintype "passive"))
      (node (ref "S1") (pin "1") (pinfunction "1_1") (pintype "passive"))
      (node (ref "S1") (pin "2") (pinfunction "2_2") (pintype "passive"))
      (node (ref "S1") (pin "3") (pinfunction "3_3") (pintype "passive"))
      (node (ref "S2") (pin "1") (pinfunction "P_1") (pintype "passive"))
      (node (ref "U1") (pin "2") (pinfunction "GND_2") (pintype "passive"))
      (node (ref "U2") (pin "2") (pinfunction "VEE_2") (pintype "power_in"))
      (node (ref "X1") (pin "2") (pinfunction "2_2") (pintype "passive"))
      (node (ref "X2") (pin "1") (pinfunction "2_1") (pintype "passive"))
      (node (ref "Z0") (pin "29") (pinfunction "GND_29") (pintype "power_in"))
      (node (ref "Z1") (pin "1") (pinfunction "CLR_1") (pintype "input"))
      (node (ref "Z1") (pin "2") (pinfunction "D_2") (pintype "input"))
      (node (ref "Z1") (pin "3") (pinfunction "CLK_3") (pintype "input"))
      (node (ref "Z1") (pin "4") (pinfunction "PRE_4") (pintype "input"))
      (node (ref "Z1-2") (pin "14") (pinfunction "VSS_14") (pintype "power_in"))
      (node (ref "Z10") (pin "12") (pinfunction "CLR_12") (pintype "input"))
      (node (ref "Z18") (pin "15") (pinfunction "2G_15") (pintype "input"))
      (node (ref "Z23") (pin "10") (pinfunction "I1_10") (pintype "input"))
      (node (ref "Z28") (pin "1") (pinfunction "SER_1") (pintype "input"))
      (node (ref "Z28") (pin "6") (pinfunction "INH_6") (pintype "input"))
      (node (ref "Z40") (pin "10") (pinfunction "GND_10") (pintype "power_in"))
      (node (ref "Z41") (pin "12") (pinfunction "I0_12") (pintype "input"))
      (node (ref "Z41") (pin "13") (pinfunction "I1_13") (pintype "input"))
      (node (ref "Z5-6") (pin "10") (pinfunction "A14_10") (pintype "input"))
      (node (ref "Z5-6") (pin "6") (pinfunction "A10_6") (pintype "input"))
      (node (ref "Z5-6") (pin "7") (pinfunction "A11_7") (pintype "input"))
      (node (ref "Z5-6") (pin "8") (pinfunction "A12_8") (pintype "input"))
      (node (ref "Z5-6") (pin "9") (pinfunction "A13_9") (pintype "input"))
      (node (ref "Z7-8") (pin "10") (pinfunction "A14_10") (pintype "input"))
      (node (ref "Z7-8") (pin "6") (pinfunction "A10_6") (pintype "input"))
      (node (ref "Z7-8") (pin "7") (pinfunction "A11_7") (pintype "input"))
      (node (ref "Z7-8") (pin "8") (pinfunction "A12_8") (pintype "input"))
      (node (ref "Z7-8") (pin "9") (pinfunction "A13_9") (pintype "input"))
      (node (ref "Z9") (pin "12") (pinfunction "CLR_12") (pintype "input"))
      (node (ref "Z9") (pin "2") (pinfunction "CLR_2") (pintype "input"))
    )
    (net (code "119") (name "Net-(C1-Pad1)") (class "Default")
      (node (ref "C1") (pin "1") (pinfunction "1_1") (pintype "passive"))
      (node (ref "X1") (pin "3") (pinfunction "3_3") (pintype "passive"))
    )
    (net (code "120") (name "Net-(C3-Pad1)") (class "Default")
      (node (ref "C3") (pin "1") (pinfunction "1_1") (pintype "passive"))
      (node (ref "EAR") (pin "TIP") (pinfunction "TIP_TIP") (pintype "passive"))
      (node (ref "R6") (pin "2") (pinfunction "2_2") (pintype "passive"))
    )
    (net (code "121") (name "Net-(C5-Pad1)") (class "Default")
      (node (ref "C5") (pin "1") (pinfunction "1_1") (pintype "passive"))
      (node (ref "C6") (pin "1") (pinfunction "1_1") (pintype "passive"))
      (node (ref "MIC") (pin "TIP") (pinfunction "TIP_TIP") (pintype "passive"))
    )
    (net (code "122") (name "Net-(C6-Pad2)") (class "Default")
      (node (ref "C6") (pin "2") (pinfunction "2_2") (pintype "passive"))
      (node (ref "R10") (pin "1") (pinfunction "1_1") (pintype "passive"))
    )
    (net (code "123") (name "Net-(D1-PadA)") (class "Default")
      (node (ref "D1") (pin "A") (pinfunction "A_A") (pintype "passive"))
      (node (ref "R3") (pin "S") (pinfunction "S_S") (pintype "passive"))
      (node (ref "R4") (pin "A") (pinfunction "A_A") (pintype "passive"))
      (node (ref "SJ1") (pin "2") (pinfunction "2_2") (pintype "passive"))
    )
    (net (code "124") (name "Net-(JP5-Pad2)") (class "Default")
      (node (ref "JP5") (pin "2") (pinfunction "2_2") (pintype "passive"))
      (node (ref "R11") (pin "1") (pinfunction "1_1") (pintype "passive"))
    )
    (net (code "125") (name "Net-(JP7-Pad2)") (class "Default")
      (node (ref "JP7") (pin "2") (pinfunction "2_2") (pintype "passive"))
      (node (ref "POWER") (pin "TIP") (pinfunction "TIP_TIP") (pintype "passive"))
    )
    (net (code "126") (name "Net-(JP10-Pad2)") (class "Default")
      (node (ref "JP10") (pin "2") (pinfunction "2_2") (pintype "passive"))
      (node (ref "R12") (pin "1") (pinfunction "1_1") (pintype "passive"))
    )
    (net (code "127") (name "Net-(JP10B-2)") (class "Default")
      (node (ref "JP10") (pin "4") (pinfunction "2_4") (pintype "passive"))
      (node (ref "R13") (pin "1") (pinfunction "1_1") (pintype "passive"))
    )
    (net (code "128") (name "Net-(JP10C-2)") (class "Default")
      (node (ref "JP10") (pin "6") (pinfunction "2_6") (pintype "passive"))
      (node (ref "R14") (pin "1") (pinfunction "1_1") (pintype "passive"))
    )
    (net (code "129") (name "Net-(JP10D-2)") (class "Default")
      (node (ref "JP10") (pin "8") (pinfunction "2_8") (pintype "passive"))
      (node (ref "R15") (pin "1") (pinfunction "1_1") (pintype "passive"))
    )
    (net (code "130") (name "Net-(JP15-Pad2)") (class "Default")
      (node (ref "JP15") (pin "2") (pinfunction "2_2") (pintype "passive"))
      (node (ref "R16") (pin "1") (pinfunction "1_1") (pintype "passive"))
    )
    (net (code "131") (name "Net-(JP15B-2)") (class "Default")
      (node (ref "JP15") (pin "4") (pinfunction "2_4") (pintype "passive"))
      (node (ref "R17") (pin "1") (pinfunction "1_1") (pintype "passive"))
    )
    (net (code "132") (name "Net-(JP15C-2)") (class "Default")
      (node (ref "JP15") (pin "6") (pinfunction "2_6") (pintype "passive"))
      (node (ref "R18") (pin "1") (pinfunction "1_1") (pintype "passive"))
    )
    (net (code "133") (name "Net-(JP15D-2)") (class "Default")
      (node (ref "JP15") (pin "8") (pinfunction "2_8") (pintype "passive"))
      (node (ref "R19") (pin "1") (pinfunction "1_1") (pintype "passive"))
    )
    (net (code "134") (name "Net-(JP15E-2)") (class "Default")
      (node (ref "JP15") (pin "10") (pinfunction "2_10") (pintype "passive"))
      (node (ref "R20") (pin "1") (pinfunction "1_1") (pintype "passive"))
    )
    (net (code "135") (name "Net-(LED1-PadA)") (class "Default")
      (node (ref "LED1") (pin "A") (pinfunction "A_A") (pintype "passive"))
      (node (ref "R28") (pin "2") (pinfunction "2_2") (pintype "passive"))
    )
    (net (code "136") (name "Net-(LED2-PadA)") (class "Default")
      (node (ref "LED2") (pin "A") (pinfunction "A_A") (pintype "passive"))
      (node (ref "R29") (pin "1") (pinfunction "1_1") (pintype "passive"))
    )
    (net (code "137") (name "Net-(LS1-1)") (class "Default")
      (node (ref "C5") (pin "2") (pinfunction "2_2") (pintype "passive"))
      (node (ref "D2") (pin "A") (pinfunction "A_A") (pintype "passive"))
      (node (ref "LS1") (pin "-") (pinfunction "1_-") (pintype "passive"))
      (node (ref "Q3") (pin "3") (pinfunction "C_3") (pintype "passive"))
    )
    (net (code "138") (name "Net-(Q1-B)") (class "Default")
      (node (ref "C2") (pin "1") (pinfunction "1_1") (pintype "passive"))
      (node (ref "Q1") (pin "2") (pinfunction "B_2") (pintype "passive"))
      (node (ref "R2") (pin "1") (pinfunction "1_1") (pintype "passive"))
      (node (ref "X1") (pin "1") (pinfunction "1_1") (pintype "passive"))
    )
    (net (code "139") (name "Net-(Q1-C)") (class "Default")
      (node (ref "C1") (pin "2") (pinfunction "2_2") (pintype "passive"))
      (node (ref "Q1") (pin "1") (pinfunction "C_1") (pintype "passive"))
      (node (ref "R1") (pin "2") (pinfunction "2_2") (pintype "passive"))
      (node (ref "R2") (pin "2") (pinfunction "2_2") (pintype "passive"))
      (node (ref "Z23") (pin "9") (pinfunction "I0_9") (pintype "input"))
    )
    (net (code "140") (name "Net-(Q3-B)") (class "Default")
      (node (ref "Q3") (pin "2") (pinfunction "B_2") (pintype "passive"))
      (node (ref "R9") (pin "1") (pinfunction "1_1") (pintype "passive"))
    )
    (net (code "141") (name "Net-(U2-IN+)") (class "Default")
      (node (ref "R4") (pin "S") (pinfunction "S_S") (pintype "passive"))
      (node (ref "U2") (pin "3") (pinfunction "IN+_3") (pintype "input"))
    )
    (net (code "142") (name "Net-(U2-IN-)") (class "Default")
      (node (ref "R32") (pin "2") (pinfunction "2_2") (pintype "passive"))
      (node (ref "R33") (pin "2") (pinfunction "2_2") (pintype "passive"))
      (node (ref "U2") (pin "4") (pinfunction "IN-_4") (pintype "input"))
    )
    (net (code "143") (name "Net-(U2-OUT)") (class "Default")
      (node (ref "R33") (pin "1") (pinfunction "1_1") (pintype "passive"))
      (node (ref "R34") (pin "2") (pinfunction "2_2") (pintype "passive"))
      (node (ref "U2") (pin "1") (pinfunction "OUT_1") (pintype "output"))
    )
    (net (code "144") (name "Net-(Z1-2-A13)") (class "Default")
      (node (ref "R27") (pin "2") (pinfunction "2_2") (pintype "passive"))
      (node (ref "S1") (pin "5") (pinfunction "5_5") (pintype "passive"))
      (node (ref "Z1-2") (pin "26") (pinfunction "A13_26") (pintype "input"))
    )
    (net (code "145") (name "Net-(Z1-2-A14)") (class "Default")
      (node (ref "R8") (pin "2") (pinfunction "2_2") (pintype "passive"))
      (node (ref "S1") (pin "4") (pinfunction "4_4") (pintype "passive"))
      (node (ref "Z1-2") (pin "27") (pinfunction "A14_27") (pintype "input"))
    )
    (net (code "146") (name "Net-(Z1-2-~{CE})") (class "Default")
      (node (ref "Z1-2") (pin "20") (pinfunction "~{CE}_20") (pintype "input"))
      (node (ref "Z1-2") (pin "22") (pinfunction "~{OE}/VPP_22") (pintype "input"))
      (node (ref "Z22") (pin "8") (pinfunction "O_8") (pintype "output"))
    )
    (net (code "147") (name "Net-(Z1B-CLK)") (class "Default")
      (node (ref "Z1") (pin "11") (pinfunction "CLK_11") (pintype "input"))
      (node (ref "Z41") (pin "8") (pinfunction "O_8") (pintype "output"))
    )
    (net (code "148") (name "Net-(Z1B-Q)") (class "Default")
      (node (ref "Z1") (pin "9") (pinfunction "Q_9") (pintype "output"))
      (node (ref "Z31") (pin "9") (pinfunction "I0_9") (pintype "input"))
    )
    (net (code "149") (name "Net-(Z3-4A-~{CE})") (class "Default")
      (node (ref "JP3") (pin "2") (pinfunction "2_2") (pintype "passive"))
      (node (ref "Z3-4") (pin "20") (pinfunction "~{CE}_20") (pintype "input"))
    )
    (net (code "150") (name "Net-(Z10A-CLR)") (class "Default")
      (node (ref "Z10") (pin "2") (pinfunction "CLR_2") (pintype "input"))
      (node (ref "Z21") (pin "8") (pinfunction "O_8") (pintype "output"))
    )
    (net (code "151") (name "Net-(Z11A-CLR)") (class "Default")
      (node (ref "Z11") (pin "12") (pinfunction "CLR_12") (pintype "input"))
      (node (ref "Z11") (pin "2") (pinfunction "CLR_2") (pintype "input"))
      (node (ref "Z20") (pin "3") (pinfunction "O_3") (pintype "output"))
    )
    (net (code "152") (name "Net-(Z14A-1G)") (class "Default")
      (node (ref "Z14") (pin "1") (pinfunction "1G_1") (pintype "input"))
      (node (ref "Z14") (pin "15") (pinfunction "2G_15") (pintype "input"))
      (node (ref "Z23") (pin "2") (pinfunction "I1_2") (pintype "input"))
      (node (ref "Z26") (pin "8") (pinfunction "O_8") (pintype "output"))
    )
    (net (code "153") (name "Net-(Z15A-1G)") (class "Default")
      (node (ref "D11") (pin "C") (pinfunction "C_C") (pintype "passive"))
      (node (ref "R26") (pin "2") (pinfunction "2_2") (pintype "passive"))
      (node (ref "Z15") (pin "1") (pinfunction "1G_1") (pintype "input"))
      (node (ref "Z15") (pin "15") (pinfunction "2G_15") (pintype "input"))
      (node (ref "Z16") (pin "1") (pinfunction "1G_1") (pintype "input"))
      (node (ref "Z16") (pin "14") (pinfunction "2A2_14") (pintype "input"))
      (node (ref "Z24") (pin "2") (pinfunction "I0_2") (pintype "input"))
      (node (ref "Z24") (pin "5") (pinfunction "I0_5") (pintype "input"))
      (node (ref "Z26") (pin "13") (pinfunction "I1_13") (pintype "input"))
    )
    (net (code "154") (name "Net-(Z16A-2Y2)") (class "Default")
      (node (ref "D11") (pin "A") (pinfunction "A_A") (pintype "passive"))
      (node (ref "Z16") (pin "13") (pinfunction "2Y2_13") (pintype "tri_state"))
    )
    (net (code "155") (name "Net-(Z17A-1G)") (class "Default")
      (node (ref "Z17") (pin "1") (pinfunction "1G_1") (pintype "input"))
      (node (ref "Z17") (pin "15") (pinfunction "2G_15") (pintype "input"))
      (node (ref "Z18") (pin "1") (pinfunction "1G_1") (pintype "input"))
      (node (ref "Z23") (pin "6") (pinfunction "O_6") (pintype "output"))
    )
    (net (code "156") (name "Net-(Z18A-1Y2)") (class "Default")
      (node (ref "R23") (pin "2") (pinfunction "2_2") (pintype "passive"))
      (node (ref "Z18") (pin "5") (pinfunction "1Y2_5") (pintype "tri_state"))
      (node (ref "Z7-8") (pin "24") (pinfunction "A2_24") (pintype "input"))
    )
    (net (code "157") (name "Net-(Z18A-1Y3)") (class "Default")
      (node (ref "R22") (pin "2") (pinfunction "2_2") (pintype "passive"))
      (node (ref "Z18") (pin "7") (pinfunction "1Y3_7") (pintype "tri_state"))
      (node (ref "Z7-8") (pin "23") (pinfunction "A1_23") (pintype "input"))
    )
    (net (code "158") (name "Net-(Z18A-1Y4)") (class "Default")
      (node (ref "R21") (pin "2") (pinfunction "2_2") (pintype "passive"))
      (node (ref "Z18") (pin "9") (pinfunction "1Y4_9") (pintype "tri_state"))
      (node (ref "Z7-8") (pin "21") (pinfunction "A0_21") (pintype "input"))
    )
    (net (code "159") (name "Net-(Z18A-2A2)") (class "Default")
      (node (ref "C3") (pin "2") (pinfunction "2_2") (pintype "passive"))
      (node (ref "R5") (pin "2") (pinfunction "2_2") (pintype "passive"))
      (node (ref "R7") (pin "1") (pinfunction "1_1") (pintype "passive"))
      (node (ref "Z18") (pin "14") (pinfunction "2A2_14") (pintype "input"))
    )
    (net (code "160") (name "Net-(Z19A-O)") (class "Default")
      (node (ref "Z19") (pin "3") (pinfunction "O_3") (pintype "output"))
      (node (ref "Z20") (pin "4") (pinfunction "I0_4") (pintype "input"))
    )
    (net (code "161") (name "Net-(Z19B-I0)") (class "Default")
      (node (ref "Z19") (pin "4") (pinfunction "I0_4") (pintype "input"))
      (node (ref "Z20") (pin "9") (pinfunction "I0_9") (pintype "input"))
      (node (ref "Z22") (pin "6") (pinfunction "O_6") (pintype "output"))
    )
    (net (code "162") (name "Net-(Z19B-O)") (class "Default")
      (node (ref "Z19") (pin "6") (pinfunction "O_6") (pintype "output"))
      (node (ref "Z28") (pin "15") (pinfunction "SH/~{LD}_15") (pintype "input"))
    )
    (net (code "163") (name "Net-(Z20A-I0)") (class "Default")
      (node (ref "Z20") (pin "1") (pinfunction "I0_1") (pintype "input"))
      (node (ref "Z21") (pin "13") (pinfunction "I2_13") (pintype "input"))
      (node (ref "Z21") (pin "6") (pinfunction "O_6") (pintype "output"))
    )
    (net (code "164") (name "Net-(Z20B-I1)") (class "Default")
      (node (ref "Z20") (pin "5") (pinfunction "I1_5") (pintype "input"))
      (node (ref "Z25") (pin "1") (pinfunction "O_1") (pintype "output"))
    )
    (net (code "165") (name "Net-(Z20C-O)") (class "Default")
      (node (ref "Z20") (pin "8") (pinfunction "O_8") (pintype "output"))
      (node (ref "Z27") (pin "11") (pinfunction "CLK_11") (pintype "input"))
    )
    (net (code "166") (name "Net-(Z20D-O)") (class "Default")
      (node (ref "Z20") (pin "11") (pinfunction "O_11") (pintype "output"))
      (node (ref "Z27") (pin "12") (pinfunction "D_12") (pintype "input"))
    )
    (net (code "167") (name "Net-(Z22A-I1)") (class "Default")
      (node (ref "Z22") (pin "2") (pinfunction "I1_2") (pintype "input"))
      (node (ref "Z25") (pin "13") (pinfunction "O_13") (pintype "output"))
    )
    (net (code "168") (name "Net-(Z22C-I0)") (class "Default")
      (node (ref "Z22") (pin "9") (pinfunction "I0_9") (pintype "input"))
      (node (ref "Z29") (pin "15") (pinfunction "Y0_15") (pintype "output"))
    )
    (net (code "169") (name "Net-(Z22C-I1)") (class "Default")
      (node (ref "Z22") (pin "10") (pinfunction "I1_10") (pintype "input"))
      (node (ref "Z29") (pin "14") (pinfunction "Y1_14") (pintype "output"))
    )
    (net (code "170") (name "Net-(Z23A-O)") (class "Default")
      (node (ref "Z23") (pin "3") (pinfunction "O_3") (pintype "output"))
      (node (ref "Z24") (pin "12") (pinfunction "I1_12") (pintype "input"))
    )
    (net (code "171") (name "Net-(Z23B-I0)") (class "Default")
      (node (ref "Z23") (pin "4") (pinfunction "I0_4") (pintype "input"))
      (node (ref "Z24") (pin "1") (pinfunction "O_1") (pintype "output"))
      (node (ref "Z5-6") (pin "20") (pinfunction "~{CE}_20") (pintype "input"))
    )
    (net (code "172") (name "Net-(Z23D-I0)") (class "Default")
      (node (ref "JP4") (pin "2") (pinfunction "2_2") (pintype "passive"))
      (node (ref "Z23") (pin "12") (pinfunction "I0_12") (pintype "input"))
    )
    (net (code "173") (name "Net-(Z23D-I1)") (class "Default")
      (node (ref "Z23") (pin "13") (pinfunction "I1_13") (pintype "input"))
      (node (ref "Z28") (pin "13") (pinfunction "QH_13") (pintype "output"))
    )
    (net (code "174") (name "Net-(Z23D-O)") (class "Default")
      (node (ref "C4") (pin "2") (pinfunction "2_2") (pintype "passive"))
      (node (ref "R35") (pin "2") (pinfunction "2_2") (pintype "passive"))
      (node (ref "Z23") (pin "11") (pinfunction "O_11") (pintype "output"))
    )
    (net (code "175") (name "Net-(Z24A-I1)") (class "Default")
      (node (ref "Z24") (pin "3") (pinfunction "I1_3") (pintype "input"))
      (node (ref "Z24") (pin "4") (pinfunction "O_4") (pintype "output"))
      (node (ref "Z7-8") (pin "20") (pinfunction "~{CE}_20") (pintype "input"))
    )
    (net (code "176") (name "Net-(Z24C-I0)") (class "Default")
      (node (ref "Z24") (pin "8") (pinfunction "I0_8") (pintype "input"))
      (node (ref "Z25") (pin "10") (pinfunction "O_10") (pintype "output"))
      (node (ref "Z27") (pin "3") (pinfunction "CLK_3") (pintype "input"))
    )
    (net (code "177") (name "Net-(Z24C-I1)") (class "Default")
      (node (ref "R9") (pin "2") (pinfunction "2_2") (pintype "passive"))
      (node (ref "Z24") (pin "13") (pinfunction "O_13") (pintype "output"))
      (node (ref "Z24") (pin "9") (pinfunction "I1_9") (pintype "input"))
    )
    (net (code "178") (name "Net-(Z24C-O)") (class "Default")
      (node (ref "Z24") (pin "10") (pinfunction "O_10") (pintype "output"))
      (node (ref "Z24") (pin "11") (pinfunction "I0_11") (pintype "input"))
    )
    (net (code "179") (name "Net-(Z25C-I0)") (class "Default")
      (node (ref "Z25") (pin "8") (pinfunction "I0_8") (pintype "input"))
      (node (ref "Z26") (pin "6") (pinfunction "O_6") (pintype "output"))
      (node (ref "Z26") (pin "9") (pinfunction "I0_9") (pintype "input"))
    )
    (net (code "180") (name "Net-(Z26A-I1)") (class "Default")
      (node (ref "R26") (pin "1") (pinfunction "1_1") (pintype "passive"))
      (node (ref "Z26") (pin "2") (pinfunction "I1_2") (pintype "input"))
      (node (ref "Z29") (pin "13") (pinfunction "Y2_13") (pintype "output"))
    )
    (net (code "181") (name "Net-(Z27A-Q)") (class "Default")
      (node (ref "R10") (pin "2") (pinfunction "2_2") (pintype "passive"))
      (node (ref "Z27") (pin "5") (pinfunction "Q_5") (pintype "output"))
    )
    (net (code "182") (name "Net-(Z27B-Q)") (class "Default")
      (node (ref "JP4") (pin "1") (pinfunction "1_1") (pintype "passive"))
      (node (ref "Z27") (pin "9") (pinfunction "Q_9") (pintype "output"))
    )
    (net (code "183") (name "Net-(Z27B-~{Q})") (class "Default")
      (node (ref "JP4") (pin "3") (pinfunction "3_3") (pintype "passive"))
      (node (ref "Z27") (pin "8") (pinfunction "~{Q}_8") (pintype "output"))
    )
    (net (code "184") (name "Net-(Z28A-A)") (class "Default")
      (node (ref "R200") (pin "2") (pinfunction "2_2") (pintype "passive"))
      (node (ref "Z28") (pin "2") (pinfunction "A_2") (pintype "input"))
      (node (ref "Z7-8") (pin "11") (pinfunction "DQ0_11") (pintype "bidirectional"))
    )
    (net (code "185") (name "Net-(Z28A-B)") (class "Default")
      (node (ref "R201") (pin "2") (pinfunction "2_2") (pintype "passive"))
      (node (ref "Z28") (pin "3") (pinfunction "B_3") (pintype "input"))
      (node (ref "Z7-8") (pin "12") (pinfunction "DQ1_12") (pintype "bidirectional"))
    )
    (net (code "186") (name "Net-(Z28A-C)") (class "Default")
      (node (ref "R202") (pin "2") (pinfunction "2_2") (pintype "passive"))
      (node (ref "Z28") (pin "4") (pinfunction "C_4") (pintype "input"))
      (node (ref "Z7-8") (pin "13") (pinfunction "DQ2_13") (pintype "bidirectional"))
    )
    (net (code "187") (name "Net-(Z28A-D)") (class "Default")
      (node (ref "R203") (pin "2") (pinfunction "2_2") (pintype "passive"))
      (node (ref "Z28") (pin "5") (pinfunction "D_5") (pintype "input"))
      (node (ref "Z7-8") (pin "15") (pinfunction "DQ3_15") (pintype "bidirectional"))
    )
    (net (code "188") (name "Net-(Z28A-E)") (class "Default")
      (node (ref "R204") (pin "2") (pinfunction "2_2") (pintype "passive"))
      (node (ref "Z28") (pin "10") (pinfunction "E_10") (pintype "input"))
      (node (ref "Z7-8") (pin "16") (pinfunction "DQ4_16") (pintype "bidirectional"))
    )
    (net (code "189") (name "Net-(Z28A-F)") (class "Default")
      (node (ref "R205") (pin "2") (pinfunction "2_2") (pintype "passive"))
      (node (ref "Z28") (pin "11") (pinfunction "F_11") (pintype "input"))
      (node (ref "Z7-8") (pin "17") (pinfunction "DQ5_17") (pintype "bidirectional"))
    )
    (net (code "190") (name "Net-(Z28A-G)") (class "Default")
      (node (ref "R206") (pin "2") (pinfunction "2_2") (pintype "passive"))
      (node (ref "Z28") (pin "12") (pinfunction "G_12") (pintype "input"))
      (node (ref "Z7-8") (pin "18") (pinfunction "DQ6_18") (pintype "bidirectional"))
    )
    (net (code "191") (name "Net-(Z28A-H)") (class "Default")
      (node (ref "R207") (pin "2") (pinfunction "2_2") (pintype "passive"))
      (node (ref "Z28") (pin "14") (pinfunction "H_14") (pintype "input"))
      (node (ref "Z7-8") (pin "19") (pinfunction "DQ7_19") (pintype "bidirectional"))
    )
    (net (code "192") (name "Net-(Z29A-Y3)") (class "Default")
      (node (ref "JP3") (pin "1") (pinfunction "1_1") (pintype "passive"))
      (node (ref "Z29") (pin "12") (pinfunction "Y3_12") (pintype "output"))
      (node (ref "Z31") (pin "3") (pinfunction "I0_3") (pintype "input"))
    )
    (net (code "193") (name "Net-(Z29A-Y4)") (class "Default")
      (node (ref "Z29") (pin "11") (pinfunction "Y4_11") (pintype "output"))
      (node (ref "Z31") (pin "4") (pinfunction "I1_4") (pintype "input"))
    )
    (net (code "194") (name "Net-(Z29A-Y5)") (class "Default")
      (node (ref "Z29") (pin "10") (pinfunction "Y5_10") (pintype "output"))
      (node (ref "Z31") (pin "5") (pinfunction "I2_5") (pintype "input"))
    )
    (net (code "195") (name "Net-(Z29A-Y6)") (class "Default")
      (node (ref "Z29") (pin "9") (pinfunction "Y6_9") (pintype "output"))
      (node (ref "Z31") (pin "2") (pinfunction "I1_2") (pintype "input"))
    )
    (net (code "196") (name "Net-(Z29A-Y7)") (class "Default")
      (node (ref "Z29") (pin "7") (pinfunction "Y7_7") (pintype "output"))
      (node (ref "Z31") (pin "13") (pinfunction "I2_13") (pintype "input"))
    )
    (net (code "197") (name "Net-(Z30A-O)") (class "Default")
      (node (ref "Z30") (pin "3") (pinfunction "O_3") (pintype "output"))
      (node (ref "Z5-6") (pin "22") (pinfunction "~{OE}_22") (pintype "input"))
      (node (ref "Z7-8") (pin "22") (pinfunction "~{OE}_22") (pintype "input"))
    )
    (net (code "198") (name "Net-(Z31A-I0)") (class "Default")
      (node (ref "Z31") (pin "1") (pinfunction "I0_1") (pintype "input"))
      (node (ref "Z31") (pin "6") (pinfunction "O_6") (pintype "output"))
    )
    (net (code "199") (name "Net-(Z31A-O)") (class "Default")
      (node (ref "JP3") (pin "3") (pinfunction "3_3") (pintype "passive"))
      (node (ref "Z31") (pin "12") (pinfunction "O_12") (pintype "output"))
    )
    (net (code "200") (name "Net-(Z31C-I1)") (class "Default")
      (node (ref "R35") (pin "1") (pinfunction "1_1") (pintype "passive"))
      (node (ref "Z31") (pin "10") (pinfunction "I1_10") (pintype "input"))
    )
    (net (code "201") (name "Net-(Z31C-O)") (class "Default")
      (node (ref "R3") (pin "A") (pinfunction "A_A") (pintype "passive"))
      (node (ref "Z31") (pin "8") (pinfunction "O_8") (pintype "output"))
    )
    (net (code "202") (name "Net-(Z40-O1)") (class "Default")
      (node (ref "D12") (pin "C") (pinfunction "C_C") (pintype "passive"))
      (node (ref "SJ9") (pin "2") (pinfunction "2_2") (pintype "passive"))
      (node (ref "Z40") (pin "19") (pinfunction "O1_19") (pintype "output"))
    )
    (net (code "203") (name "Net-(Z40-O2)") (class "Default")
      (node (ref "D13") (pin "C") (pinfunction "C_C") (pintype "passive"))
      (node (ref "SJ8") (pin "2") (pinfunction "2_2") (pintype "passive"))
      (node (ref "Z40") (pin "18") (pinfunction "O2_18") (pintype "output"))
    )
    (net (code "204") (name "Net-(Z40-O3)") (class "Default")
      (node (ref "D14") (pin "C") (pinfunction "C_C") (pintype "passive"))
      (node (ref "SJ2") (pin "2") (pinfunction "2_2") (pintype "passive"))
      (node (ref "Z40") (pin "17") (pinfunction "O3_17") (pintype "output"))
    )
    (net (code "205") (name "Net-(Z40-O4)") (class "Default")
      (node (ref "D15") (pin "C") (pinfunction "C_C") (pintype "passive"))
      (node (ref "SJ3") (pin "2") (pinfunction "2_2") (pintype "passive"))
      (node (ref "Z40") (pin "16") (pinfunction "O4_16") (pintype "output"))
    )
    (net (code "206") (name "Net-(Z40-O5)") (class "Default")
      (node (ref "D16") (pin "C") (pinfunction "C_C") (pintype "passive"))
      (node (ref "SJ4") (pin "2") (pinfunction "2_2") (pintype "passive"))
      (node (ref "Z40") (pin "15") (pinfunction "O5_15") (pintype "output"))
    )
    (net (code "207") (name "Net-(Z40-O6)") (class "Default")
      (node (ref "D17") (pin "C") (pinfunction "C_C") (pintype "passive"))
      (node (ref "SJ5") (pin "2") (pinfunction "2_2") (pintype "passive"))
      (node (ref "Z40") (pin "14") (pinfunction "O6_14") (pintype "output"))
    )
    (net (code "208") (name "Net-(Z41A-O)") (class "Default")
      (node (ref "Z41") (pin "3") (pinfunction "O_3") (pintype "output"))
      (node (ref "Z41") (pin "4") (pinfunction "I0_4") (pintype "input"))
    )
    (net (code "209") (name "Net-(Z41B-O)") (class "Default")
      (node (ref "Z41") (pin "10") (pinfunction "I1_10") (pintype "input"))
      (node (ref "Z41") (pin "6") (pinfunction "O_6") (pintype "output"))
    )
    (net (code "210") (name "VCC") (class "Default")
      (node (ref "11B1") (pin "1") (pinfunction "P_1") (pintype "passive"))
      (node (ref "4A") (pin "1") (pinfunction "P_1") (pintype "passive"))
      (node (ref "C12") (pin "+") (pinfunction "+_+") (pintype "passive"))
      (node (ref "C13") (pin "2") (pinfunction "2_2") (pintype "passive"))
      (node (ref "C14") (pin "2") (pinfunction "2_2") (pintype "passive"))
      (node (ref "C15") (pin "2") (pinfunction "2_2") (pintype "passive"))
      (node (ref "C16") (pin "2") (pinfunction "2_2") (pintype "passive"))
      (node (ref "C17") (pin "2") (pinfunction "2_2") (pintype "passive"))
      (node (ref "C18") (pin "2") (pinfunction "2_2") (pintype "passive"))
      (node (ref "C19") (pin "2") (pinfunction "2_2") (pintype "passive"))
      (node (ref "C20") (pin "2") (pinfunction "2_2") (pintype "passive"))
      (node (ref "C21") (pin "2") (pinfunction "2_2") (pintype "passive"))
      (node (ref "D2") (pin "C") (pinfunction "C_C") (pintype "passive"))
      (node (ref "JP8") (pin "1") (pinfunction "1_1") (pintype "passive"))
      (node (ref "JP8") (pin "2") (pinfunction "2_2") (pintype "passive"))
      (node (ref "LS1") (pin "+") (pinfunction "2_+") (pintype "passive"))
      (node (ref "R1") (pin "1") (pinfunction "1_1") (pintype "passive"))
      (node (ref "R24") (pin "2") (pinfunction "2_2") (pintype "passive"))
      (node (ref "R25") (pin "2") (pinfunction "2_2") (pintype "passive"))
      (node (ref "R27") (pin "1") (pinfunction "1_1") (pintype "passive"))
      (node (ref "R28") (pin "1") (pinfunction "1_1") (pintype "passive"))
      (node (ref "R3") (pin "E") (pinfunction "E_E") (pintype "passive"))
      (node (ref "R30") (pin "1") (pinfunction "1_1") (pintype "passive"))
      (node (ref "R31") (pin "1") (pinfunction "1_1") (pintype "passive"))
      (node (ref "R36") (pin "2") (pinfunction "2_2") (pintype "passive"))
      (node (ref "R37") (pin "2") (pinfunction "2_2") (pintype "passive"))
      (node (ref "R38") (pin "2") (pinfunction "2_2") (pintype "passive"))
      (node (ref "R39") (pin "2") (pinfunction "2_2") (pintype "passive"))
      (node (ref "R40") (pin "2") (pinfunction "2_2") (pintype "passive"))
      (node (ref "R41") (pin "2") (pinfunction "2_2") (pintype "passive"))
      (node (ref "R43") (pin "1") (pinfunction "1_1") (pintype "passive"))
      (node (ref "R7") (pin "2") (pinfunction "2_2") (pintype "passive"))
      (node (ref "R8") (pin "1") (pinfunction "1_1") (pintype "passive"))
      (node (ref "RN1") (pin "1") (pinfunction "1_1") (pintype "passive"))
      (node (ref "U1") (pin "3") (pinfunction "VO_3") (pintype "passive"))
      (node (ref "U2") (pin "5") (pinfunction "VCC_5") (pintype "power_in"))
      (node (ref "Z0") (pin "11") (pinfunction "VCC_11") (pintype "power_in"))
      (node (ref "Z1") (pin "10") (pinfunction "PRE_10") (pintype "input"))
      (node (ref "Z1") (pin "12") (pinfunction "D_12") (pintype "input"))
      (node (ref "Z1-2") (pin "28") (pinfunction "VCC_28") (pintype "power_in"))
      (node (ref "Z16") (pin "12") (pinfunction "2A1_12") (pintype "input"))
      (node (ref "Z18") (pin "12") (pinfunction "2A1_12") (pintype "input"))
      (node (ref "Z19") (pin "13") (pinfunction "I1_13") (pintype "input"))
      (node (ref "Z22") (pin "11") (pinfunction "I2_11") (pintype "input"))
      (node (ref "Z23") (pin "1") (pinfunction "I0_1") (pintype "input"))
      (node (ref "Z23") (pin "5") (pinfunction "I1_5") (pintype "input"))
      (node (ref "Z27") (pin "1") (pinfunction "CLR_1") (pintype "input"))
      (node (ref "Z27") (pin "10") (pinfunction "PRE_10") (pintype "input"))
      (node (ref "Z27") (pin "13") (pinfunction "CLR_13") (pintype "input"))
      (node (ref "Z27") (pin "4") (pinfunction "PRE_4") (pintype "input"))
      (node (ref "Z28") (pin "9") (pinfunction "CLR_9") (pintype "input"))
      (node (ref "Z29") (pin "6") (pinfunction "G1_6") (pintype "input"))
      (node (ref "Z31") (pin "11") (pinfunction "I2_11") (pintype "input"))
      (node (ref "Z40") (pin "20") (pinfunction "VCC_20") (pintype "power_in"))
      (node (ref "Z41") (pin "1") (pinfunction "I0_1") (pintype "input"))
      (node (ref "Z41") (pin "9") (pinfunction "I0_9") (pintype "input"))
    )
    (net (code "211") (name "unconnected-(10A1-P-Pad1)") (class "Default")
      (node (ref "10A1") (pin "1") (pinfunction "P_1") (pintype "passive"))
    )
    (net (code "212") (name "unconnected-(EAR-SWITCH-PadSW)") (class "Default")
      (node (ref "EAR") (pin "SW") (pinfunction "SWITCH_SW") (pintype "passive"))
    )
    (net (code "213") (name "unconnected-(JP7-Pad3)") (class "Default")
      (node (ref "JP7") (pin "3") (pinfunction "3_3") (pintype "passive"))
    )
    (net (code "214") (name "unconnected-(MIC-SWITCH-PadSW)") (class "Default")
      (node (ref "MIC") (pin "SW") (pinfunction "SWITCH_SW") (pintype "passive"))
    )
    (net (code "215") (name "unconnected-(POWER-SWITCH-PadSW)") (class "Default")
      (node (ref "POWER") (pin "SW") (pinfunction "SWITCH_SW") (pintype "passive"))
    )
    (net (code "216") (name "unconnected-(Z1A-Q-Pad5)") (class "Default")
      (node (ref "Z1") (pin "5") (pinfunction "Q_5") (pintype "output"))
    )
    (net (code "217") (name "unconnected-(Z1A-~{Q}-Pad6)") (class "Default")
      (node (ref "Z1") (pin "6") (pinfunction "~{Q}_6") (pintype "output"))
    )
    (net (code "218") (name "unconnected-(Z1B-~{Q}-Pad8)") (class "Default")
      (node (ref "Z1") (pin "8") (pinfunction "~{Q}_8") (pintype "output"))
    )
    (net (code "219") (name "unconnected-(Z9B-QB-Pad10)") (class "Default")
      (node (ref "Z9") (pin "10") (pinfunction "QB_10") (pintype "output"))
    )
    (net (code "220") (name "unconnected-(Z9B-QC-Pad9)") (class "Default")
      (node (ref "Z9") (pin "9") (pinfunction "QC_9") (pintype "output"))
    )
    (net (code "221") (name "unconnected-(Z9B-QD-Pad8)") (class "Default")
      (node (ref "Z9") (pin "8") (pinfunction "QD_8") (pintype "output"))
    )
    (net (code "222") (name "unconnected-(Z10B-QD-Pad8)") (class "Default")
      (node (ref "Z10") (pin "8") (pinfunction "QD_8") (pintype "output"))
    )
    (net (code "223") (name "unconnected-(Z11B-QC-Pad9)") (class "Default")
      (node (ref "Z11") (pin "9") (pinfunction "QC_9") (pintype "output"))
    )
    (net (code "224") (name "unconnected-(Z11B-QD-Pad8)") (class "Default")
      (node (ref "Z11") (pin "8") (pinfunction "QD_8") (pintype "output"))
    )
    (net (code "225") (name "unconnected-(Z16A-2Y1-Pad11)") (class "Default")
      (node (ref "Z16") (pin "11") (pinfunction "2Y1_11") (pintype "tri_state"))
    )
    (net (code "226") (name "unconnected-(Z18A-2Y1-Pad11)") (class "Default")
      (node (ref "Z18") (pin "11") (pinfunction "2Y1_11") (pintype "tri_state"))
    )
    (net (code "227") (name "unconnected-(Z27A-~{Q}-Pad6)") (class "Default")
      (node (ref "Z27") (pin "6") (pinfunction "~{Q}_6") (pintype "output"))
    )
    (net (code "228") (name "unconnected-(Z40-O7-Pad13)") (class "Default")
      (node (ref "Z40") (pin "13") (pinfunction "O7_13") (pintype "output"))
    )
    (net (code "229") (name "unconnected-(Z40-O8-Pad12)") (class "Default")
      (node (ref "Z40") (pin "12") (pinfunction "O8_12") (pintype "output"))
    )
    (net (code "230") (name "unconnected-(Z40-OE-Pad11)") (class "Default")
      (node (ref "Z40") (pin "11") (pinfunction "OE_11") (pintype "input"))
    )
    (net (code "231") (name "unconnected-(Z41D-O-Pad11)") (class "Default")
      (node (ref "Z41") (pin "11") (pinfunction "O_11") (pintype "output"))
    )
  )
)
